# Sheet1.net
KiCad netlist of a schematic drawn in Altium Designer
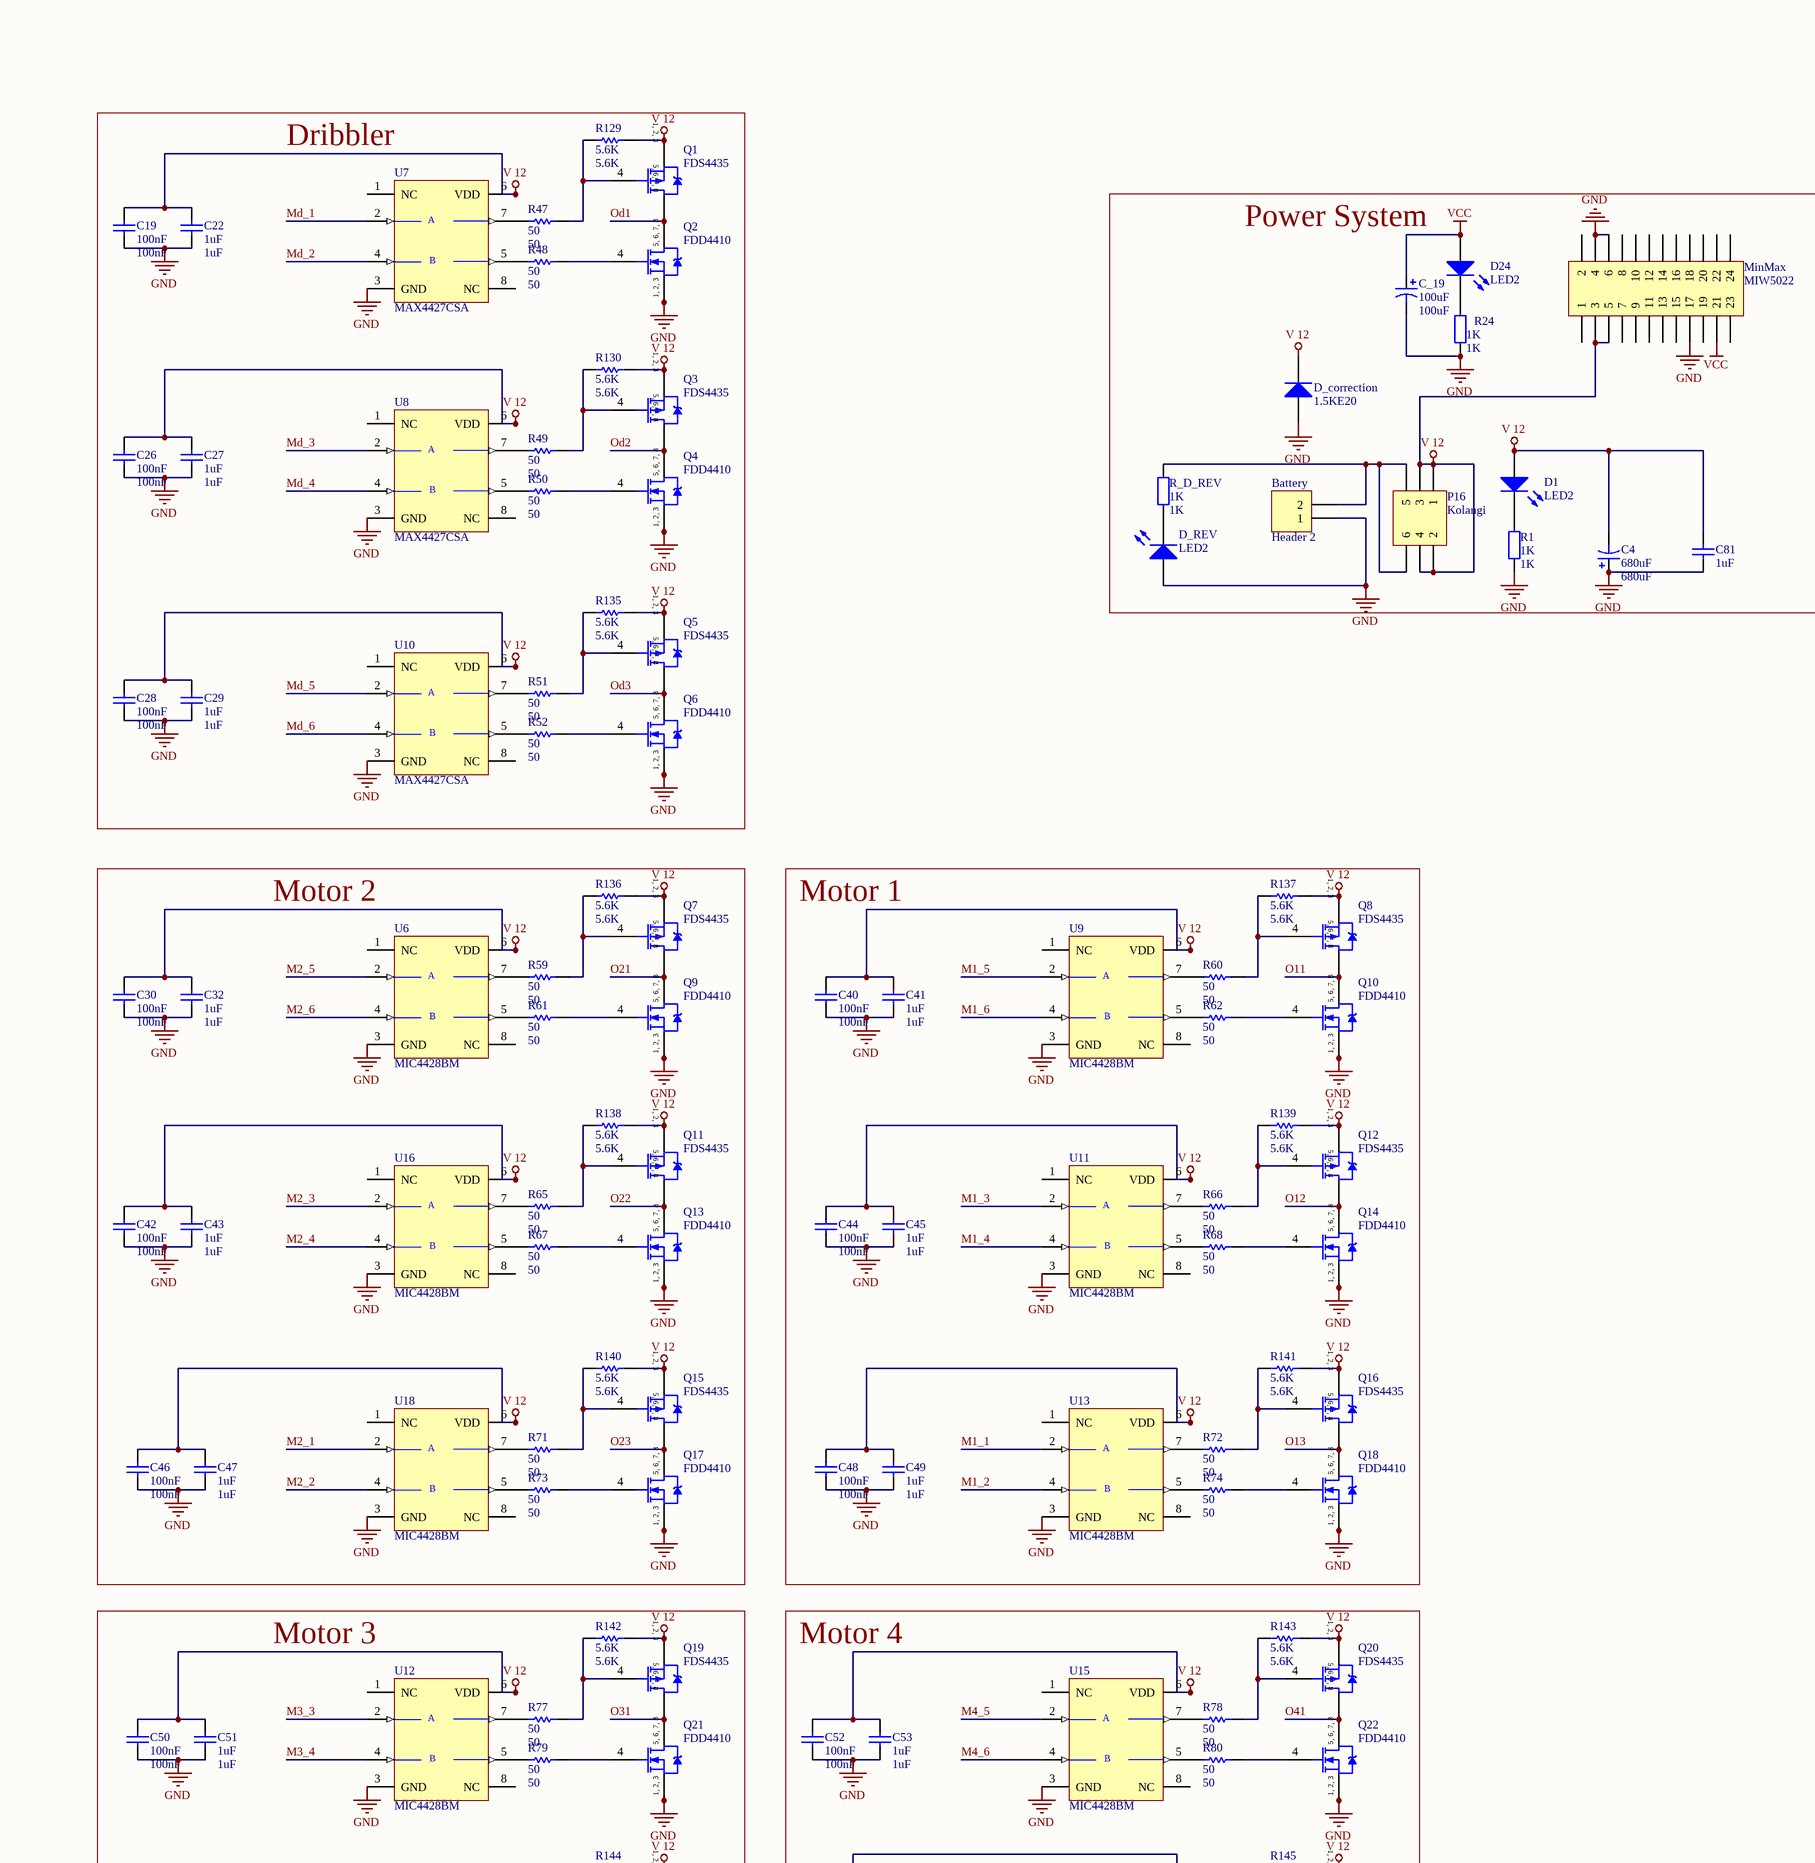
[diagram p0: Sheet1.SchDoc, top left]
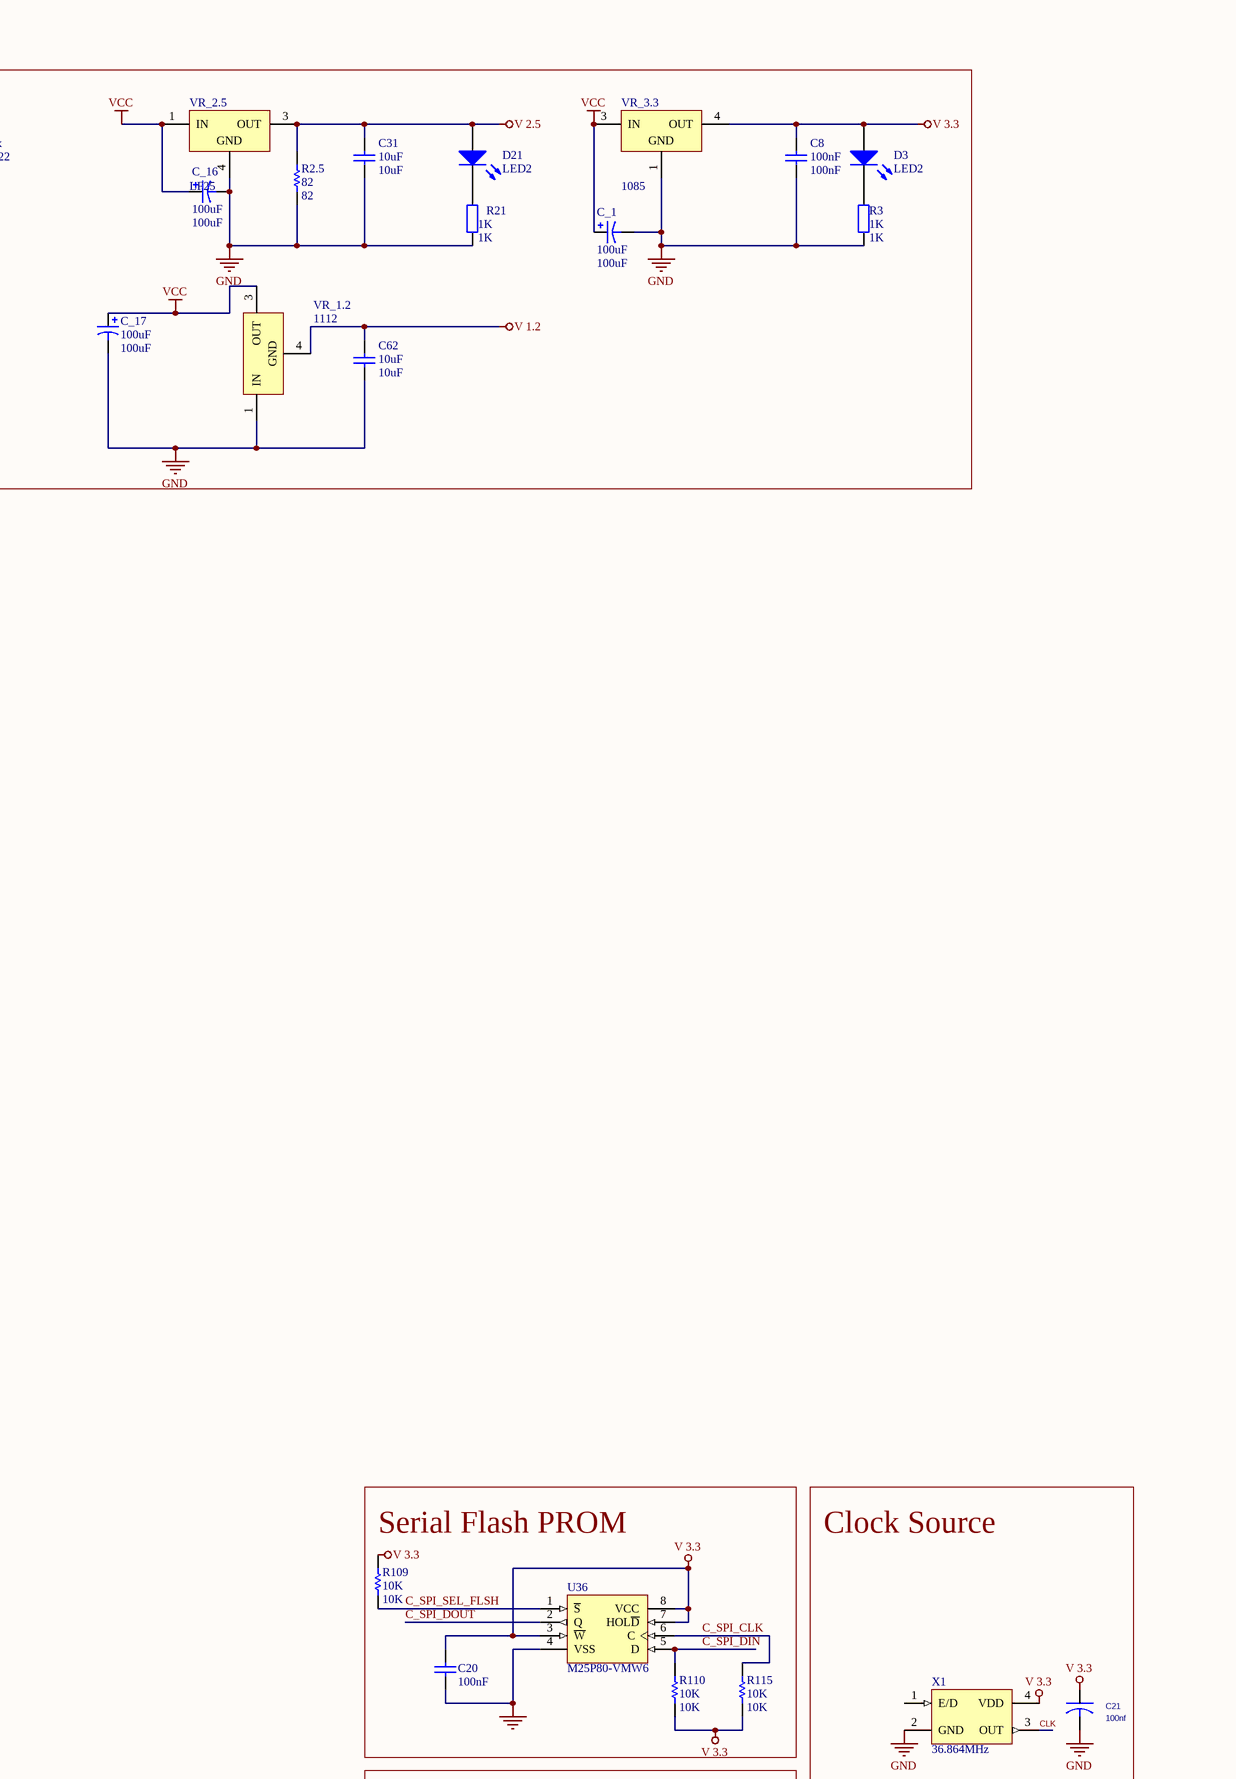
[diagram p1: Sheet1.SchDoc, top middle]
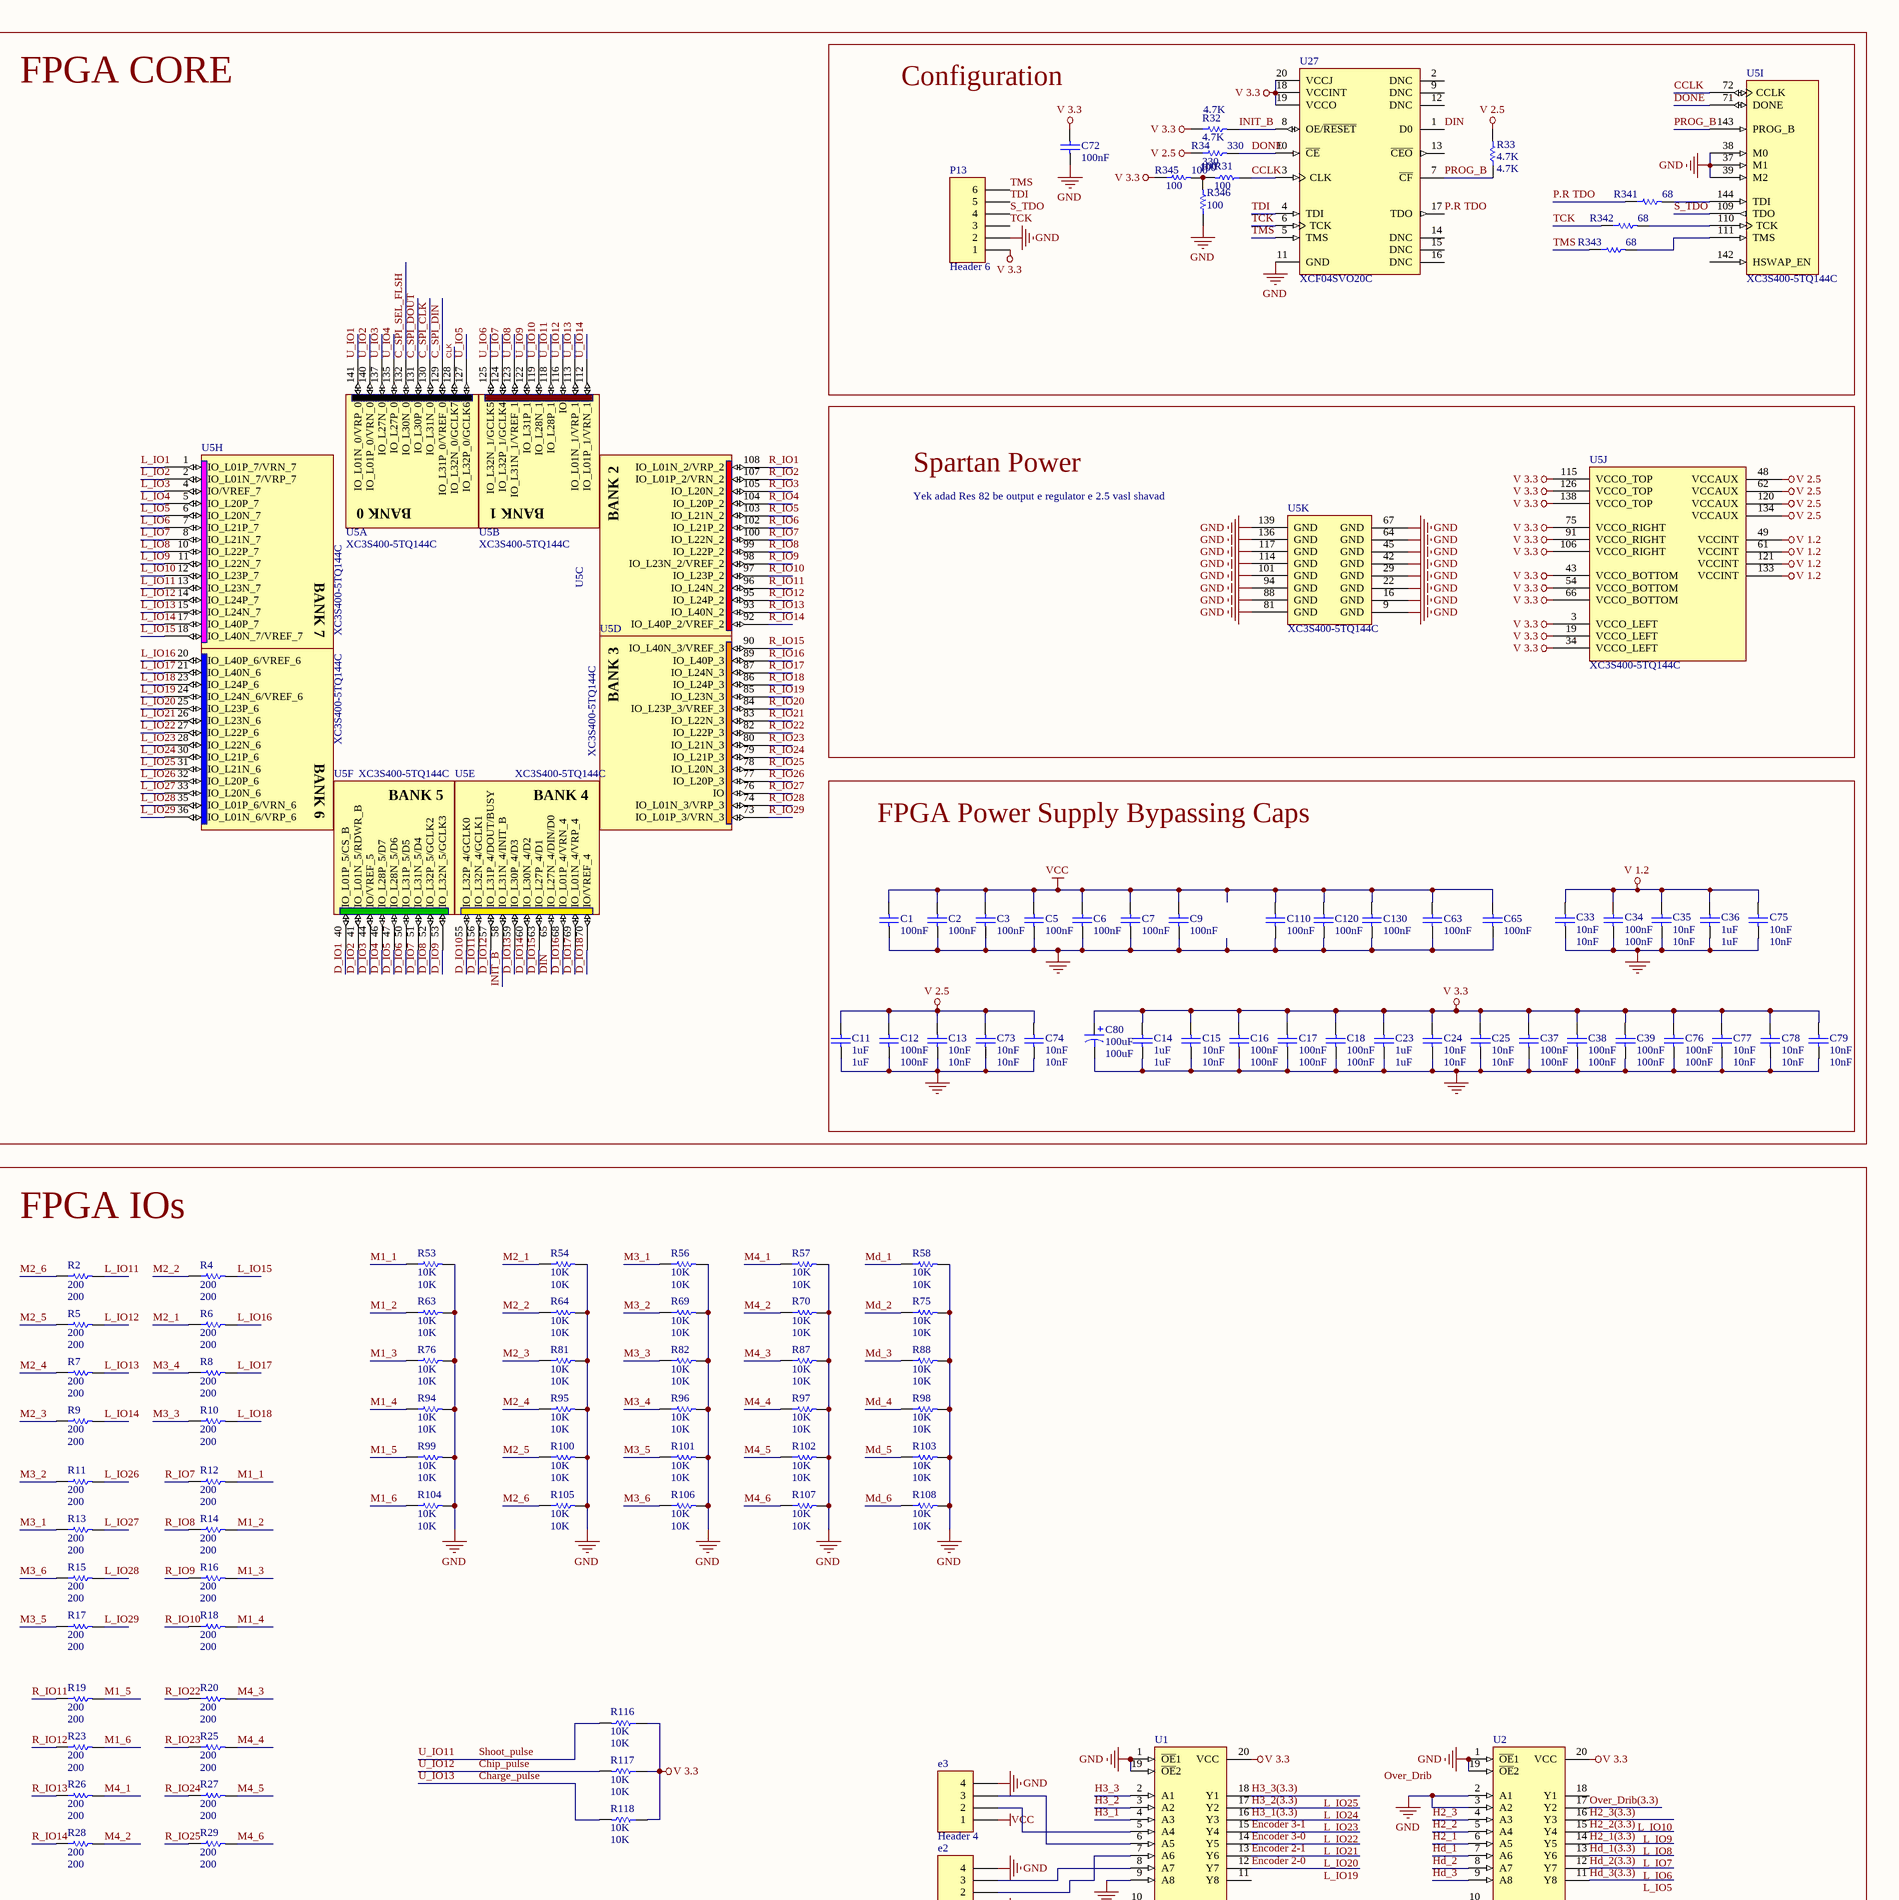
[diagram p2: Sheet1.SchDoc, top right]
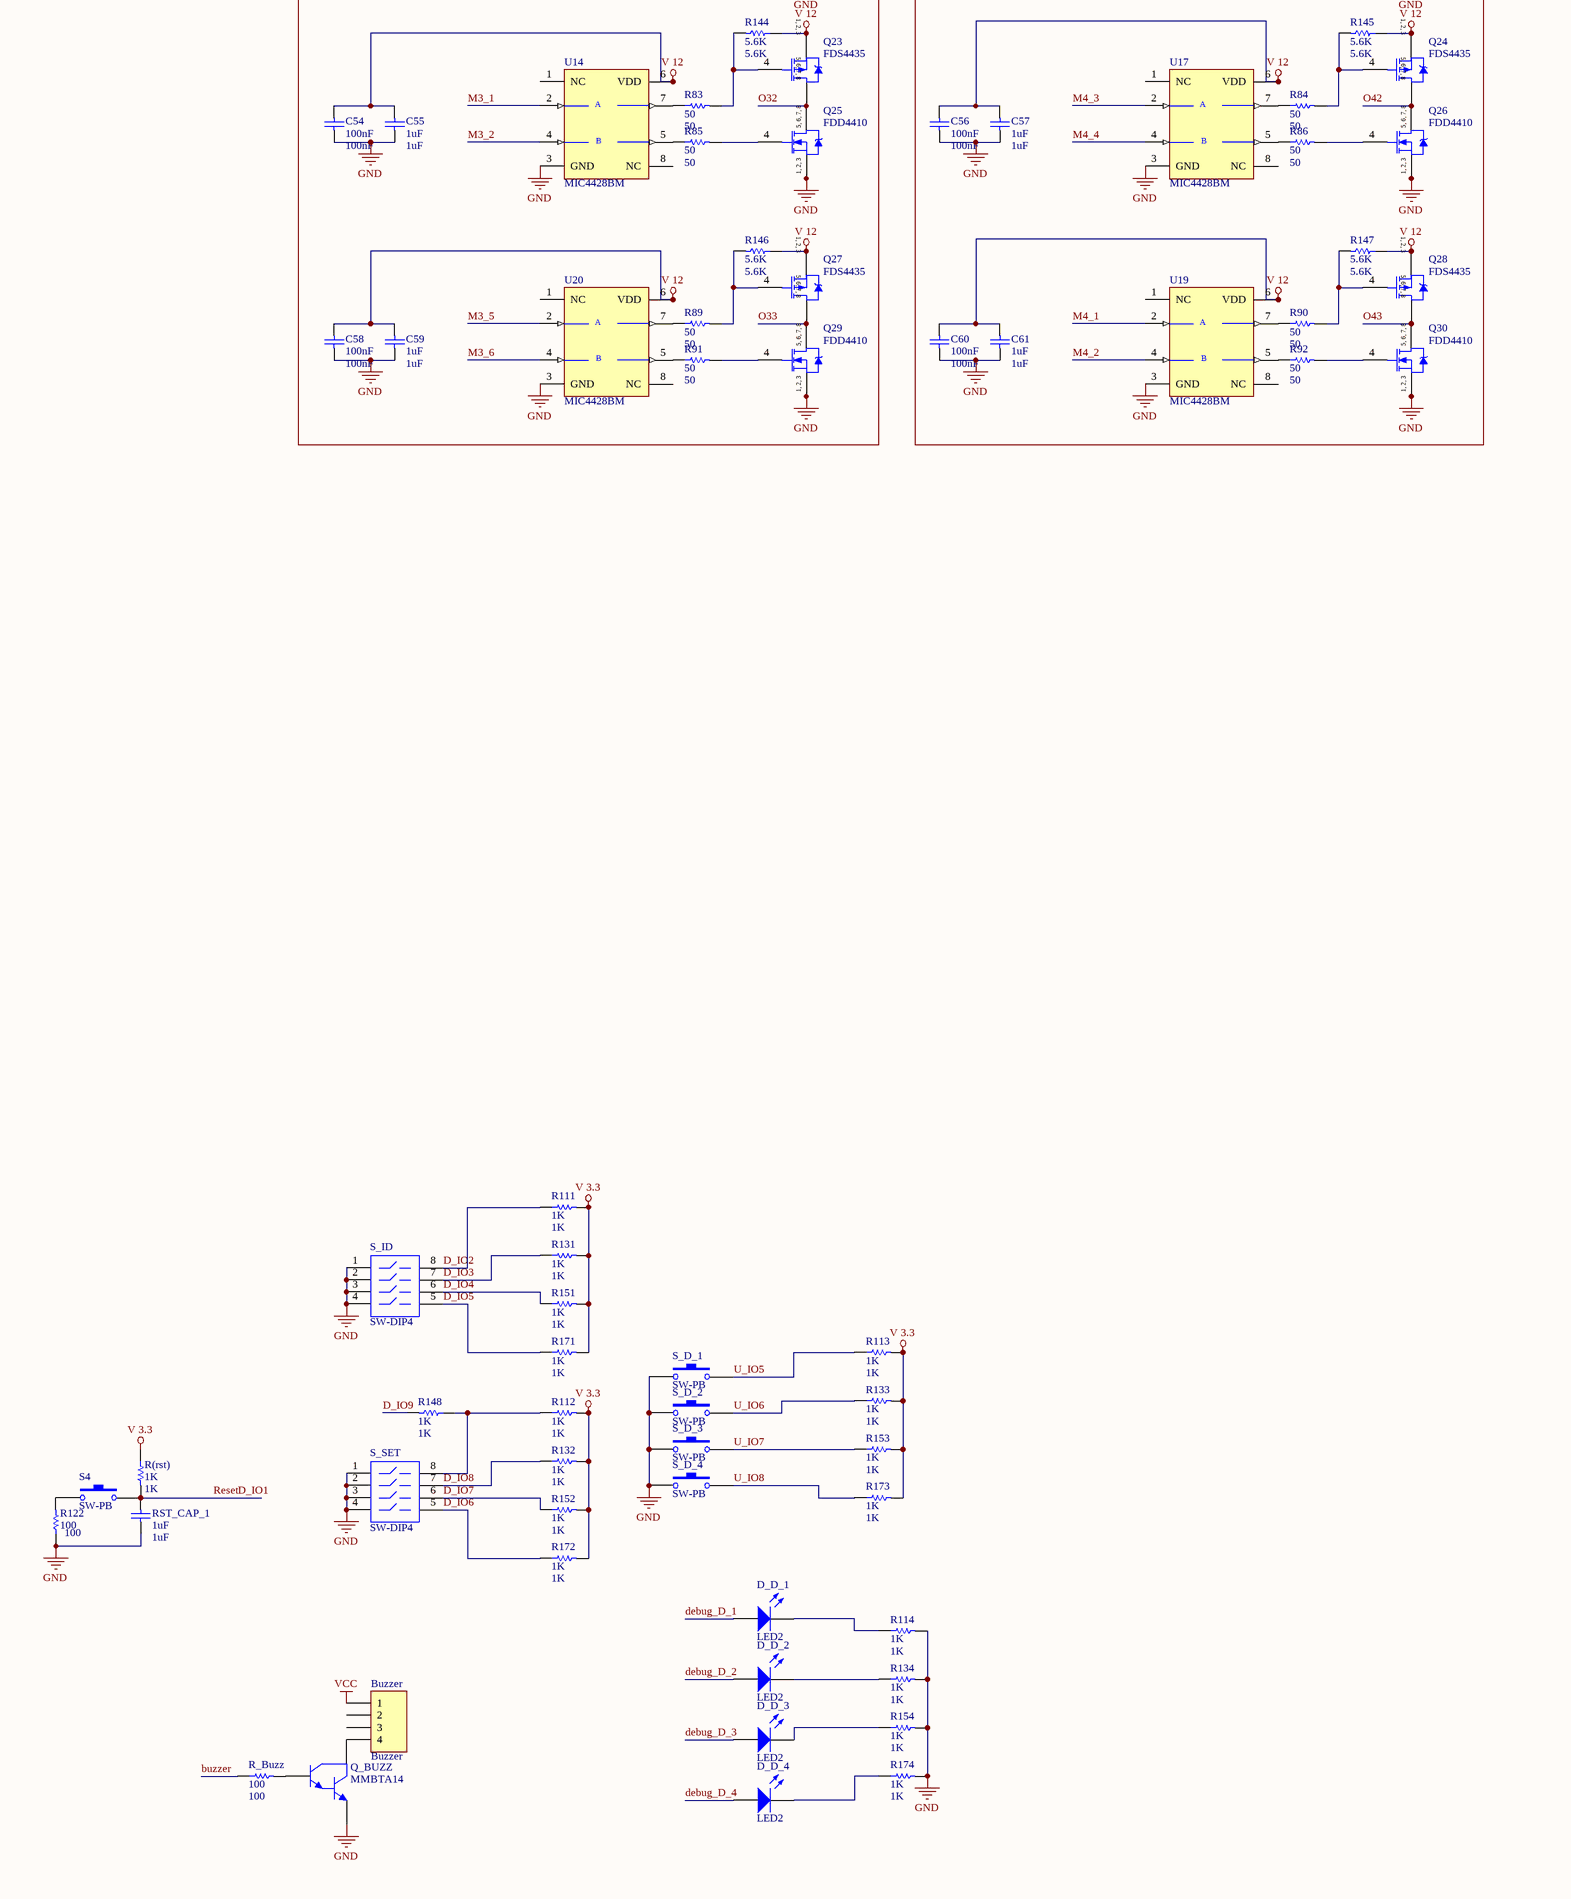
[diagram p3: Sheet1.SchDoc, bottom left]
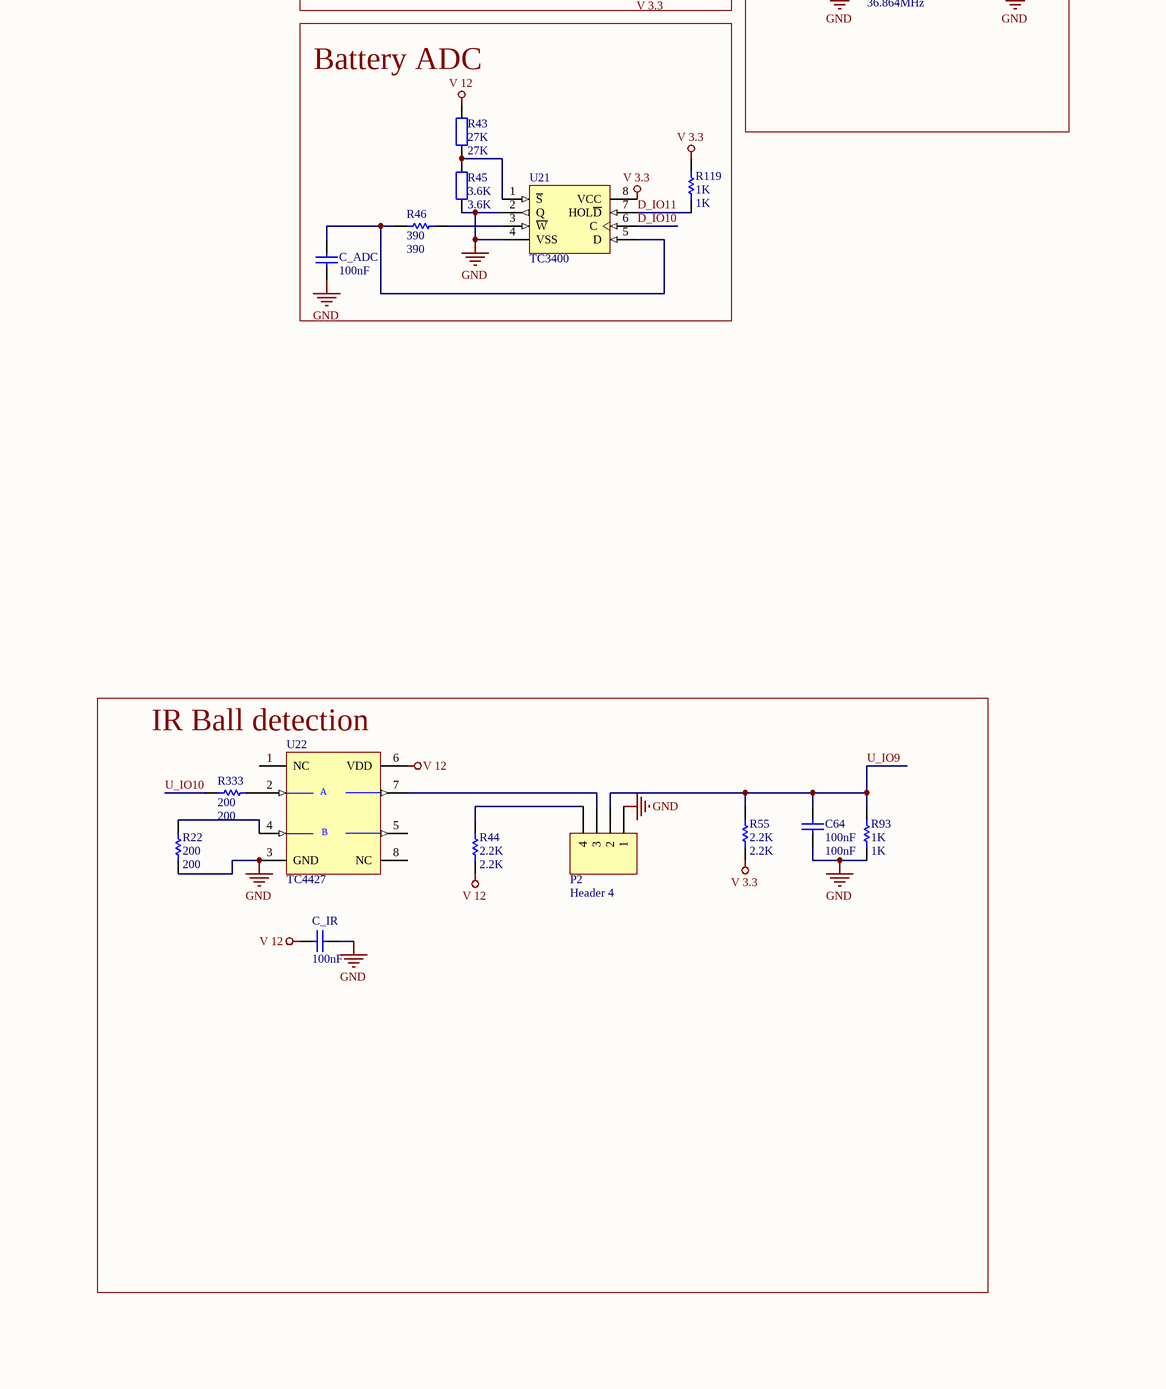
[diagram p4: Sheet1.SchDoc, bottom middle]
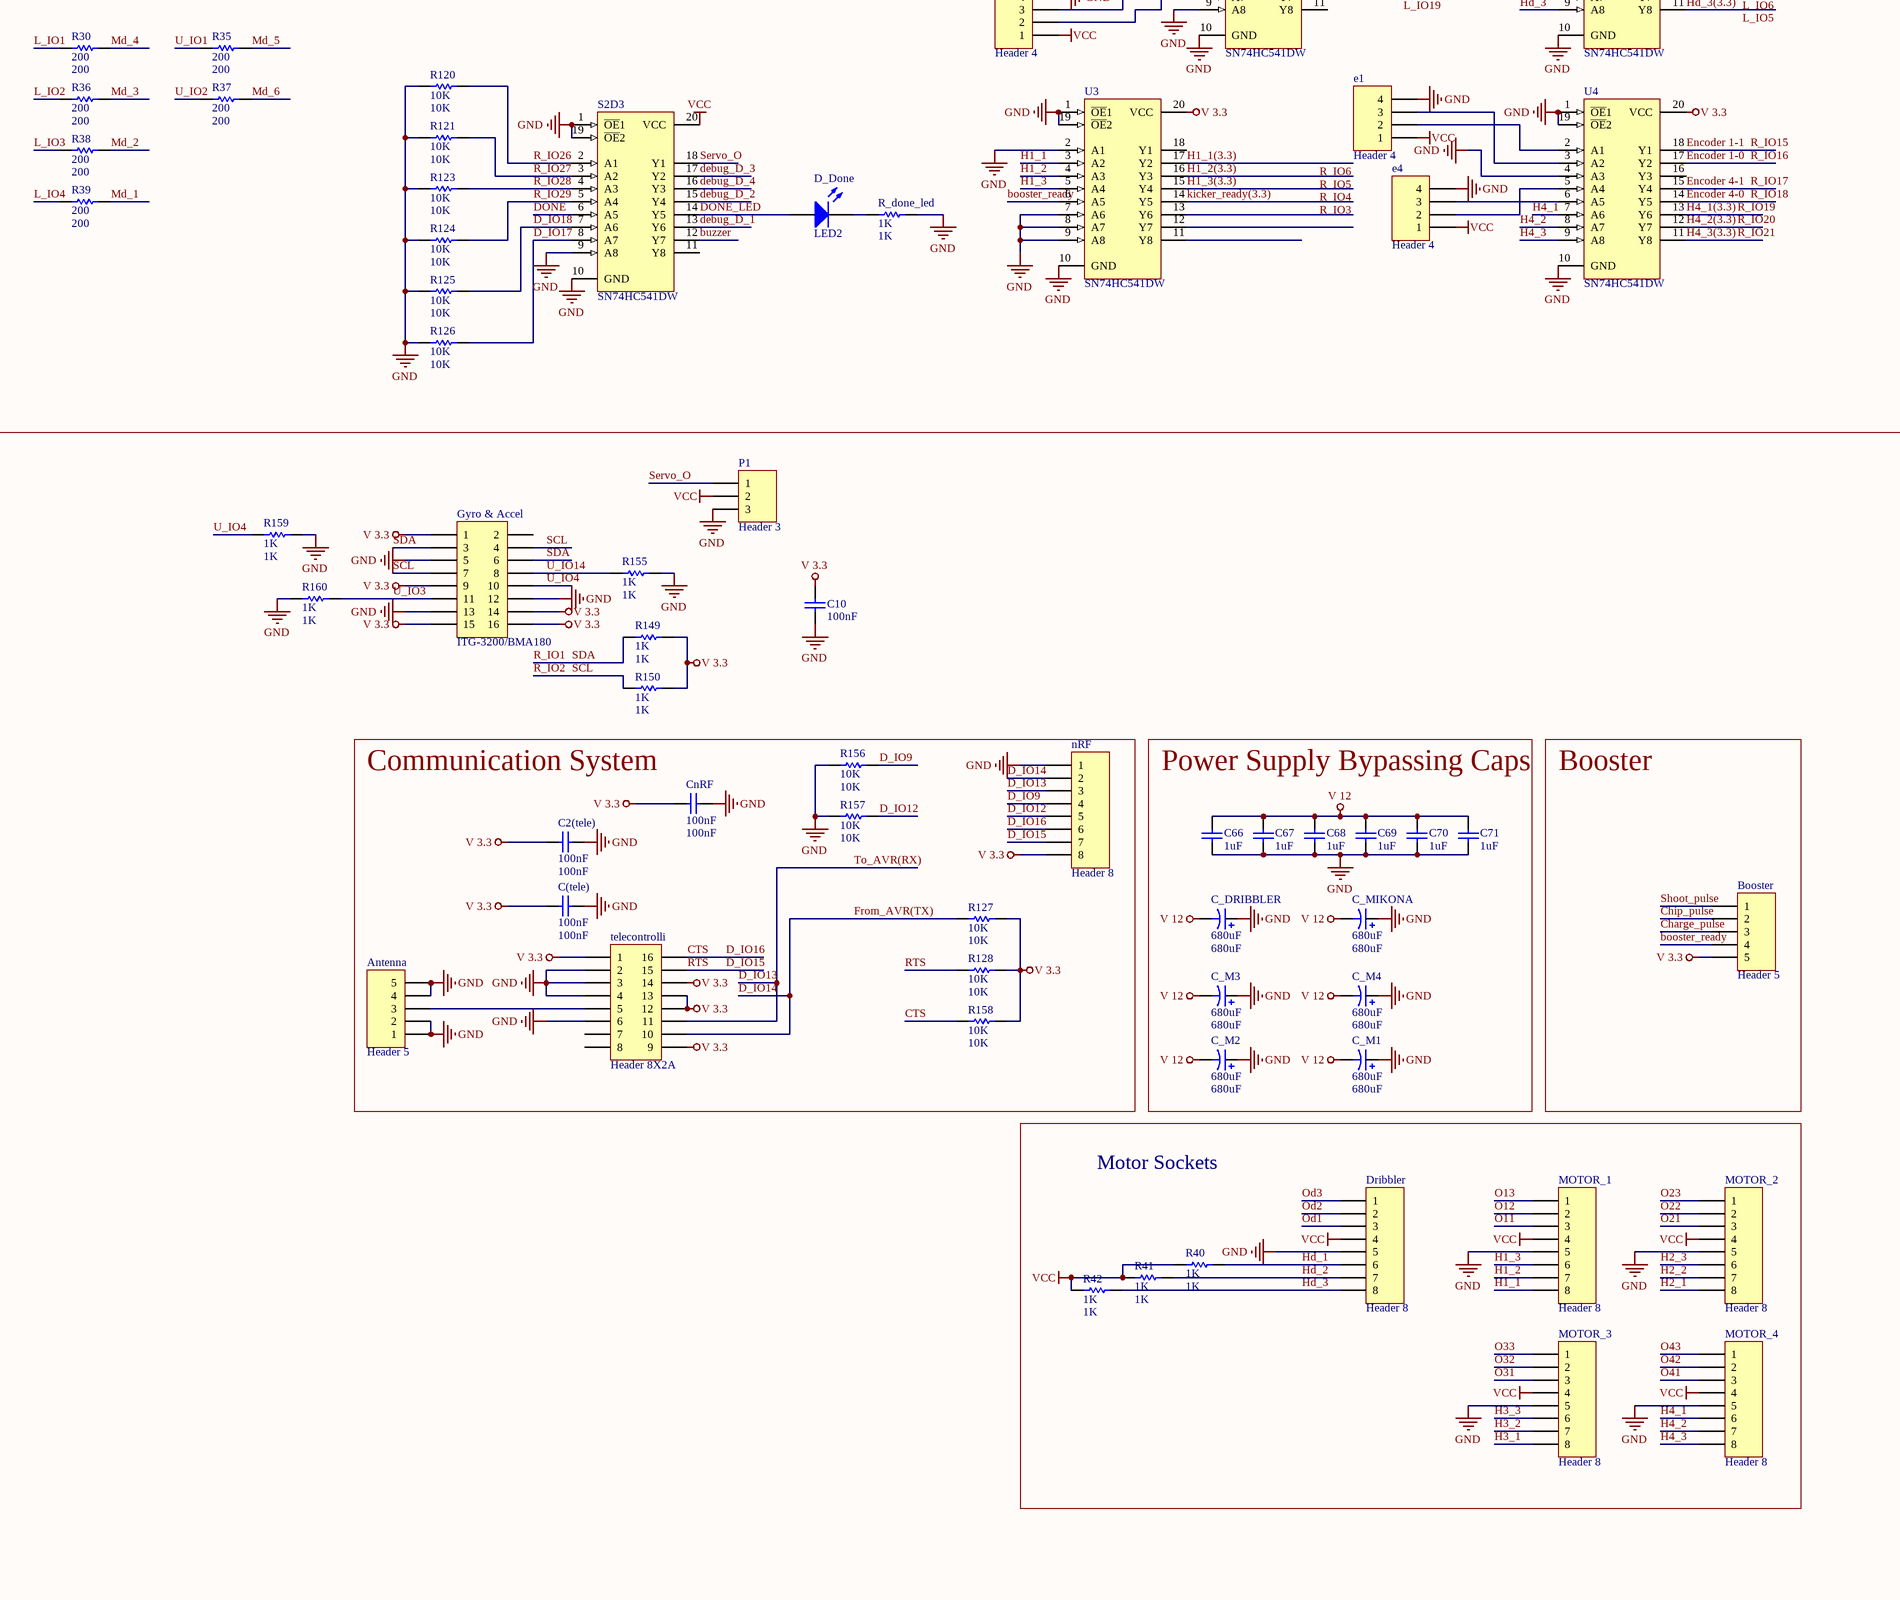
[diagram p5: Sheet1.SchDoc, bottom right]

(export (version "E")
  (design (tool "Eeschema 10.0.6"))
  (components
    (comp (ref "Antenna")
      (value "Header 5")
      (footprint "PcbLib1:Antenna")
      (description "Header, 5-Pin")
      (fields (field (name "PUBLISHER") "Altium Limited"))
      (libsource (lib "Miscellaneous Connectors") (part "Header 5"))
    )
    (comp (ref "Battery")
      (value "Header 2")
      (footprint "HDR1X2")
      (description "Header, 2-Pin")
      (fields (field (name "PUBLISHER") "Altium Limited"))
      (libsource (lib "Miscellaneous Connectors") (part "Header 2"))
    )
    (comp (ref "Booster")
      (value "Header 5")
      (footprint "HDR1X5")
      (description "Header, 5-Pin")
      (fields (field (name "PUBLISHER") "Altium Limited"))
      (libsource (lib "") (part "Header 5_1"))
    )
    (comp (ref "Buzzer")
      (value "Buzzer")
      (footprint "HDR1X4")
      (description "Header, 4-Pin")
      (fields (field (name "PUBLISHER") "Altium Limited"))
      (libsource (lib "") (part "Header 4_1"))
    )
    (comp (ref "C(tele)")
      (value "100nF")
      (footprint "Miscellaneous Devices:3216[1206]")
      (description "Capacitor")
      (fields (field (name "ALTIUM_VALUE") "100nF") (field (name "PUBLISHER") "Altium Limited"))
      (libsource (lib "Miscellaneous Devices") (part "Cap"))
    )
    (comp (ref "C1")
      (value "100nF")
      (footprint "C1206")
      (description "Capacitor")
      (libsource (lib "Altium Nanoboard Project") (part "CAP"))
    )
    (comp (ref "C2")
      (value "100nF")
      (footprint "C1206")
      (description "Capacitor")
      (libsource (lib "Altium Nanoboard Project") (part "CAP"))
    )
    (comp (ref "C2(tele)")
      (value "100nF")
      (footprint "Miscellaneous Devices:3216[1206]")
      (description "Capacitor")
      (fields (field (name "ALTIUM_VALUE") "100nF") (field (name "PUBLISHER") "Altium Limited"))
      (libsource (lib "Miscellaneous Devices") (part "Cap"))
    )
    (comp (ref "C3")
      (value "100nF")
      (footprint "C1206")
      (description "Capacitor")
      (libsource (lib "Altium Nanoboard Project") (part "CAP"))
    )
    (comp (ref "C4")
      (value "680uF")
      (footprint "CAPPR5-5x5")
      (description "Polarized Capacitor (Radial)")
      (fields (field (name "ALTIUM_VALUE") "680uF") (field (name "PUBLISHER") "Altium Limited"))
      (libsource (lib "Miscellaneous Devices") (part "Cap Pol1"))
    )
    (comp (ref "C5")
      (value "100nF")
      (footprint "C1206")
      (description "Capacitor")
      (libsource (lib "Altium Nanoboard Project") (part "CAP"))
    )
    (comp (ref "C6")
      (value "100nF")
      (footprint "C1206")
      (description "Capacitor")
      (libsource (lib "Altium Nanoboard Project") (part "CAP"))
    )
    (comp (ref "C7")
      (value "100nF")
      (footprint "C1206")
      (description "Capacitor")
      (libsource (lib "Altium Nanoboard Project") (part "CAP"))
    )
    (comp (ref "C8")
      (value "100nF")
      (footprint "C1206")
      (description "Capacitor (Semiconductor SIM Model)")
      (fields (field (name "ALTIUM_VALUE") "100nF") (field (name "PUBLISHER") "Altium Limited"))
      (libsource (lib "Miscellaneous Devices") (part "Cap Semi"))
    )
    (comp (ref "C9")
      (value "100nF")
      (footprint "C1206")
      (description "Capacitor")
      (libsource (lib "Altium Nanoboard Project") (part "CAP"))
    )
    (comp (ref "C10")
      (value "100nF")
      (footprint "C1206")
      (description "Capacitor")
      (libsource (lib "Altium Nanoboard Project") (part "CAP"))
    )
    (comp (ref "C11")
      (value "1uF")
      (footprint "1608[0603]")
      (description "Capacitor (Semiconductor SIM Model)")
      (fields (field (name "ALTIUM_VALUE") "1uF") (field (name "PUBLISHER") "Altium Limited"))
      (libsource (lib "Miscellaneous Devices") (part "Cap Semi"))
    )
    (comp (ref "C12")
      (value "100nF")
      (footprint "1608[0603]")
      (description "Capacitor (Semiconductor SIM Model)")
      (fields (field (name "ALTIUM_VALUE") "100nF") (field (name "PUBLISHER") "Altium Limited"))
      (libsource (lib "Miscellaneous Devices") (part "Cap Semi"))
    )
    (comp (ref "C13")
      (value "10nF")
      (footprint "1608[0603]")
      (description "Capacitor (Semiconductor SIM Model)")
      (fields (field (name "ALTIUM_VALUE") "10nF") (field (name "PUBLISHER") "Altium Limited"))
      (libsource (lib "Miscellaneous Devices") (part "Cap Semi"))
    )
    (comp (ref "C14")
      (value "1uF")
      (footprint "1608[0603]")
      (description "Capacitor (Semiconductor SIM Model)")
      (fields (field (name "ALTIUM_VALUE") "1uF") (field (name "PUBLISHER") "Altium Limited"))
      (libsource (lib "Miscellaneous Devices") (part "Cap Semi"))
    )
    (comp (ref "C15")
      (value "10nF")
      (footprint "1608[0603]")
      (description "Capacitor (Semiconductor SIM Model)")
      (fields (field (name "ALTIUM_VALUE") "10nF") (field (name "PUBLISHER") "Altium Limited"))
      (libsource (lib "Miscellaneous Devices") (part "Cap Semi"))
    )
    (comp (ref "C16")
      (value "100nF")
      (footprint "1608[0603]")
      (description "Capacitor (Semiconductor SIM Model)")
      (fields (field (name "ALTIUM_VALUE") "100nF") (field (name "PUBLISHER") "Altium Limited"))
      (libsource (lib "Miscellaneous Devices") (part "Cap Semi"))
    )
    (comp (ref "C17")
      (value "100nF")
      (footprint "1608[0603]")
      (description "Capacitor (Semiconductor SIM Model)")
      (fields (field (name "ALTIUM_VALUE") "100nF") (field (name "PUBLISHER") "Altium Limited"))
      (libsource (lib "Miscellaneous Devices") (part "Cap Semi"))
    )
    (comp (ref "C18")
      (value "100nF")
      (footprint "1608[0603]")
      (description "Capacitor (Semiconductor SIM Model)")
      (fields (field (name "ALTIUM_VALUE") "100nF") (field (name "PUBLISHER") "Altium Limited"))
      (libsource (lib "Miscellaneous Devices") (part "Cap Semi"))
    )
    (comp (ref "C19")
      (value "100nF")
      (footprint "1608[0603]")
      (description "Capacitor (Semiconductor SIM Model)")
      (fields (field (name "ALTIUM_VALUE") "100nF") (field (name "PUBLISHER") "Altium Limited"))
      (libsource (lib "Miscellaneous Devices") (part "Cap Semi"))
    )
    (comp (ref "C20")
      (value "100nF")
      (footprint "C1206")
      (description "Capacitor")
      (libsource (lib "Altium Nanoboard Project") (part "CAP"))
    )
    (comp (ref "C21") (value "100nf") (footprint "2012[0805]") (libsource (lib "*") (part "C_Dup1")))
    (comp (ref "C22")
      (value "1uF")
      (footprint "1608[0603]")
      (description "Capacitor (Semiconductor SIM Model)")
      (fields (field (name "ALTIUM_VALUE") "1uF") (field (name "PUBLISHER") "Altium Limited"))
      (libsource (lib "Miscellaneous Devices") (part "Cap Semi"))
    )
    (comp (ref "C23")
      (value "1uF")
      (footprint "1608[0603]")
      (description "Capacitor (Semiconductor SIM Model)")
      (fields (field (name "ALTIUM_VALUE") "1uF") (field (name "PUBLISHER") "Altium Limited"))
      (libsource (lib "Miscellaneous Devices") (part "Cap Semi"))
    )
    (comp (ref "C24")
      (value "10nF")
      (footprint "1608[0603]")
      (description "Capacitor (Semiconductor SIM Model)")
      (fields (field (name "ALTIUM_VALUE") "10nF") (field (name "PUBLISHER") "Altium Limited"))
      (libsource (lib "Miscellaneous Devices") (part "Cap Semi"))
    )
    (comp (ref "C25")
      (value "10nF")
      (footprint "1608[0603]")
      (description "Capacitor (Semiconductor SIM Model)")
      (fields (field (name "ALTIUM_VALUE") "10nF") (field (name "PUBLISHER") "Altium Limited"))
      (libsource (lib "Miscellaneous Devices") (part "Cap Semi"))
    )
    (comp (ref "C26")
      (value "100nF")
      (footprint "1608[0603]")
      (description "Capacitor (Semiconductor SIM Model)")
      (fields (field (name "ALTIUM_VALUE") "100nF") (field (name "PUBLISHER") "Altium Limited"))
      (libsource (lib "Miscellaneous Devices") (part "Cap Semi"))
    )
    (comp (ref "C27")
      (value "1uF")
      (footprint "1608[0603]")
      (description "Capacitor (Semiconductor SIM Model)")
      (fields (field (name "ALTIUM_VALUE") "1uF") (field (name "PUBLISHER") "Altium Limited"))
      (libsource (lib "Miscellaneous Devices") (part "Cap Semi"))
    )
    (comp (ref "C28")
      (value "100nF")
      (footprint "1608[0603]")
      (description "Capacitor (Semiconductor SIM Model)")
      (fields (field (name "ALTIUM_VALUE") "100nF") (field (name "PUBLISHER") "Altium Limited"))
      (libsource (lib "Miscellaneous Devices") (part "Cap Semi"))
    )
    (comp (ref "C29")
      (value "1uF")
      (footprint "1608[0603]")
      (description "Capacitor (Semiconductor SIM Model)")
      (fields (field (name "ALTIUM_VALUE") "1uF") (field (name "PUBLISHER") "Altium Limited"))
      (libsource (lib "Miscellaneous Devices") (part "Cap Semi"))
    )
    (comp (ref "C30")
      (value "100nF")
      (footprint "1608[0603]")
      (description "Capacitor (Semiconductor SIM Model)")
      (fields (field (name "ALTIUM_VALUE") "100nF") (field (name "PUBLISHER") "Altium Limited"))
      (libsource (lib "Miscellaneous Devices") (part "Cap Semi"))
    )
    (comp (ref "C31")
      (value "10uF")
      (footprint "C1206")
      (description "Capacitor (Semiconductor SIM Model)")
      (fields (field (name "ALTIUM_VALUE") "10uF") (field (name "PUBLISHER") "Altium Limited"))
      (libsource (lib "Miscellaneous Devices") (part "Cap Semi"))
    )
    (comp (ref "C32")
      (value "1uF")
      (footprint "1608[0603]")
      (description "Capacitor (Semiconductor SIM Model)")
      (fields (field (name "ALTIUM_VALUE") "1uF") (field (name "PUBLISHER") "Altium Limited"))
      (libsource (lib "Miscellaneous Devices") (part "Cap Semi"))
    )
    (comp (ref "C33")
      (value "10nF")
      (footprint "1608[0603]")
      (description "Capacitor (Semiconductor SIM Model)")
      (fields (field (name "ALTIUM_VALUE") "10nF") (field (name "PUBLISHER") "Altium Limited"))
      (libsource (lib "Miscellaneous Devices") (part "Cap Semi"))
    )
    (comp (ref "C34")
      (value "100nF")
      (footprint "1608[0603]")
      (description "Capacitor (Semiconductor SIM Model)")
      (fields (field (name "ALTIUM_VALUE") "100nF") (field (name "PUBLISHER") "Altium Limited"))
      (libsource (lib "Miscellaneous Devices") (part "Cap Semi"))
    )
    (comp (ref "C35")
      (value "10nF")
      (footprint "1608[0603]")
      (description "Capacitor (Semiconductor SIM Model)")
      (fields (field (name "ALTIUM_VALUE") "10nF") (field (name "PUBLISHER") "Altium Limited"))
      (libsource (lib "Miscellaneous Devices") (part "Cap Semi"))
    )
    (comp (ref "C36")
      (value "1uF")
      (footprint "1608[0603]")
      (description "Capacitor (Semiconductor SIM Model)")
      (fields (field (name "ALTIUM_VALUE") "1uF") (field (name "PUBLISHER") "Altium Limited"))
      (libsource (lib "Miscellaneous Devices") (part "Cap Semi"))
    )
    (comp (ref "C37")
      (value "100nF")
      (footprint "1608[0603]")
      (description "Capacitor (Semiconductor SIM Model)")
      (fields (field (name "ALTIUM_VALUE") "100nF") (field (name "PUBLISHER") "Altium Limited"))
      (libsource (lib "Miscellaneous Devices") (part "Cap Semi"))
    )
    (comp (ref "C38")
      (value "100nF")
      (footprint "1608[0603]")
      (description "Capacitor (Semiconductor SIM Model)")
      (fields (field (name "ALTIUM_VALUE") "100nF") (field (name "PUBLISHER") "Altium Limited"))
      (libsource (lib "Miscellaneous Devices") (part "Cap Semi"))
    )
    (comp (ref "C39")
      (value "100nF")
      (footprint "1608[0603]")
      (description "Capacitor (Semiconductor SIM Model)")
      (fields (field (name "ALTIUM_VALUE") "100nF") (field (name "PUBLISHER") "Altium Limited"))
      (libsource (lib "Miscellaneous Devices") (part "Cap Semi"))
    )
    (comp (ref "C40")
      (value "100nF")
      (footprint "1608[0603]")
      (description "Capacitor (Semiconductor SIM Model)")
      (fields (field (name "ALTIUM_VALUE") "100nF") (field (name "PUBLISHER") "Altium Limited"))
      (libsource (lib "Miscellaneous Devices") (part "Cap Semi"))
    )
    (comp (ref "C41")
      (value "1uF")
      (footprint "1608[0603]")
      (description "Capacitor (Semiconductor SIM Model)")
      (fields (field (name "ALTIUM_VALUE") "1uF") (field (name "PUBLISHER") "Altium Limited"))
      (libsource (lib "Miscellaneous Devices") (part "Cap Semi"))
    )
    (comp (ref "C42")
      (value "100nF")
      (footprint "1608[0603]")
      (description "Capacitor (Semiconductor SIM Model)")
      (fields (field (name "ALTIUM_VALUE") "100nF") (field (name "PUBLISHER") "Altium Limited"))
      (libsource (lib "Miscellaneous Devices") (part "Cap Semi"))
    )
    (comp (ref "C43")
      (value "1uF")
      (footprint "1608[0603]")
      (description "Capacitor (Semiconductor SIM Model)")
      (fields (field (name "ALTIUM_VALUE") "1uF") (field (name "PUBLISHER") "Altium Limited"))
      (libsource (lib "Miscellaneous Devices") (part "Cap Semi"))
    )
    (comp (ref "C44")
      (value "100nF")
      (footprint "1608[0603]")
      (description "Capacitor (Semiconductor SIM Model)")
      (fields (field (name "ALTIUM_VALUE") "100nF") (field (name "PUBLISHER") "Altium Limited"))
      (libsource (lib "Miscellaneous Devices") (part "Cap Semi"))
    )
    (comp (ref "C45")
      (value "1uF")
      (footprint "1608[0603]")
      (description "Capacitor (Semiconductor SIM Model)")
      (fields (field (name "ALTIUM_VALUE") "1uF") (field (name "PUBLISHER") "Altium Limited"))
      (libsource (lib "Miscellaneous Devices") (part "Cap Semi"))
    )
    (comp (ref "C46")
      (value "100nF")
      (footprint "1608[0603]")
      (description "Capacitor (Semiconductor SIM Model)")
      (fields (field (name "ALTIUM_VALUE") "100nF") (field (name "PUBLISHER") "Altium Limited"))
      (libsource (lib "Miscellaneous Devices") (part "Cap Semi"))
    )
    (comp (ref "C47")
      (value "1uF")
      (footprint "1608[0603]")
      (description "Capacitor (Semiconductor SIM Model)")
      (fields (field (name "ALTIUM_VALUE") "1uF") (field (name "PUBLISHER") "Altium Limited"))
      (libsource (lib "Miscellaneous Devices") (part "Cap Semi"))
    )
    (comp (ref "C48")
      (value "100nF")
      (footprint "1608[0603]")
      (description "Capacitor (Semiconductor SIM Model)")
      (fields (field (name "ALTIUM_VALUE") "100nF") (field (name "PUBLISHER") "Altium Limited"))
      (libsource (lib "Miscellaneous Devices") (part "Cap Semi"))
    )
    (comp (ref "C49")
      (value "1uF")
      (footprint "1608[0603]")
      (description "Capacitor (Semiconductor SIM Model)")
      (fields (field (name "ALTIUM_VALUE") "1uF") (field (name "PUBLISHER") "Altium Limited"))
      (libsource (lib "Miscellaneous Devices") (part "Cap Semi"))
    )
    (comp (ref "C50")
      (value "100nF")
      (footprint "1608[0603]")
      (description "Capacitor (Semiconductor SIM Model)")
      (fields (field (name "ALTIUM_VALUE") "100nF") (field (name "PUBLISHER") "Altium Limited"))
      (libsource (lib "Miscellaneous Devices") (part "Cap Semi"))
    )
    (comp (ref "C51")
      (value "1uF")
      (footprint "1608[0603]")
      (description "Capacitor (Semiconductor SIM Model)")
      (fields (field (name "ALTIUM_VALUE") "1uF") (field (name "PUBLISHER") "Altium Limited"))
      (libsource (lib "Miscellaneous Devices") (part "Cap Semi"))
    )
    (comp (ref "C52")
      (value "100nF")
      (footprint "1608[0603]")
      (description "Capacitor (Semiconductor SIM Model)")
      (fields (field (name "ALTIUM_VALUE") "100nF") (field (name "PUBLISHER") "Altium Limited"))
      (libsource (lib "Miscellaneous Devices") (part "Cap Semi"))
    )
    (comp (ref "C53")
      (value "1uF")
      (footprint "1608[0603]")
      (description "Capacitor (Semiconductor SIM Model)")
      (fields (field (name "ALTIUM_VALUE") "1uF") (field (name "PUBLISHER") "Altium Limited"))
      (libsource (lib "Miscellaneous Devices") (part "Cap Semi"))
    )
    (comp (ref "C54")
      (value "100nF")
      (footprint "1608[0603]")
      (description "Capacitor (Semiconductor SIM Model)")
      (fields (field (name "ALTIUM_VALUE") "100nF") (field (name "PUBLISHER") "Altium Limited"))
      (libsource (lib "Miscellaneous Devices") (part "Cap Semi"))
    )
    (comp (ref "C55")
      (value "1uF")
      (footprint "1608[0603]")
      (description "Capacitor (Semiconductor SIM Model)")
      (fields (field (name "ALTIUM_VALUE") "1uF") (field (name "PUBLISHER") "Altium Limited"))
      (libsource (lib "Miscellaneous Devices") (part "Cap Semi"))
    )
    (comp (ref "C56")
      (value "100nF")
      (footprint "1608[0603]")
      (description "Capacitor (Semiconductor SIM Model)")
      (fields (field (name "ALTIUM_VALUE") "100nF") (field (name "PUBLISHER") "Altium Limited"))
      (libsource (lib "Miscellaneous Devices") (part "Cap Semi"))
    )
    (comp (ref "C57")
      (value "1uF")
      (footprint "1608[0603]")
      (description "Capacitor (Semiconductor SIM Model)")
      (fields (field (name "ALTIUM_VALUE") "1uF") (field (name "PUBLISHER") "Altium Limited"))
      (libsource (lib "Miscellaneous Devices") (part "Cap Semi"))
    )
    (comp (ref "C58")
      (value "100nF")
      (footprint "1608[0603]")
      (description "Capacitor (Semiconductor SIM Model)")
      (fields (field (name "ALTIUM_VALUE") "100nF") (field (name "PUBLISHER") "Altium Limited"))
      (libsource (lib "Miscellaneous Devices") (part "Cap Semi"))
    )
    (comp (ref "C59")
      (value "1uF")
      (footprint "1608[0603]")
      (description "Capacitor (Semiconductor SIM Model)")
      (fields (field (name "ALTIUM_VALUE") "1uF") (field (name "PUBLISHER") "Altium Limited"))
      (libsource (lib "Miscellaneous Devices") (part "Cap Semi"))
    )
    (comp (ref "C60")
      (value "100nF")
      (footprint "1608[0603]")
      (description "Capacitor (Semiconductor SIM Model)")
      (fields (field (name "ALTIUM_VALUE") "100nF") (field (name "PUBLISHER") "Altium Limited"))
      (libsource (lib "Miscellaneous Devices") (part "Cap Semi"))
    )
    (comp (ref "C61")
      (value "1uF")
      (footprint "1608[0603]")
      (description "Capacitor (Semiconductor SIM Model)")
      (fields (field (name "ALTIUM_VALUE") "1uF") (field (name "PUBLISHER") "Altium Limited"))
      (libsource (lib "Miscellaneous Devices") (part "Cap Semi"))
    )
    (comp (ref "C62")
      (value "10uF")
      (footprint "C1206")
      (description "Capacitor (Semiconductor SIM Model)")
      (fields (field (name "ALTIUM_VALUE") "10uF") (field (name "PUBLISHER") "Altium Limited"))
      (libsource (lib "Miscellaneous Devices") (part "Cap Semi"))
    )
    (comp (ref "C63")
      (value "100nF")
      (footprint "C0805")
      (description "Capacitor")
      (libsource (lib "Altium Nanoboard Project") (part "CAP"))
    )
    (comp (ref "C64")
      (value "100nF")
      (footprint "1608[0603]")
      (description "Capacitor (Semiconductor SIM Model)")
      (fields (field (name "ALTIUM_VALUE") "100nF") (field (name "PUBLISHER") "Altium Limited"))
      (libsource (lib "Miscellaneous Devices") (part "Cap Semi"))
    )
    (comp (ref "C65")
      (value "100nF")
      (footprint "C0805")
      (description "Capacitor")
      (libsource (lib "Altium Nanoboard Project") (part "CAP"))
    )
    (comp (ref "C66")
      (value "1uF")
      (footprint "C0805")
      (description "Capacitor")
      (libsource (lib "Altium Nanoboard Project") (part "CAP"))
    )
    (comp (ref "C67")
      (value "1uF")
      (footprint "C0805")
      (description "Capacitor")
      (libsource (lib "Altium Nanoboard Project") (part "CAP"))
    )
    (comp (ref "C68")
      (value "1uF")
      (footprint "C0805")
      (description "Capacitor")
      (libsource (lib "Altium Nanoboard Project") (part "CAP"))
    )
    (comp (ref "C69")
      (value "1uF")
      (footprint "C0805")
      (description "Capacitor")
      (libsource (lib "Altium Nanoboard Project") (part "CAP"))
    )
    (comp (ref "C70")
      (value "1uF")
      (footprint "C0805")
      (description "Capacitor")
      (libsource (lib "Altium Nanoboard Project") (part "CAP"))
    )
    (comp (ref "C71")
      (value "1uF")
      (footprint "C0805")
      (description "Capacitor")
      (libsource (lib "Altium Nanoboard Project") (part "CAP"))
    )
    (comp (ref "C72")
      (value "100nF")
      (footprint "C0805")
      (description "Capacitor")
      (libsource (lib "Altium Nanoboard Project") (part "CAP"))
    )
    (comp (ref "C73")
      (value "10nF")
      (footprint "1608[0603]")
      (description "Capacitor (Semiconductor SIM Model)")
      (fields (field (name "ALTIUM_VALUE") "10nF") (field (name "PUBLISHER") "Altium Limited"))
      (libsource (lib "Miscellaneous Devices") (part "Cap Semi"))
    )
    (comp (ref "C74")
      (value "10nF")
      (footprint "1608[0603]")
      (description "Capacitor (Semiconductor SIM Model)")
      (fields (field (name "ALTIUM_VALUE") "10nF") (field (name "PUBLISHER") "Altium Limited"))
      (libsource (lib "Miscellaneous Devices") (part "Cap Semi"))
    )
    (comp (ref "C75")
      (value "10nF")
      (footprint "1608[0603]")
      (description "Capacitor (Semiconductor SIM Model)")
      (fields (field (name "ALTIUM_VALUE") "10nF") (field (name "PUBLISHER") "Altium Limited"))
      (libsource (lib "Miscellaneous Devices") (part "Cap Semi"))
    )
    (comp (ref "C76")
      (value "100nF")
      (footprint "1608[0603]")
      (description "Capacitor (Semiconductor SIM Model)")
      (fields (field (name "ALTIUM_VALUE") "100nF") (field (name "PUBLISHER") "Altium Limited"))
      (libsource (lib "Miscellaneous Devices") (part "Cap Semi"))
    )
    (comp (ref "C77")
      (value "10nF")
      (footprint "1608[0603]")
      (description "Capacitor (Semiconductor SIM Model)")
      (fields (field (name "ALTIUM_VALUE") "10nF") (field (name "PUBLISHER") "Altium Limited"))
      (libsource (lib "Miscellaneous Devices") (part "Cap Semi"))
    )
    (comp (ref "C78")
      (value "10nF")
      (footprint "1608[0603]")
      (description "Capacitor (Semiconductor SIM Model)")
      (fields (field (name "ALTIUM_VALUE") "10nF") (field (name "PUBLISHER") "Altium Limited"))
      (libsource (lib "Miscellaneous Devices") (part "Cap Semi"))
    )
    (comp (ref "C79")
      (value "10nF")
      (footprint "1608[0603]")
      (description "Capacitor (Semiconductor SIM Model)")
      (fields (field (name "ALTIUM_VALUE") "10nF") (field (name "PUBLISHER") "Altium Limited"))
      (libsource (lib "Miscellaneous Devices") (part "Cap Semi"))
    )
    (comp (ref "C80")
      (value "100uF")
      (footprint "6332[2512]")
      (description "Polarized Capacitor (Surface Mount)")
      (fields (field (name "ALTIUM_VALUE") "100uF") (field (name "PUBLISHER") "Altium Limited"))
      (libsource (lib "Miscellaneous Devices") (part "Cap Pol3"))
    )
    (comp (ref "C81")
      (value "1uF")
      (footprint "C0805")
      (description "Capacitor")
      (libsource (lib "Altium Nanoboard Project") (part "CAP"))
    )
    (comp (ref "C110")
      (value "100nF")
      (footprint "C1206")
      (description "Capacitor")
      (libsource (lib "Altium Nanoboard Project") (part "CAP"))
    )
    (comp (ref "C120")
      (value "100nF")
      (footprint "C1206")
      (description "Capacitor")
      (libsource (lib "Altium Nanoboard Project") (part "CAP"))
    )
    (comp (ref "C130")
      (value "100nF")
      (footprint "C1206")
      (description "Capacitor")
      (libsource (lib "Altium Nanoboard Project") (part "CAP"))
    )
    (comp (ref "CnRF")
      (value "100nF")
      (footprint "1608[0603]")
      (description "Capacitor (Semiconductor SIM Model)")
      (fields (field (name "ALTIUM_VALUE") "100nF") (field (name "PUBLISHER") "Altium Limited"))
      (libsource (lib "Miscellaneous Devices") (part "Cap Semi"))
    )
    (comp (ref "C_1")
      (value "100uF")
      (footprint "6332[2512]")
      (description "Polarized Capacitor (Surface Mount)")
      (fields (field (name "ALTIUM_VALUE") "100uF") (field (name "PUBLISHER") "Altium Limited"))
      (libsource (lib "Miscellaneous Devices") (part "Cap Pol3"))
    )
    (comp (ref "C_16")
      (value "100uF")
      (footprint "6332[2512]")
      (description "Polarized Capacitor (Surface Mount)")
      (fields (field (name "ALTIUM_VALUE") "100uF") (field (name "PUBLISHER") "Altium Limited"))
      (libsource (lib "Miscellaneous Devices") (part "Cap Pol3"))
    )
    (comp (ref "C_17")
      (value "100uF")
      (footprint "6332[2512]")
      (description "Polarized Capacitor (Surface Mount)")
      (fields (field (name "ALTIUM_VALUE") "100uF") (field (name "PUBLISHER") "Altium Limited"))
      (libsource (lib "Miscellaneous Devices") (part "Cap Pol3"))
    )
    (comp (ref "C_19")
      (value "100uF")
      (footprint "6332[2512]")
      (description "Polarized Capacitor (Surface Mount)")
      (fields (field (name "ALTIUM_VALUE") "100uF") (field (name "PUBLISHER") "Altium Limited"))
      (libsource (lib "Miscellaneous Devices") (part "Cap Pol3"))
    )
    (comp (ref "C_ADC")
      (value "100nF")
      (footprint "C0805")
      (description "Capacitor")
      (libsource (lib "Altium Nanoboard Project") (part "CAP"))
    )
    (comp (ref "C_DRIBBLER")
      (value "680uF")
      (footprint "CAPPR5-5x5")
      (description "Polarized Capacitor (Radial)")
      (fields (field (name "ALTIUM_VALUE") "680uF") (field (name "PUBLISHER") "Altium Limited"))
      (libsource (lib "Miscellaneous Devices") (part "Cap Pol1"))
    )
    (comp (ref "C_IR")
      (value "100nF")
      (footprint "C0805")
      (description "Capacitor")
      (libsource (lib "Altium Nanoboard Project") (part "CAP"))
    )
    (comp (ref "C_M1")
      (value "680uF")
      (footprint "CAPPR5-5x5")
      (description "Polarized Capacitor (Radial)")
      (fields (field (name "ALTIUM_VALUE") "680uF") (field (name "PUBLISHER") "Altium Limited"))
      (libsource (lib "Miscellaneous Devices") (part "Cap Pol1"))
    )
    (comp (ref "C_M2")
      (value "680uF")
      (footprint "CAPPR5-5x5")
      (description "Polarized Capacitor (Radial)")
      (fields (field (name "ALTIUM_VALUE") "680uF") (field (name "PUBLISHER") "Altium Limited"))
      (libsource (lib "Miscellaneous Devices") (part "Cap Pol1"))
    )
    (comp (ref "C_M3")
      (value "680uF")
      (footprint "CAPPR5-5x5")
      (description "Polarized Capacitor (Radial)")
      (fields (field (name "ALTIUM_VALUE") "680uF") (field (name "PUBLISHER") "Altium Limited"))
      (libsource (lib "Miscellaneous Devices") (part "Cap Pol1"))
    )
    (comp (ref "C_M4")
      (value "680uF")
      (footprint "CAPPR5-5x5")
      (description "Polarized Capacitor (Radial)")
      (fields (field (name "ALTIUM_VALUE") "680uF") (field (name "PUBLISHER") "Altium Limited"))
      (libsource (lib "Miscellaneous Devices") (part "Cap Pol1"))
    )
    (comp (ref "C_MIKONA")
      (value "680uF")
      (footprint "CAPPR5-5x5")
      (description "Polarized Capacitor (Radial)")
      (fields (field (name "ALTIUM_VALUE") "680uF") (field (name "PUBLISHER") "Altium Limited"))
      (libsource (lib "Miscellaneous Devices") (part "Cap Pol1"))
    )
    (comp (ref "D1")
      (value "LED2")
      (footprint "3.2X1.6X1.1")
      (description "Typical RED, GREEN, YELLOW, AMBER GaAs LED")
      (fields (field (name "PUBLISHER") "Altium Limited"))
      (libsource (lib "Miscellaneous Devices") (part "LED2"))
    )
    (comp (ref "D3")
      (value "LED2")
      (footprint "3.2X1.6X1.1")
      (description "Typical RED, GREEN, YELLOW, AMBER GaAs LED")
      (fields (field (name "PUBLISHER") "Altium Limited"))
      (libsource (lib "Miscellaneous Devices") (part "LED2"))
    )
    (comp (ref "D21")
      (value "LED2")
      (footprint "3.2X1.6X1.1")
      (description "Typical RED, GREEN, YELLOW, AMBER GaAs LED")
      (fields (field (name "PUBLISHER") "Altium Limited"))
      (libsource (lib "Miscellaneous Devices") (part "LED2"))
    )
    (comp (ref "D24")
      (value "LED2")
      (footprint "3.2X1.6X1.1")
      (description "Typical RED, GREEN, YELLOW, AMBER GaAs LED")
      (fields (field (name "PUBLISHER") "Altium Limited"))
      (libsource (lib "Miscellaneous Devices") (part "LED2"))
    )
    (comp (ref "Dribbler")
      (value "Header 8")
      (footprint "HDR1X8")
      (description "Header, 8-Pin")
      (fields (field (name "PUBLISHER") "Altium Limited"))
      (libsource (lib "Miscellaneous Connectors") (part "Header 8"))
    )
    (comp (ref "D_correction")
      (value "1.5KE20")
      (footprint "DO-41")
      (description "1 Amp General Purpose Rectifier")
      (fields (field (name "PUBLISHER") "Altium Limited"))
      (libsource (lib "Miscellaneous Devices") (part "Diode 1N4001"))
    )
    (comp (ref "D_Done")
      (value "LED2")
      (footprint "3.2X1.6X1.1")
      (description "Typical RED, GREEN, YELLOW, AMBER GaAs LED")
      (fields (field (name "PUBLISHER") "Altium Limited"))
      (libsource (lib "Miscellaneous Devices") (part "LED2"))
    )
    (comp (ref "D_D_1")
      (value "LED2")
      (footprint "3.2X1.6X1.1")
      (description "Typical RED, GREEN, YELLOW, AMBER GaAs LED")
      (fields (field (name "PUBLISHER") "Altium Limited"))
      (libsource (lib "Miscellaneous Devices") (part "LED2"))
    )
    (comp (ref "D_D_2")
      (value "LED2")
      (footprint "3.2X1.6X1.1")
      (description "Typical RED, GREEN, YELLOW, AMBER GaAs LED")
      (fields (field (name "PUBLISHER") "Altium Limited"))
      (libsource (lib "Miscellaneous Devices") (part "LED2"))
    )
    (comp (ref "D_D_3")
      (value "LED2")
      (footprint "3.2X1.6X1.1")
      (description "Typical RED, GREEN, YELLOW, AMBER GaAs LED")
      (fields (field (name "PUBLISHER") "Altium Limited"))
      (libsource (lib "Miscellaneous Devices") (part "LED2"))
    )
    (comp (ref "D_D_4")
      (value "LED2")
      (footprint "3.2X1.6X1.1")
      (description "Typical RED, GREEN, YELLOW, AMBER GaAs LED")
      (fields (field (name "PUBLISHER") "Altium Limited"))
      (libsource (lib "Miscellaneous Devices") (part "LED2"))
    )
    (comp (ref "D_REV")
      (value "LED2")
      (footprint "3.2X1.6X1.1")
      (description "Typical RED, GREEN, YELLOW, AMBER GaAs LED")
      (fields (field (name "PUBLISHER") "Altium Limited"))
      (libsource (lib "Miscellaneous Devices") (part "LED2"))
    )
    (comp (ref "e1")
      (value "Header 4")
      (footprint "HDR1X4")
      (description "Header, 4-Pin")
      (fields (field (name "PUBLISHER") "Altium Limited"))
      (libsource (lib "") (part "Header 4_2"))
    )
    (comp (ref "e2")
      (value "Header 4")
      (footprint "HDR1X4")
      (description "Header, 4-Pin")
      (fields (field (name "PUBLISHER") "Altium Limited"))
      (libsource (lib "") (part "Header 4_2"))
    )
    (comp (ref "e3")
      (value "Header 4")
      (footprint "HDR1X4")
      (description "Header, 4-Pin")
      (fields (field (name "PUBLISHER") "Altium Limited"))
      (libsource (lib "") (part "Header 4_2"))
    )
    (comp (ref "e4")
      (value "Header 4")
      (footprint "HDR1X4")
      (description "Header, 4-Pin")
      (fields (field (name "PUBLISHER") "Altium Limited"))
      (libsource (lib "") (part "Header 4_2"))
    )
    (comp (ref "Gyro & Accel")
      (value "ITG-3200/BMA180")
      (footprint "HDR2X8")
      (description "Header, 8-Pin, Dual row")
      (fields (field (name "PUBLISHER") "Altium Limited"))
      (libsource (lib "Miscellaneous Connectors") (part "Header 8X2"))
    )
    (comp (ref "MinMax")
      (value "MIW5022")
      (footprint "PcbLib1:MIW5000")
      (description "Header, 12-Pin, Dual row")
      (fields (field (name "PUBLISHER") "Altium Limited"))
      (libsource (lib "Miscellaneous Connectors") (part "Header 12X2"))
    )
    (comp (ref "MOTOR_1")
      (value "Header 8")
      (footprint "HDR1X8")
      (description "Header, 8-Pin")
      (fields (field (name "PUBLISHER") "Altium Limited"))
      (libsource (lib "Miscellaneous Connectors") (part "Header 8"))
    )
    (comp (ref "MOTOR_2")
      (value "Header 8")
      (footprint "HDR1X8")
      (description "Header, 8-Pin")
      (fields (field (name "PUBLISHER") "Altium Limited"))
      (libsource (lib "Miscellaneous Connectors") (part "Header 8"))
    )
    (comp (ref "MOTOR_3")
      (value "Header 8")
      (footprint "HDR1X8")
      (description "Header, 8-Pin")
      (fields (field (name "PUBLISHER") "Altium Limited"))
      (libsource (lib "Miscellaneous Connectors") (part "Header 8"))
    )
    (comp (ref "MOTOR_4")
      (value "Header 8")
      (footprint "HDR1X8")
      (description "Header, 8-Pin")
      (fields (field (name "PUBLISHER") "Altium Limited"))
      (libsource (lib "Miscellaneous Connectors") (part "Header 8"))
    )
    (comp (ref "nRF")
      (value "Header 8")
      (footprint "HDR1X8")
      (description "Header, 8-Pin")
      (fields (field (name "PUBLISHER") "Altium Limited"))
      (libsource (lib "Miscellaneous Connectors") (part "Header 8"))
    )
    (comp (ref "P1")
      (value "Header 3")
      (footprint "HDR1X3")
      (description "Header, 3-Pin")
      (fields (field (name "PUBLISHER") "Altium Limited"))
      (libsource (lib "Miscellaneous Connectors") (part "Header 3"))
    )
    (comp (ref "P2")
      (value "Header 4")
      (footprint "HDR1X4")
      (description "Header, 4-Pin")
      (fields (field (name "PUBLISHER") "Altium Limited"))
      (libsource (lib "Miscellaneous Connectors") (part "Header 4"))
    )
    (comp (ref "P13")
      (value "Header 6")
      (footprint "HDR1X6")
      (description "Header, 6-Pin")
      (fields (field (name "PUBLISHER") "Altium Limited"))
      (libsource (lib "Miscellaneous Connectors") (part "Header 6"))
    )
    (comp (ref "P16")
      (value "Kolangi")
      (footprint "PcbLib1:Kolang")
      (description "Header, 3-Pin, Dual row")
      (fields (field (name "PUBLISHER") "Altium Limited"))
      (libsource (lib "Miscellaneous Connectors") (part "Header 3X2"))
    )
    (comp (ref "Q1")
      (value "FDS4435")
      (footprint "SO-8_L")
      (description "HEXFET Power MOSFET")
      (fields (field (name "PUBLISHER") "Altium Limited"))
      (libsource (lib "IR Discrete MOSFET - Power") (part "IRF7204"))
    )
    (comp (ref "Q2")
      (value "FDD4410")
      (footprint "SO-8_L")
      (description "HEXFET Power MOSFET")
      (fields (field (name "PUBLISHER") "Altium Limited"))
      (libsource (lib "IR Discrete MOSFET - Power") (part "IRF7201"))
    )
    (comp (ref "Q3")
      (value "FDS4435")
      (footprint "SO-8_L")
      (description "HEXFET Power MOSFET")
      (fields (field (name "PUBLISHER") "Altium Limited"))
      (libsource (lib "IR Discrete MOSFET - Power") (part "IRF7204"))
    )
    (comp (ref "Q4")
      (value "FDD4410")
      (footprint "SO-8_L")
      (description "HEXFET Power MOSFET")
      (fields (field (name "PUBLISHER") "Altium Limited"))
      (libsource (lib "IR Discrete MOSFET - Power") (part "IRF7201"))
    )
    (comp (ref "Q5")
      (value "FDS4435")
      (footprint "SO-8_L")
      (description "HEXFET Power MOSFET")
      (fields (field (name "PUBLISHER") "Altium Limited"))
      (libsource (lib "IR Discrete MOSFET - Power") (part "IRF7204"))
    )
    (comp (ref "Q6")
      (value "FDD4410")
      (footprint "SO-8_L")
      (description "HEXFET Power MOSFET")
      (fields (field (name "PUBLISHER") "Altium Limited"))
      (libsource (lib "IR Discrete MOSFET - Power") (part "IRF7201"))
    )
    (comp (ref "Q7")
      (value "FDS4435")
      (footprint "SO-8_L")
      (description "HEXFET Power MOSFET")
      (fields (field (name "PUBLISHER") "Altium Limited"))
      (libsource (lib "IR Discrete MOSFET - Power") (part "IRF7204"))
    )
    (comp (ref "Q8")
      (value "FDS4435")
      (footprint "SO-8_L")
      (description "HEXFET Power MOSFET")
      (fields (field (name "PUBLISHER") "Altium Limited"))
      (libsource (lib "IR Discrete MOSFET - Power") (part "IRF7204"))
    )
    (comp (ref "Q9")
      (value "FDD4410")
      (footprint "SO-8_L")
      (description "HEXFET Power MOSFET")
      (fields (field (name "PUBLISHER") "Altium Limited"))
      (libsource (lib "IR Discrete MOSFET - Power") (part "IRF7201"))
    )
    (comp (ref "Q10")
      (value "FDD4410")
      (footprint "SO-8_L")
      (description "HEXFET Power MOSFET")
      (fields (field (name "PUBLISHER") "Altium Limited"))
      (libsource (lib "IR Discrete MOSFET - Power") (part "IRF7201"))
    )
    (comp (ref "Q11")
      (value "FDS4435")
      (footprint "SO-8_L")
      (description "HEXFET Power MOSFET")
      (fields (field (name "PUBLISHER") "Altium Limited"))
      (libsource (lib "IR Discrete MOSFET - Power") (part "IRF7204"))
    )
    (comp (ref "Q12")
      (value "FDS4435")
      (footprint "SO-8_L")
      (description "HEXFET Power MOSFET")
      (fields (field (name "PUBLISHER") "Altium Limited"))
      (libsource (lib "IR Discrete MOSFET - Power") (part "IRF7204"))
    )
    (comp (ref "Q13")
      (value "FDD4410")
      (footprint "SO-8_L")
      (description "HEXFET Power MOSFET")
      (fields (field (name "PUBLISHER") "Altium Limited"))
      (libsource (lib "IR Discrete MOSFET - Power") (part "IRF7201"))
    )
    (comp (ref "Q14")
      (value "FDD4410")
      (footprint "SO-8_L")
      (description "HEXFET Power MOSFET")
      (fields (field (name "PUBLISHER") "Altium Limited"))
      (libsource (lib "IR Discrete MOSFET - Power") (part "IRF7201"))
    )
    (comp (ref "Q15")
      (value "FDS4435")
      (footprint "SO-8_L")
      (description "HEXFET Power MOSFET")
      (fields (field (name "PUBLISHER") "Altium Limited"))
      (libsource (lib "IR Discrete MOSFET - Power") (part "IRF7204"))
    )
    (comp (ref "Q16")
      (value "FDS4435")
      (footprint "SO-8_L")
      (description "HEXFET Power MOSFET")
      (fields (field (name "PUBLISHER") "Altium Limited"))
      (libsource (lib "IR Discrete MOSFET - Power") (part "IRF7204"))
    )
    (comp (ref "Q17")
      (value "FDD4410")
      (footprint "SO-8_L")
      (description "HEXFET Power MOSFET")
      (fields (field (name "PUBLISHER") "Altium Limited"))
      (libsource (lib "IR Discrete MOSFET - Power") (part "IRF7201"))
    )
    (comp (ref "Q18")
      (value "FDD4410")
      (footprint "SO-8_L")
      (description "HEXFET Power MOSFET")
      (fields (field (name "PUBLISHER") "Altium Limited"))
      (libsource (lib "IR Discrete MOSFET - Power") (part "IRF7201"))
    )
    (comp (ref "Q19")
      (value "FDS4435")
      (footprint "SO-8_L")
      (description "HEXFET Power MOSFET")
      (fields (field (name "PUBLISHER") "Altium Limited"))
      (libsource (lib "IR Discrete MOSFET - Power") (part "IRF7204"))
    )
    (comp (ref "Q20")
      (value "FDS4435")
      (footprint "SO-8_L")
      (description "HEXFET Power MOSFET")
      (fields (field (name "PUBLISHER") "Altium Limited"))
      (libsource (lib "IR Discrete MOSFET - Power") (part "IRF7204"))
    )
    (comp (ref "Q21")
      (value "FDD4410")
      (footprint "SO-8_L")
      (description "HEXFET Power MOSFET")
      (fields (field (name "PUBLISHER") "Altium Limited"))
      (libsource (lib "IR Discrete MOSFET - Power") (part "IRF7201"))
    )
    (comp (ref "Q22")
      (value "FDD4410")
      (footprint "SO-8_L")
      (description "HEXFET Power MOSFET")
      (fields (field (name "PUBLISHER") "Altium Limited"))
      (libsource (lib "IR Discrete MOSFET - Power") (part "IRF7201"))
    )
    (comp (ref "Q23")
      (value "FDS4435")
      (footprint "SO-8_L")
      (description "HEXFET Power MOSFET")
      (fields (field (name "PUBLISHER") "Altium Limited"))
      (libsource (lib "IR Discrete MOSFET - Power") (part "IRF7204"))
    )
    (comp (ref "Q24")
      (value "FDS4435")
      (footprint "SO-8_L")
      (description "HEXFET Power MOSFET")
      (fields (field (name "PUBLISHER") "Altium Limited"))
      (libsource (lib "IR Discrete MOSFET - Power") (part "IRF7204"))
    )
    (comp (ref "Q25")
      (value "FDD4410")
      (footprint "SO-8_L")
      (description "HEXFET Power MOSFET")
      (fields (field (name "PUBLISHER") "Altium Limited"))
      (libsource (lib "IR Discrete MOSFET - Power") (part "IRF7201"))
    )
    (comp (ref "Q26")
      (value "FDD4410")
      (footprint "SO-8_L")
      (description "HEXFET Power MOSFET")
      (fields (field (name "PUBLISHER") "Altium Limited"))
      (libsource (lib "IR Discrete MOSFET - Power") (part "IRF7201"))
    )
    (comp (ref "Q27")
      (value "FDS4435")
      (footprint "SO-8_L")
      (description "HEXFET Power MOSFET")
      (fields (field (name "PUBLISHER") "Altium Limited"))
      (libsource (lib "IR Discrete MOSFET - Power") (part "IRF7204"))
    )
    (comp (ref "Q28")
      (value "FDS4435")
      (footprint "SO-8_L")
      (description "HEXFET Power MOSFET")
      (fields (field (name "PUBLISHER") "Altium Limited"))
      (libsource (lib "IR Discrete MOSFET - Power") (part "IRF7204"))
    )
    (comp (ref "Q29")
      (value "FDD4410")
      (footprint "SO-8_L")
      (description "HEXFET Power MOSFET")
      (fields (field (name "PUBLISHER") "Altium Limited"))
      (libsource (lib "IR Discrete MOSFET - Power") (part "IRF7201"))
    )
    (comp (ref "Q30")
      (value "FDD4410")
      (footprint "SO-8_L")
      (description "HEXFET Power MOSFET")
      (fields (field (name "PUBLISHER") "Altium Limited"))
      (libsource (lib "IR Discrete MOSFET - Power") (part "IRF7201"))
    )
    (comp (ref "Q_BUZZ")
      (value "MMBTA14")
      (footprint "SOT23_N")
      (description "NPN Darlington Transistor")
      (fields (field (name "PUBLISHER") "Altium Limited"))
      (libsource (lib "Philips Discrete BJT - Darlington") (part "PMBTA14"))
    )
    (comp (ref "R(rst)")
      (value "1K")
      (footprint "Miscellaneous Devices:2012[0805]")
      (description "Resistor")
      (fields (field (name "ALTIUM_VALUE") "1K") (field (name "PUBLISHER") "Altium Limited"))
      (libsource (lib "Miscellaneous Devices") (part "Res1"))
    )
    (comp (ref "R1")
      (value "1K")
      (footprint "Miscellaneous Devices:2012[0805]")
      (description "Resistor")
      (fields (field (name "ALTIUM_VALUE") "1K") (field (name "PUBLISHER") "Altium Limited"))
      (libsource (lib "") (part "Res2_1"))
    )
    (comp (ref "R2")
      (value "200")
      (footprint "1608[0603]")
      (description "Semiconductor Resistor")
      (fields (field (name "ALTIUM_VALUE") "200") (field (name "PUBLISHER") "Altium Limited"))
      (libsource (lib "Miscellaneous Devices") (part "Res Semi"))
    )
    (comp (ref "R2.5")
      (value "82")
      (footprint "3216[1206]")
      (description "Semiconductor Resistor")
      (fields (field (name "ALTIUM_VALUE") "82") (field (name "PUBLISHER") "Altium Limited"))
      (libsource (lib "Miscellaneous Devices") (part "Res Semi"))
    )
    (comp (ref "R3")
      (value "1K")
      (footprint "Miscellaneous Devices:2012[0805]")
      (description "Resistor")
      (fields (field (name "ALTIUM_VALUE") "1K") (field (name "PUBLISHER") "Altium Limited"))
      (libsource (lib "Miscellaneous Devices") (part "Res2"))
    )
    (comp (ref "R4")
      (value "200")
      (footprint "1608[0603]")
      (description "Semiconductor Resistor")
      (fields (field (name "ALTIUM_VALUE") "200") (field (name "PUBLISHER") "Altium Limited"))
      (libsource (lib "Miscellaneous Devices") (part "Res Semi"))
    )
    (comp (ref "R5")
      (value "200")
      (footprint "1608[0603]")
      (description "Semiconductor Resistor")
      (fields (field (name "ALTIUM_VALUE") "200") (field (name "PUBLISHER") "Altium Limited"))
      (libsource (lib "Miscellaneous Devices") (part "Res Semi"))
    )
    (comp (ref "R6")
      (value "200")
      (footprint "1608[0603]")
      (description "Semiconductor Resistor")
      (fields (field (name "ALTIUM_VALUE") "200") (field (name "PUBLISHER") "Altium Limited"))
      (libsource (lib "Miscellaneous Devices") (part "Res Semi"))
    )
    (comp (ref "R7")
      (value "200")
      (footprint "1608[0603]")
      (description "Semiconductor Resistor")
      (fields (field (name "ALTIUM_VALUE") "200") (field (name "PUBLISHER") "Altium Limited"))
      (libsource (lib "Miscellaneous Devices") (part "Res Semi"))
    )
    (comp (ref "R8")
      (value "200")
      (footprint "1608[0603]")
      (description "Semiconductor Resistor")
      (fields (field (name "ALTIUM_VALUE") "200") (field (name "PUBLISHER") "Altium Limited"))
      (libsource (lib "Miscellaneous Devices") (part "Res Semi"))
    )
    (comp (ref "R9")
      (value "200")
      (footprint "1608[0603]")
      (description "Semiconductor Resistor")
      (fields (field (name "ALTIUM_VALUE") "200") (field (name "PUBLISHER") "Altium Limited"))
      (libsource (lib "Miscellaneous Devices") (part "Res Semi"))
    )
    (comp (ref "R10")
      (value "200")
      (footprint "1608[0603]")
      (description "Semiconductor Resistor")
      (fields (field (name "ALTIUM_VALUE") "200") (field (name "PUBLISHER") "Altium Limited"))
      (libsource (lib "Miscellaneous Devices") (part "Res Semi"))
    )
    (comp (ref "R11")
      (value "200")
      (footprint "1608[0603]")
      (description "Semiconductor Resistor")
      (fields (field (name "ALTIUM_VALUE") "200") (field (name "PUBLISHER") "Altium Limited"))
      (libsource (lib "Miscellaneous Devices") (part "Res Semi"))
    )
    (comp (ref "R12")
      (value "200")
      (footprint "1608[0603]")
      (description "Semiconductor Resistor")
      (fields (field (name "ALTIUM_VALUE") "200") (field (name "PUBLISHER") "Altium Limited"))
      (libsource (lib "Miscellaneous Devices") (part "Res Semi"))
    )
    (comp (ref "R13")
      (value "200")
      (footprint "1608[0603]")
      (description "Semiconductor Resistor")
      (fields (field (name "ALTIUM_VALUE") "200") (field (name "PUBLISHER") "Altium Limited"))
      (libsource (lib "Miscellaneous Devices") (part "Res Semi"))
    )
    (comp (ref "R14")
      (value "200")
      (footprint "1608[0603]")
      (description "Semiconductor Resistor")
      (fields (field (name "ALTIUM_VALUE") "200") (field (name "PUBLISHER") "Altium Limited"))
      (libsource (lib "Miscellaneous Devices") (part "Res Semi"))
    )
    (comp (ref "R15")
      (value "200")
      (footprint "1608[0603]")
      (description "Semiconductor Resistor")
      (fields (field (name "ALTIUM_VALUE") "200") (field (name "PUBLISHER") "Altium Limited"))
      (libsource (lib "Miscellaneous Devices") (part "Res Semi"))
    )
    (comp (ref "R16")
      (value "200")
      (footprint "1608[0603]")
      (description "Semiconductor Resistor")
      (fields (field (name "ALTIUM_VALUE") "200") (field (name "PUBLISHER") "Altium Limited"))
      (libsource (lib "Miscellaneous Devices") (part "Res Semi"))
    )
    (comp (ref "R17")
      (value "200")
      (footprint "1608[0603]")
      (description "Semiconductor Resistor")
      (fields (field (name "ALTIUM_VALUE") "200") (field (name "PUBLISHER") "Altium Limited"))
      (libsource (lib "Miscellaneous Devices") (part "Res Semi"))
    )
    (comp (ref "R18")
      (value "200")
      (footprint "1608[0603]")
      (description "Semiconductor Resistor")
      (fields (field (name "ALTIUM_VALUE") "200") (field (name "PUBLISHER") "Altium Limited"))
      (libsource (lib "Miscellaneous Devices") (part "Res Semi"))
    )
    (comp (ref "R19")
      (value "200")
      (footprint "1608[0603]")
      (description "Semiconductor Resistor")
      (fields (field (name "ALTIUM_VALUE") "200") (field (name "PUBLISHER") "Altium Limited"))
      (libsource (lib "Miscellaneous Devices") (part "Res Semi"))
    )
    (comp (ref "R20")
      (value "200")
      (footprint "1608[0603]")
      (description "Semiconductor Resistor")
      (fields (field (name "ALTIUM_VALUE") "200") (field (name "PUBLISHER") "Altium Limited"))
      (libsource (lib "Miscellaneous Devices") (part "Res Semi"))
    )
    (comp (ref "R21")
      (value "1K")
      (footprint "Miscellaneous Devices:2012[0805]")
      (description "Resistor")
      (fields (field (name "ALTIUM_VALUE") "1K") (field (name "PUBLISHER") "Altium Limited"))
      (libsource (lib "Miscellaneous Devices") (part "Res2"))
    )
    (comp (ref "R22")
      (value "200")
      (footprint "2012[0805]")
      (description "Semiconductor Resistor")
      (fields (field (name "ALTIUM_VALUE") "200") (field (name "PUBLISHER") "Altium Limited"))
      (libsource (lib "Miscellaneous Devices") (part "Res Semi"))
    )
    (comp (ref "R23")
      (value "200")
      (footprint "1608[0603]")
      (description "Semiconductor Resistor")
      (fields (field (name "ALTIUM_VALUE") "200") (field (name "PUBLISHER") "Altium Limited"))
      (libsource (lib "Miscellaneous Devices") (part "Res Semi"))
    )
    (comp (ref "R24")
      (value "1K")
      (footprint "Miscellaneous Devices:2012[0805]")
      (description "Resistor")
      (fields (field (name "ALTIUM_VALUE") "1K") (field (name "PUBLISHER") "Altium Limited"))
      (libsource (lib "Miscellaneous Devices") (part "Res2"))
    )
    (comp (ref "R25")
      (value "200")
      (footprint "1608[0603]")
      (description "Semiconductor Resistor")
      (fields (field (name "ALTIUM_VALUE") "200") (field (name "PUBLISHER") "Altium Limited"))
      (libsource (lib "Miscellaneous Devices") (part "Res Semi"))
    )
    (comp (ref "R26")
      (value "200")
      (footprint "1608[0603]")
      (description "Semiconductor Resistor")
      (fields (field (name "ALTIUM_VALUE") "200") (field (name "PUBLISHER") "Altium Limited"))
      (libsource (lib "Miscellaneous Devices") (part "Res Semi"))
    )
    (comp (ref "R27")
      (value "200")
      (footprint "1608[0603]")
      (description "Semiconductor Resistor")
      (fields (field (name "ALTIUM_VALUE") "200") (field (name "PUBLISHER") "Altium Limited"))
      (libsource (lib "Miscellaneous Devices") (part "Res Semi"))
    )
    (comp (ref "R28")
      (value "200")
      (footprint "1608[0603]")
      (description "Semiconductor Resistor")
      (fields (field (name "ALTIUM_VALUE") "200") (field (name "PUBLISHER") "Altium Limited"))
      (libsource (lib "Miscellaneous Devices") (part "Res Semi"))
    )
    (comp (ref "R29")
      (value "200")
      (footprint "1608[0603]")
      (description "Semiconductor Resistor")
      (fields (field (name "ALTIUM_VALUE") "200") (field (name "PUBLISHER") "Altium Limited"))
      (libsource (lib "Miscellaneous Devices") (part "Res Semi"))
    )
    (comp (ref "R30")
      (value "200")
      (footprint "1608[0603]")
      (description "Semiconductor Resistor")
      (fields (field (name "ALTIUM_VALUE") "200") (field (name "PUBLISHER") "Altium Limited"))
      (libsource (lib "Miscellaneous Devices") (part "Res Semi"))
    )
    (comp (ref "R31")
      (value "100")
      (footprint "2012[0805]")
      (description "Semiconductor Resistor")
      (fields (field (name "ALTIUM_VALUE") "100") (field (name "PUBLISHER") "Altium Limited"))
      (libsource (lib "Miscellaneous Devices") (part "Res Semi"))
    )
    (comp (ref "R32")
      (value "4.7K")
      (footprint "2012[0805]")
      (description "Semiconductor Resistor")
      (fields (field (name "ALTIUM_VALUE") "4.7K") (field (name "PUBLISHER") "Altium Limited"))
      (libsource (lib "Miscellaneous Devices") (part "Res Semi"))
    )
    (comp (ref "R33")
      (value "4.7K")
      (footprint "2012[0805]")
      (description "Semiconductor Resistor")
      (fields (field (name "ALTIUM_VALUE") "4.7K") (field (name "PUBLISHER") "Altium Limited"))
      (libsource (lib "Miscellaneous Devices") (part "Res Semi"))
    )
    (comp (ref "R34")
      (value "330")
      (footprint "2012[0805]")
      (description "Semiconductor Resistor")
      (fields (field (name "ALTIUM_VALUE") "330") (field (name "PUBLISHER") "Altium Limited"))
      (libsource (lib "Miscellaneous Devices") (part "Res Semi"))
    )
    (comp (ref "R35")
      (value "200")
      (footprint "1608[0603]")
      (description "Semiconductor Resistor")
      (fields (field (name "ALTIUM_VALUE") "200") (field (name "PUBLISHER") "Altium Limited"))
      (libsource (lib "Miscellaneous Devices") (part "Res Semi"))
    )
    (comp (ref "R36")
      (value "200")
      (footprint "1608[0603]")
      (description "Semiconductor Resistor")
      (fields (field (name "ALTIUM_VALUE") "200") (field (name "PUBLISHER") "Altium Limited"))
      (libsource (lib "Miscellaneous Devices") (part "Res Semi"))
    )
    (comp (ref "R37")
      (value "200")
      (footprint "1608[0603]")
      (description "Semiconductor Resistor")
      (fields (field (name "ALTIUM_VALUE") "200") (field (name "PUBLISHER") "Altium Limited"))
      (libsource (lib "Miscellaneous Devices") (part "Res Semi"))
    )
    (comp (ref "R38")
      (value "200")
      (footprint "1608[0603]")
      (description "Semiconductor Resistor")
      (fields (field (name "ALTIUM_VALUE") "200") (field (name "PUBLISHER") "Altium Limited"))
      (libsource (lib "Miscellaneous Devices") (part "Res Semi"))
    )
    (comp (ref "R39")
      (value "200")
      (footprint "1608[0603]")
      (description "Semiconductor Resistor")
      (fields (field (name "ALTIUM_VALUE") "200") (field (name "PUBLISHER") "Altium Limited"))
      (libsource (lib "Miscellaneous Devices") (part "Res Semi"))
    )
    (comp (ref "R40")
      (value "1K")
      (footprint "1608[0603]")
      (description "Semiconductor Resistor")
      (fields (field (name "ALTIUM_VALUE") "1K") (field (name "PUBLISHER") "Altium Limited"))
      (libsource (lib "Miscellaneous Devices") (part "Res Semi"))
    )
    (comp (ref "R41")
      (value "1K")
      (footprint "1608[0603]")
      (description "Semiconductor Resistor")
      (fields (field (name "ALTIUM_VALUE") "1K") (field (name "PUBLISHER") "Altium Limited"))
      (libsource (lib "Miscellaneous Devices") (part "Res Semi"))
    )
    (comp (ref "R42")
      (value "1K")
      (footprint "1608[0603]")
      (description "Semiconductor Resistor")
      (fields (field (name "ALTIUM_VALUE") "1K") (field (name "PUBLISHER") "Altium Limited"))
      (libsource (lib "Miscellaneous Devices") (part "Res Semi"))
    )
    (comp (ref "R43")
      (value "27K")
      (footprint "Miscellaneous Devices:2012[0805]")
      (description "Resistor")
      (fields (field (name "ALTIUM_VALUE") "27K") (field (name "PUBLISHER") "Altium Limited"))
      (libsource (lib "Miscellaneous Devices") (part "Res2"))
    )
    (comp (ref "R44")
      (value "2.2K")
      (footprint "2012[0805]")
      (description "Semiconductor Resistor")
      (fields (field (name "ALTIUM_VALUE") "2.2K") (field (name "PUBLISHER") "Altium Limited"))
      (libsource (lib "Miscellaneous Devices") (part "Res Semi"))
    )
    (comp (ref "R45")
      (value "3.6K")
      (footprint "Miscellaneous Devices:2012[0805]")
      (description "Resistor")
      (fields (field (name "ALTIUM_VALUE") "3.6K") (field (name "PUBLISHER") "Altium Limited"))
      (libsource (lib "Miscellaneous Devices") (part "Res2"))
    )
    (comp (ref "R46")
      (value "390")
      (footprint "3216[1206]")
      (description "Semiconductor Resistor")
      (fields (field (name "ALTIUM_VALUE") "390") (field (name "PUBLISHER") "Altium Limited"))
      (libsource (lib "Miscellaneous Devices") (part "Res Semi"))
    )
    (comp (ref "R47")
      (value "50")
      (footprint "1608[0603]")
      (description "Semiconductor Resistor")
      (fields (field (name "ALTIUM_VALUE") "50") (field (name "PUBLISHER") "Altium Limited"))
      (libsource (lib "Miscellaneous Devices") (part "Res Semi"))
    )
    (comp (ref "R48")
      (value "50")
      (footprint "1608[0603]")
      (description "Semiconductor Resistor")
      (fields (field (name "ALTIUM_VALUE") "50") (field (name "PUBLISHER") "Altium Limited"))
      (libsource (lib "Miscellaneous Devices") (part "Res Semi"))
    )
    (comp (ref "R49")
      (value "50")
      (footprint "1608[0603]")
      (description "Semiconductor Resistor")
      (fields (field (name "ALTIUM_VALUE") "50") (field (name "PUBLISHER") "Altium Limited"))
      (libsource (lib "Miscellaneous Devices") (part "Res Semi"))
    )
    (comp (ref "R50")
      (value "50")
      (footprint "1608[0603]")
      (description "Semiconductor Resistor")
      (fields (field (name "ALTIUM_VALUE") "50") (field (name "PUBLISHER") "Altium Limited"))
      (libsource (lib "Miscellaneous Devices") (part "Res Semi"))
    )
    (comp (ref "R51")
      (value "50")
      (footprint "1608[0603]")
      (description "Semiconductor Resistor")
      (fields (field (name "ALTIUM_VALUE") "50") (field (name "PUBLISHER") "Altium Limited"))
      (libsource (lib "Miscellaneous Devices") (part "Res Semi"))
    )
    (comp (ref "R52")
      (value "50")
      (footprint "1608[0603]")
      (description "Semiconductor Resistor")
      (fields (field (name "ALTIUM_VALUE") "50") (field (name "PUBLISHER") "Altium Limited"))
      (libsource (lib "Miscellaneous Devices") (part "Res Semi"))
    )
    (comp (ref "R53")
      (value "10K")
      (footprint "1608[0603]")
      (description "Semiconductor Resistor")
      (fields (field (name "ALTIUM_VALUE") "10K") (field (name "PUBLISHER") "Altium Limited"))
      (libsource (lib "Miscellaneous Devices") (part "Res Semi"))
    )
    (comp (ref "R54")
      (value "10K")
      (footprint "1608[0603]")
      (description "Semiconductor Resistor")
      (fields (field (name "ALTIUM_VALUE") "10K") (field (name "PUBLISHER") "Altium Limited"))
      (libsource (lib "Miscellaneous Devices") (part "Res Semi"))
    )
    (comp (ref "R55")
      (value "2.2K")
      (footprint "2012[0805]")
      (description "Semiconductor Resistor")
      (fields (field (name "ALTIUM_VALUE") "2.2K") (field (name "PUBLISHER") "Altium Limited"))
      (libsource (lib "Miscellaneous Devices") (part "Res Semi"))
    )
    (comp (ref "R56")
      (value "10K")
      (footprint "1608[0603]")
      (description "Semiconductor Resistor")
      (fields (field (name "ALTIUM_VALUE") "10K") (field (name "PUBLISHER") "Altium Limited"))
      (libsource (lib "Miscellaneous Devices") (part "Res Semi"))
    )
    (comp (ref "R57")
      (value "10K")
      (footprint "1608[0603]")
      (description "Semiconductor Resistor")
      (fields (field (name "ALTIUM_VALUE") "10K") (field (name "PUBLISHER") "Altium Limited"))
      (libsource (lib "Miscellaneous Devices") (part "Res Semi"))
    )
    (comp (ref "R58")
      (value "10K")
      (footprint "1608[0603]")
      (description "Semiconductor Resistor")
      (fields (field (name "ALTIUM_VALUE") "10K") (field (name "PUBLISHER") "Altium Limited"))
      (libsource (lib "Miscellaneous Devices") (part "Res Semi"))
    )
    (comp (ref "R59")
      (value "50")
      (footprint "1608[0603]")
      (description "Semiconductor Resistor")
      (fields (field (name "ALTIUM_VALUE") "50") (field (name "PUBLISHER") "Altium Limited"))
      (libsource (lib "Miscellaneous Devices") (part "Res Semi"))
    )
    (comp (ref "R60")
      (value "50")
      (footprint "1608[0603]")
      (description "Semiconductor Resistor")
      (fields (field (name "ALTIUM_VALUE") "50") (field (name "PUBLISHER") "Altium Limited"))
      (libsource (lib "Miscellaneous Devices") (part "Res Semi"))
    )
    (comp (ref "R61")
      (value "50")
      (footprint "1608[0603]")
      (description "Semiconductor Resistor")
      (fields (field (name "ALTIUM_VALUE") "50") (field (name "PUBLISHER") "Altium Limited"))
      (libsource (lib "Miscellaneous Devices") (part "Res Semi"))
    )
    (comp (ref "R62")
      (value "50")
      (footprint "1608[0603]")
      (description "Semiconductor Resistor")
      (fields (field (name "ALTIUM_VALUE") "50") (field (name "PUBLISHER") "Altium Limited"))
      (libsource (lib "Miscellaneous Devices") (part "Res Semi"))
    )
    (comp (ref "R63")
      (value "10K")
      (footprint "1608[0603]")
      (description "Semiconductor Resistor")
      (fields (field (name "ALTIUM_VALUE") "10K") (field (name "PUBLISHER") "Altium Limited"))
      (libsource (lib "Miscellaneous Devices") (part "Res Semi"))
    )
    (comp (ref "R64")
      (value "10K")
      (footprint "1608[0603]")
      (description "Semiconductor Resistor")
      (fields (field (name "ALTIUM_VALUE") "10K") (field (name "PUBLISHER") "Altium Limited"))
      (libsource (lib "Miscellaneous Devices") (part "Res Semi"))
    )
    (comp (ref "R65")
      (value "50")
      (footprint "1608[0603]")
      (description "Semiconductor Resistor")
      (fields (field (name "ALTIUM_VALUE") "50") (field (name "PUBLISHER") "Altium Limited"))
      (libsource (lib "Miscellaneous Devices") (part "Res Semi"))
    )
    (comp (ref "R66")
      (value "50")
      (footprint "1608[0603]")
      (description "Semiconductor Resistor")
      (fields (field (name "ALTIUM_VALUE") "50") (field (name "PUBLISHER") "Altium Limited"))
      (libsource (lib "Miscellaneous Devices") (part "Res Semi"))
    )
    (comp (ref "R67")
      (value "50")
      (footprint "1608[0603]")
      (description "Semiconductor Resistor")
      (fields (field (name "ALTIUM_VALUE") "50") (field (name "PUBLISHER") "Altium Limited"))
      (libsource (lib "Miscellaneous Devices") (part "Res Semi"))
    )
    (comp (ref "R68")
      (value "50")
      (footprint "1608[0603]")
      (description "Semiconductor Resistor")
      (fields (field (name "ALTIUM_VALUE") "50") (field (name "PUBLISHER") "Altium Limited"))
      (libsource (lib "Miscellaneous Devices") (part "Res Semi"))
    )
    (comp (ref "R69")
      (value "10K")
      (footprint "1608[0603]")
      (description "Semiconductor Resistor")
      (fields (field (name "ALTIUM_VALUE") "10K") (field (name "PUBLISHER") "Altium Limited"))
      (libsource (lib "Miscellaneous Devices") (part "Res Semi"))
    )
    (comp (ref "R70")
      (value "10K")
      (footprint "1608[0603]")
      (description "Semiconductor Resistor")
      (fields (field (name "ALTIUM_VALUE") "10K") (field (name "PUBLISHER") "Altium Limited"))
      (libsource (lib "Miscellaneous Devices") (part "Res Semi"))
    )
    (comp (ref "R71")
      (value "50")
      (footprint "1608[0603]")
      (description "Semiconductor Resistor")
      (fields (field (name "ALTIUM_VALUE") "50") (field (name "PUBLISHER") "Altium Limited"))
      (libsource (lib "Miscellaneous Devices") (part "Res Semi"))
    )
    (comp (ref "R72")
      (value "50")
      (footprint "1608[0603]")
      (description "Semiconductor Resistor")
      (fields (field (name "ALTIUM_VALUE") "50") (field (name "PUBLISHER") "Altium Limited"))
      (libsource (lib "Miscellaneous Devices") (part "Res Semi"))
    )
    (comp (ref "R73")
      (value "50")
      (footprint "1608[0603]")
      (description "Semiconductor Resistor")
      (fields (field (name "ALTIUM_VALUE") "50") (field (name "PUBLISHER") "Altium Limited"))
      (libsource (lib "Miscellaneous Devices") (part "Res Semi"))
    )
    (comp (ref "R74")
      (value "50")
      (footprint "1608[0603]")
      (description "Semiconductor Resistor")
      (fields (field (name "ALTIUM_VALUE") "50") (field (name "PUBLISHER") "Altium Limited"))
      (libsource (lib "Miscellaneous Devices") (part "Res Semi"))
    )
    (comp (ref "R75")
      (value "10K")
      (footprint "1608[0603]")
      (description "Semiconductor Resistor")
      (fields (field (name "ALTIUM_VALUE") "10K") (field (name "PUBLISHER") "Altium Limited"))
      (libsource (lib "Miscellaneous Devices") (part "Res Semi"))
    )
    (comp (ref "R76")
      (value "10K")
      (footprint "1608[0603]")
      (description "Semiconductor Resistor")
      (fields (field (name "ALTIUM_VALUE") "10K") (field (name "PUBLISHER") "Altium Limited"))
      (libsource (lib "Miscellaneous Devices") (part "Res Semi"))
    )
    (comp (ref "R77")
      (value "50")
      (footprint "1608[0603]")
      (description "Semiconductor Resistor")
      (fields (field (name "ALTIUM_VALUE") "50") (field (name "PUBLISHER") "Altium Limited"))
      (libsource (lib "Miscellaneous Devices") (part "Res Semi"))
    )
    (comp (ref "R78")
      (value "50")
      (footprint "1608[0603]")
      (description "Semiconductor Resistor")
      (fields (field (name "ALTIUM_VALUE") "50") (field (name "PUBLISHER") "Altium Limited"))
      (libsource (lib "Miscellaneous Devices") (part "Res Semi"))
    )
    (comp (ref "R79")
      (value "50")
      (footprint "1608[0603]")
      (description "Semiconductor Resistor")
      (fields (field (name "ALTIUM_VALUE") "50") (field (name "PUBLISHER") "Altium Limited"))
      (libsource (lib "Miscellaneous Devices") (part "Res Semi"))
    )
    (comp (ref "R80")
      (value "50")
      (footprint "1608[0603]")
      (description "Semiconductor Resistor")
      (fields (field (name "ALTIUM_VALUE") "50") (field (name "PUBLISHER") "Altium Limited"))
      (libsource (lib "Miscellaneous Devices") (part "Res Semi"))
    )
    (comp (ref "R81")
      (value "10K")
      (footprint "1608[0603]")
      (description "Semiconductor Resistor")
      (fields (field (name "ALTIUM_VALUE") "10K") (field (name "PUBLISHER") "Altium Limited"))
      (libsource (lib "Miscellaneous Devices") (part "Res Semi"))
    )
    (comp (ref "R82")
      (value "10K")
      (footprint "1608[0603]")
      (description "Semiconductor Resistor")
      (fields (field (name "ALTIUM_VALUE") "10K") (field (name "PUBLISHER") "Altium Limited"))
      (libsource (lib "Miscellaneous Devices") (part "Res Semi"))
    )
    (comp (ref "R83")
      (value "50")
      (footprint "1608[0603]")
      (description "Semiconductor Resistor")
      (fields (field (name "ALTIUM_VALUE") "50") (field (name "PUBLISHER") "Altium Limited"))
      (libsource (lib "Miscellaneous Devices") (part "Res Semi"))
    )
    (comp (ref "R84")
      (value "50")
      (footprint "1608[0603]")
      (description "Semiconductor Resistor")
      (fields (field (name "ALTIUM_VALUE") "50") (field (name "PUBLISHER") "Altium Limited"))
      (libsource (lib "Miscellaneous Devices") (part "Res Semi"))
    )
    (comp (ref "R85")
      (value "50")
      (footprint "1608[0603]")
      (description "Semiconductor Resistor")
      (fields (field (name "ALTIUM_VALUE") "50") (field (name "PUBLISHER") "Altium Limited"))
      (libsource (lib "Miscellaneous Devices") (part "Res Semi"))
    )
    (comp (ref "R86")
      (value "50")
      (footprint "1608[0603]")
      (description "Semiconductor Resistor")
      (fields (field (name "ALTIUM_VALUE") "50") (field (name "PUBLISHER") "Altium Limited"))
      (libsource (lib "Miscellaneous Devices") (part "Res Semi"))
    )
    (comp (ref "R87")
      (value "10K")
      (footprint "1608[0603]")
      (description "Semiconductor Resistor")
      (fields (field (name "ALTIUM_VALUE") "10K") (field (name "PUBLISHER") "Altium Limited"))
      (libsource (lib "Miscellaneous Devices") (part "Res Semi"))
    )
    (comp (ref "R88")
      (value "10K")
      (footprint "1608[0603]")
      (description "Semiconductor Resistor")
      (fields (field (name "ALTIUM_VALUE") "10K") (field (name "PUBLISHER") "Altium Limited"))
      (libsource (lib "Miscellaneous Devices") (part "Res Semi"))
    )
    (comp (ref "R89")
      (value "50")
      (footprint "1608[0603]")
      (description "Semiconductor Resistor")
      (fields (field (name "ALTIUM_VALUE") "50") (field (name "PUBLISHER") "Altium Limited"))
      (libsource (lib "Miscellaneous Devices") (part "Res Semi"))
    )
    (comp (ref "R90")
      (value "50")
      (footprint "1608[0603]")
      (description "Semiconductor Resistor")
      (fields (field (name "ALTIUM_VALUE") "50") (field (name "PUBLISHER") "Altium Limited"))
      (libsource (lib "Miscellaneous Devices") (part "Res Semi"))
    )
    (comp (ref "R91")
      (value "50")
      (footprint "1608[0603]")
      (description "Semiconductor Resistor")
      (fields (field (name "ALTIUM_VALUE") "50") (field (name "PUBLISHER") "Altium Limited"))
      (libsource (lib "Miscellaneous Devices") (part "Res Semi"))
    )
    (comp (ref "R92")
      (value "50")
      (footprint "1608[0603]")
      (description "Semiconductor Resistor")
      (fields (field (name "ALTIUM_VALUE") "50") (field (name "PUBLISHER") "Altium Limited"))
      (libsource (lib "Miscellaneous Devices") (part "Res Semi"))
    )
    (comp (ref "R93")
      (value "1K")
      (footprint "1608[0603]")
      (description "Semiconductor Resistor")
      (fields (field (name "ALTIUM_VALUE") "1K") (field (name "PUBLISHER") "Altium Limited"))
      (libsource (lib "Miscellaneous Devices") (part "Res Semi"))
    )
    (comp (ref "R94")
      (value "10K")
      (footprint "1608[0603]")
      (description "Semiconductor Resistor")
      (fields (field (name "ALTIUM_VALUE") "10K") (field (name "PUBLISHER") "Altium Limited"))
      (libsource (lib "Miscellaneous Devices") (part "Res Semi"))
    )
    (comp (ref "R95")
      (value "10K")
      (footprint "1608[0603]")
      (description "Semiconductor Resistor")
      (fields (field (name "ALTIUM_VALUE") "10K") (field (name "PUBLISHER") "Altium Limited"))
      (libsource (lib "Miscellaneous Devices") (part "Res Semi"))
    )
    (comp (ref "R96")
      (value "10K")
      (footprint "1608[0603]")
      (description "Semiconductor Resistor")
      (fields (field (name "ALTIUM_VALUE") "10K") (field (name "PUBLISHER") "Altium Limited"))
      (libsource (lib "Miscellaneous Devices") (part "Res Semi"))
    )
    (comp (ref "R97")
      (value "10K")
      (footprint "1608[0603]")
      (description "Semiconductor Resistor")
      (fields (field (name "ALTIUM_VALUE") "10K") (field (name "PUBLISHER") "Altium Limited"))
      (libsource (lib "Miscellaneous Devices") (part "Res Semi"))
    )
    (comp (ref "R98")
      (value "10K")
      (footprint "1608[0603]")
      (description "Semiconductor Resistor")
      (fields (field (name "ALTIUM_VALUE") "10K") (field (name "PUBLISHER") "Altium Limited"))
      (libsource (lib "Miscellaneous Devices") (part "Res Semi"))
    )
    (comp (ref "R99")
      (value "10K")
      (footprint "1608[0603]")
      (description "Semiconductor Resistor")
      (fields (field (name "ALTIUM_VALUE") "10K") (field (name "PUBLISHER") "Altium Limited"))
      (libsource (lib "Miscellaneous Devices") (part "Res Semi"))
    )
    (comp (ref "R100")
      (value "10K")
      (footprint "1608[0603]")
      (description "Semiconductor Resistor")
      (fields (field (name "ALTIUM_VALUE") "10K") (field (name "PUBLISHER") "Altium Limited"))
      (libsource (lib "Miscellaneous Devices") (part "Res Semi"))
    )
    (comp (ref "R101")
      (value "10K")
      (footprint "1608[0603]")
      (description "Semiconductor Resistor")
      (fields (field (name "ALTIUM_VALUE") "10K") (field (name "PUBLISHER") "Altium Limited"))
      (libsource (lib "Miscellaneous Devices") (part "Res Semi"))
    )
    (comp (ref "R102")
      (value "10K")
      (footprint "1608[0603]")
      (description "Semiconductor Resistor")
      (fields (field (name "ALTIUM_VALUE") "10K") (field (name "PUBLISHER") "Altium Limited"))
      (libsource (lib "Miscellaneous Devices") (part "Res Semi"))
    )
    (comp (ref "R103")
      (value "10K")
      (footprint "1608[0603]")
      (description "Semiconductor Resistor")
      (fields (field (name "ALTIUM_VALUE") "10K") (field (name "PUBLISHER") "Altium Limited"))
      (libsource (lib "Miscellaneous Devices") (part "Res Semi"))
    )
    (comp (ref "R104")
      (value "10K")
      (footprint "1608[0603]")
      (description "Semiconductor Resistor")
      (fields (field (name "ALTIUM_VALUE") "10K") (field (name "PUBLISHER") "Altium Limited"))
      (libsource (lib "Miscellaneous Devices") (part "Res Semi"))
    )
    (comp (ref "R105")
      (value "10K")
      (footprint "1608[0603]")
      (description "Semiconductor Resistor")
      (fields (field (name "ALTIUM_VALUE") "10K") (field (name "PUBLISHER") "Altium Limited"))
      (libsource (lib "Miscellaneous Devices") (part "Res Semi"))
    )
    (comp (ref "R106")
      (value "10K")
      (footprint "1608[0603]")
      (description "Semiconductor Resistor")
      (fields (field (name "ALTIUM_VALUE") "10K") (field (name "PUBLISHER") "Altium Limited"))
      (libsource (lib "Miscellaneous Devices") (part "Res Semi"))
    )
    (comp (ref "R107")
      (value "10K")
      (footprint "1608[0603]")
      (description "Semiconductor Resistor")
      (fields (field (name "ALTIUM_VALUE") "10K") (field (name "PUBLISHER") "Altium Limited"))
      (libsource (lib "Miscellaneous Devices") (part "Res Semi"))
    )
    (comp (ref "R108")
      (value "10K")
      (footprint "1608[0603]")
      (description "Semiconductor Resistor")
      (fields (field (name "ALTIUM_VALUE") "10K") (field (name "PUBLISHER") "Altium Limited"))
      (libsource (lib "Miscellaneous Devices") (part "Res Semi"))
    )
    (comp (ref "R109")
      (value "10K")
      (footprint "1608[0603]")
      (description "Semiconductor Resistor")
      (fields (field (name "ALTIUM_VALUE") "10K") (field (name "PUBLISHER") "Altium Limited"))
      (libsource (lib "Miscellaneous Devices") (part "Res Semi"))
    )
    (comp (ref "R110")
      (value "10K")
      (footprint "1608[0603]")
      (description "Semiconductor Resistor")
      (fields (field (name "ALTIUM_VALUE") "10K") (field (name "PUBLISHER") "Altium Limited"))
      (libsource (lib "Miscellaneous Devices") (part "Res Semi"))
    )
    (comp (ref "R111")
      (value "1K")
      (footprint "1608[0603]")
      (description "Semiconductor Resistor")
      (fields (field (name "ALTIUM_VALUE") "1K") (field (name "PUBLISHER") "Altium Limited"))
      (libsource (lib "Miscellaneous Devices") (part "Res Semi"))
    )
    (comp (ref "R112")
      (value "1K")
      (footprint "1608[0603]")
      (description "Semiconductor Resistor")
      (fields (field (name "ALTIUM_VALUE") "1K") (field (name "PUBLISHER") "Altium Limited"))
      (libsource (lib "Miscellaneous Devices") (part "Res Semi"))
    )
    (comp (ref "R113")
      (value "1K")
      (footprint "1608[0603]")
      (description "Semiconductor Resistor")
      (fields (field (name "ALTIUM_VALUE") "1K") (field (name "PUBLISHER") "Altium Limited"))
      (libsource (lib "Miscellaneous Devices") (part "Res Semi"))
    )
    (comp (ref "R114")
      (value "1K")
      (footprint "1608[0603]")
      (description "Semiconductor Resistor")
      (fields (field (name "ALTIUM_VALUE") "1K") (field (name "PUBLISHER") "Altium Limited"))
      (libsource (lib "Miscellaneous Devices") (part "Res Semi"))
    )
    (comp (ref "R115")
      (value "10K")
      (footprint "1608[0603]")
      (description "Semiconductor Resistor")
      (fields (field (name "ALTIUM_VALUE") "10K") (field (name "PUBLISHER") "Altium Limited"))
      (libsource (lib "Miscellaneous Devices") (part "Res Semi"))
    )
    (comp (ref "R116")
      (value "10K")
      (footprint "1608[0603]")
      (description "Semiconductor Resistor")
      (fields (field (name "ALTIUM_VALUE") "10K") (field (name "PUBLISHER") "Altium Limited"))
      (libsource (lib "Miscellaneous Devices") (part "Res Semi"))
    )
    (comp (ref "R117")
      (value "10K")
      (footprint "1608[0603]")
      (description "Semiconductor Resistor")
      (fields (field (name "ALTIUM_VALUE") "10K") (field (name "PUBLISHER") "Altium Limited"))
      (libsource (lib "Miscellaneous Devices") (part "Res Semi"))
    )
    (comp (ref "R118")
      (value "10K")
      (footprint "1608[0603]")
      (description "Semiconductor Resistor")
      (fields (field (name "ALTIUM_VALUE") "10K") (field (name "PUBLISHER") "Altium Limited"))
      (libsource (lib "Miscellaneous Devices") (part "Res Semi"))
    )
    (comp (ref "R119")
      (value "1K")
      (footprint "1608[0603]")
      (description "Semiconductor Resistor")
      (fields (field (name "ALTIUM_VALUE") "1K") (field (name "PUBLISHER") "Altium Limited"))
      (libsource (lib "Miscellaneous Devices") (part "Res Semi"))
    )
    (comp (ref "R120")
      (value "10K")
      (footprint "1608[0603]")
      (description "Semiconductor Resistor")
      (fields (field (name "ALTIUM_VALUE") "10K") (field (name "PUBLISHER") "Altium Limited"))
      (libsource (lib "Miscellaneous Devices") (part "Res Semi"))
    )
    (comp (ref "R121")
      (value "10K")
      (footprint "1608[0603]")
      (description "Semiconductor Resistor")
      (fields (field (name "ALTIUM_VALUE") "10K") (field (name "PUBLISHER") "Altium Limited"))
      (libsource (lib "Miscellaneous Devices") (part "Res Semi"))
    )
    (comp (ref "R122")
      (value "100")
      (footprint "Miscellaneous Devices:2012[0805]")
      (description "Resistor")
      (fields (field (name "ALTIUM_VALUE") "100") (field (name "PUBLISHER") "Altium Limited"))
      (libsource (lib "Miscellaneous Devices") (part "Res1"))
    )
    (comp (ref "R123")
      (value "10K")
      (footprint "1608[0603]")
      (description "Semiconductor Resistor")
      (fields (field (name "ALTIUM_VALUE") "10K") (field (name "PUBLISHER") "Altium Limited"))
      (libsource (lib "Miscellaneous Devices") (part "Res Semi"))
    )
    (comp (ref "R124")
      (value "10K")
      (footprint "1608[0603]")
      (description "Semiconductor Resistor")
      (fields (field (name "ALTIUM_VALUE") "10K") (field (name "PUBLISHER") "Altium Limited"))
      (libsource (lib "Miscellaneous Devices") (part "Res Semi"))
    )
    (comp (ref "R125")
      (value "10K")
      (footprint "1608[0603]")
      (description "Semiconductor Resistor")
      (fields (field (name "ALTIUM_VALUE") "10K") (field (name "PUBLISHER") "Altium Limited"))
      (libsource (lib "Miscellaneous Devices") (part "Res Semi"))
    )
    (comp (ref "R126")
      (value "10K")
      (footprint "1608[0603]")
      (description "Semiconductor Resistor")
      (fields (field (name "ALTIUM_VALUE") "10K") (field (name "PUBLISHER") "Altium Limited"))
      (libsource (lib "Miscellaneous Devices") (part "Res Semi"))
    )
    (comp (ref "R127")
      (value "10K")
      (footprint "1608[0603]")
      (description "Semiconductor Resistor")
      (fields (field (name "ALTIUM_VALUE") "10K") (field (name "PUBLISHER") "Altium Limited"))
      (libsource (lib "Miscellaneous Devices") (part "Res Semi"))
    )
    (comp (ref "R128")
      (value "10K")
      (footprint "1608[0603]")
      (description "Semiconductor Resistor")
      (fields (field (name "ALTIUM_VALUE") "10K") (field (name "PUBLISHER") "Altium Limited"))
      (libsource (lib "Miscellaneous Devices") (part "Res Semi"))
    )
    (comp (ref "R129")
      (value "5.6K")
      (footprint "1608[0603]")
      (description "Semiconductor Resistor")
      (fields (field (name "ALTIUM_VALUE") "5.6K") (field (name "PUBLISHER") "Altium Limited"))
      (libsource (lib "Miscellaneous Devices") (part "Res Semi"))
    )
    (comp (ref "R130")
      (value "5.6K")
      (footprint "1608[0603]")
      (description "Semiconductor Resistor")
      (fields (field (name "ALTIUM_VALUE") "5.6K") (field (name "PUBLISHER") "Altium Limited"))
      (libsource (lib "Miscellaneous Devices") (part "Res Semi"))
    )
    (comp (ref "R131")
      (value "1K")
      (footprint "1608[0603]")
      (description "Semiconductor Resistor")
      (fields (field (name "ALTIUM_VALUE") "1K") (field (name "PUBLISHER") "Altium Limited"))
      (libsource (lib "Miscellaneous Devices") (part "Res Semi"))
    )
    (comp (ref "R132")
      (value "1K")
      (footprint "1608[0603]")
      (description "Semiconductor Resistor")
      (fields (field (name "ALTIUM_VALUE") "1K") (field (name "PUBLISHER") "Altium Limited"))
      (libsource (lib "Miscellaneous Devices") (part "Res Semi"))
    )
    (comp (ref "R133")
      (value "1K")
      (footprint "1608[0603]")
      (description "Semiconductor Resistor")
      (fields (field (name "ALTIUM_VALUE") "1K") (field (name "PUBLISHER") "Altium Limited"))
      (libsource (lib "Miscellaneous Devices") (part "Res Semi"))
    )
    (comp (ref "R134")
      (value "1K")
      (footprint "1608[0603]")
      (description "Semiconductor Resistor")
      (fields (field (name "ALTIUM_VALUE") "1K") (field (name "PUBLISHER") "Altium Limited"))
      (libsource (lib "Miscellaneous Devices") (part "Res Semi"))
    )
    (comp (ref "R135")
      (value "5.6K")
      (footprint "1608[0603]")
      (description "Semiconductor Resistor")
      (fields (field (name "ALTIUM_VALUE") "5.6K") (field (name "PUBLISHER") "Altium Limited"))
      (libsource (lib "Miscellaneous Devices") (part "Res Semi"))
    )
    (comp (ref "R136")
      (value "5.6K")
      (footprint "1608[0603]")
      (description "Semiconductor Resistor")
      (fields (field (name "ALTIUM_VALUE") "5.6K") (field (name "PUBLISHER") "Altium Limited"))
      (libsource (lib "Miscellaneous Devices") (part "Res Semi"))
    )
    (comp (ref "R137")
      (value "5.6K")
      (footprint "1608[0603]")
      (description "Semiconductor Resistor")
      (fields (field (name "ALTIUM_VALUE") "5.6K") (field (name "PUBLISHER") "Altium Limited"))
      (libsource (lib "Miscellaneous Devices") (part "Res Semi"))
    )
    (comp (ref "R138")
      (value "5.6K")
      (footprint "1608[0603]")
      (description "Semiconductor Resistor")
      (fields (field (name "ALTIUM_VALUE") "5.6K") (field (name "PUBLISHER") "Altium Limited"))
      (libsource (lib "Miscellaneous Devices") (part "Res Semi"))
    )
    (comp (ref "R139")
      (value "5.6K")
      (footprint "1608[0603]")
      (description "Semiconductor Resistor")
      (fields (field (name "ALTIUM_VALUE") "5.6K") (field (name "PUBLISHER") "Altium Limited"))
      (libsource (lib "Miscellaneous Devices") (part "Res Semi"))
    )
    (comp (ref "R140")
      (value "5.6K")
      (footprint "1608[0603]")
      (description "Semiconductor Resistor")
      (fields (field (name "ALTIUM_VALUE") "5.6K") (field (name "PUBLISHER") "Altium Limited"))
      (libsource (lib "Miscellaneous Devices") (part "Res Semi"))
    )
    (comp (ref "R141")
      (value "5.6K")
      (footprint "1608[0603]")
      (description "Semiconductor Resistor")
      (fields (field (name "ALTIUM_VALUE") "5.6K") (field (name "PUBLISHER") "Altium Limited"))
      (libsource (lib "Miscellaneous Devices") (part "Res Semi"))
    )
    (comp (ref "R142")
      (value "5.6K")
      (footprint "1608[0603]")
      (description "Semiconductor Resistor")
      (fields (field (name "ALTIUM_VALUE") "5.6K") (field (name "PUBLISHER") "Altium Limited"))
      (libsource (lib "Miscellaneous Devices") (part "Res Semi"))
    )
    (comp (ref "R143")
      (value "5.6K")
      (footprint "1608[0603]")
      (description "Semiconductor Resistor")
      (fields (field (name "ALTIUM_VALUE") "5.6K") (field (name "PUBLISHER") "Altium Limited"))
      (libsource (lib "Miscellaneous Devices") (part "Res Semi"))
    )
    (comp (ref "R144")
      (value "5.6K")
      (footprint "1608[0603]")
      (description "Semiconductor Resistor")
      (fields (field (name "ALTIUM_VALUE") "5.6K") (field (name "PUBLISHER") "Altium Limited"))
      (libsource (lib "Miscellaneous Devices") (part "Res Semi"))
    )
    (comp (ref "R145")
      (value "5.6K")
      (footprint "1608[0603]")
      (description "Semiconductor Resistor")
      (fields (field (name "ALTIUM_VALUE") "5.6K") (field (name "PUBLISHER") "Altium Limited"))
      (libsource (lib "Miscellaneous Devices") (part "Res Semi"))
    )
    (comp (ref "R146")
      (value "5.6K")
      (footprint "1608[0603]")
      (description "Semiconductor Resistor")
      (fields (field (name "ALTIUM_VALUE") "5.6K") (field (name "PUBLISHER") "Altium Limited"))
      (libsource (lib "Miscellaneous Devices") (part "Res Semi"))
    )
    (comp (ref "R147")
      (value "5.6K")
      (footprint "1608[0603]")
      (description "Semiconductor Resistor")
      (fields (field (name "ALTIUM_VALUE") "5.6K") (field (name "PUBLISHER") "Altium Limited"))
      (libsource (lib "Miscellaneous Devices") (part "Res Semi"))
    )
    (comp (ref "R148")
      (value "1K")
      (footprint "1608[0603]")
      (description "Semiconductor Resistor")
      (fields (field (name "ALTIUM_VALUE") "1K") (field (name "PUBLISHER") "Altium Limited"))
      (libsource (lib "Miscellaneous Devices") (part "Res Semi"))
    )
    (comp (ref "R149")
      (value "1K")
      (footprint "1608[0603]")
      (description "Semiconductor Resistor")
      (fields (field (name "ALTIUM_VALUE") "1K") (field (name "PUBLISHER") "Altium Limited"))
      (libsource (lib "Miscellaneous Devices") (part "Res Semi"))
    )
    (comp (ref "R150")
      (value "1K")
      (footprint "1608[0603]")
      (description "Semiconductor Resistor")
      (fields (field (name "ALTIUM_VALUE") "1K") (field (name "PUBLISHER") "Altium Limited"))
      (libsource (lib "Miscellaneous Devices") (part "Res Semi"))
    )
    (comp (ref "R151")
      (value "1K")
      (footprint "1608[0603]")
      (description "Semiconductor Resistor")
      (fields (field (name "ALTIUM_VALUE") "1K") (field (name "PUBLISHER") "Altium Limited"))
      (libsource (lib "Miscellaneous Devices") (part "Res Semi"))
    )
    (comp (ref "R152")
      (value "1K")
      (footprint "1608[0603]")
      (description "Semiconductor Resistor")
      (fields (field (name "ALTIUM_VALUE") "1K") (field (name "PUBLISHER") "Altium Limited"))
      (libsource (lib "Miscellaneous Devices") (part "Res Semi"))
    )
    (comp (ref "R153")
      (value "1K")
      (footprint "1608[0603]")
      (description "Semiconductor Resistor")
      (fields (field (name "ALTIUM_VALUE") "1K") (field (name "PUBLISHER") "Altium Limited"))
      (libsource (lib "Miscellaneous Devices") (part "Res Semi"))
    )
    (comp (ref "R154")
      (value "1K")
      (footprint "1608[0603]")
      (description "Semiconductor Resistor")
      (fields (field (name "ALTIUM_VALUE") "1K") (field (name "PUBLISHER") "Altium Limited"))
      (libsource (lib "Miscellaneous Devices") (part "Res Semi"))
    )
    (comp (ref "R155")
      (value "1K")
      (footprint "1608[0603]")
      (description "Semiconductor Resistor")
      (fields (field (name "ALTIUM_VALUE") "1K") (field (name "PUBLISHER") "Altium Limited"))
      (libsource (lib "Miscellaneous Devices") (part "Res Semi"))
    )
    (comp (ref "R156")
      (value "10K")
      (footprint "1608[0603]")
      (description "Semiconductor Resistor")
      (fields (field (name "ALTIUM_VALUE") "10K") (field (name "PUBLISHER") "Altium Limited"))
      (libsource (lib "Miscellaneous Devices") (part "Res Semi"))
    )
    (comp (ref "R157")
      (value "10K")
      (footprint "1608[0603]")
      (description "Semiconductor Resistor")
      (fields (field (name "ALTIUM_VALUE") "10K") (field (name "PUBLISHER") "Altium Limited"))
      (libsource (lib "Miscellaneous Devices") (part "Res Semi"))
    )
    (comp (ref "R158")
      (value "10K")
      (footprint "1608[0603]")
      (description "Semiconductor Resistor")
      (fields (field (name "ALTIUM_VALUE") "10K") (field (name "PUBLISHER") "Altium Limited"))
      (libsource (lib "Miscellaneous Devices") (part "Res Semi"))
    )
    (comp (ref "R159")
      (value "1K")
      (footprint "1608[0603]")
      (description "Semiconductor Resistor")
      (fields (field (name "ALTIUM_VALUE") "1K") (field (name "PUBLISHER") "Altium Limited"))
      (libsource (lib "Miscellaneous Devices") (part "Res Semi"))
    )
    (comp (ref "R160")
      (value "1K")
      (footprint "1608[0603]")
      (description "Semiconductor Resistor")
      (fields (field (name "ALTIUM_VALUE") "1K") (field (name "PUBLISHER") "Altium Limited"))
      (libsource (lib "Miscellaneous Devices") (part "Res Semi"))
    )
    (comp (ref "R171")
      (value "1K")
      (footprint "1608[0603]")
      (description "Semiconductor Resistor")
      (fields (field (name "ALTIUM_VALUE") "1K") (field (name "PUBLISHER") "Altium Limited"))
      (libsource (lib "Miscellaneous Devices") (part "Res Semi"))
    )
    (comp (ref "R172")
      (value "1K")
      (footprint "1608[0603]")
      (description "Semiconductor Resistor")
      (fields (field (name "ALTIUM_VALUE") "1K") (field (name "PUBLISHER") "Altium Limited"))
      (libsource (lib "Miscellaneous Devices") (part "Res Semi"))
    )
    (comp (ref "R173")
      (value "1K")
      (footprint "1608[0603]")
      (description "Semiconductor Resistor")
      (fields (field (name "ALTIUM_VALUE") "1K") (field (name "PUBLISHER") "Altium Limited"))
      (libsource (lib "Miscellaneous Devices") (part "Res Semi"))
    )
    (comp (ref "R174")
      (value "1K")
      (footprint "1608[0603]")
      (description "Semiconductor Resistor")
      (fields (field (name "ALTIUM_VALUE") "1K") (field (name "PUBLISHER") "Altium Limited"))
      (libsource (lib "Miscellaneous Devices") (part "Res Semi"))
    )
    (comp (ref "R333")
      (value "200")
      (footprint "2012[0805]")
      (description "Semiconductor Resistor")
      (fields (field (name "ALTIUM_VALUE") "200") (field (name "PUBLISHER") "Altium Limited"))
      (libsource (lib "Miscellaneous Devices") (part "Res Semi"))
    )
    (comp (ref "R341")
      (value "68")
      (footprint "2012[0805]")
      (description "Semiconductor Resistor")
      (fields (field (name "PUBLISHER") "Altium Limited"))
      (libsource (lib "Miscellaneous Devices") (part "Res Semi"))
    )
    (comp (ref "R342")
      (value "68")
      (footprint "2012[0805]")
      (description "Semiconductor Resistor")
      (fields (field (name "PUBLISHER") "Altium Limited"))
      (libsource (lib "Miscellaneous Devices") (part "Res Semi"))
    )
    (comp (ref "R343")
      (value "68")
      (footprint "2012[0805]")
      (description "Semiconductor Resistor")
      (fields (field (name "PUBLISHER") "Altium Limited"))
      (libsource (lib "Miscellaneous Devices") (part "Res Semi"))
    )
    (comp (ref "R345")
      (value "100")
      (footprint "2012[0805]")
      (description "Semiconductor Resistor")
      (fields (field (name "ALTIUM_VALUE") "100") (field (name "PUBLISHER") "Altium Limited"))
      (libsource (lib "Miscellaneous Devices") (part "Res Semi"))
    )
    (comp (ref "R346")
      (value "100")
      (footprint "2012[0805]")
      (description "Semiconductor Resistor")
      (fields (field (name "ALTIUM_VALUE") "100") (field (name "PUBLISHER") "Altium Limited"))
      (libsource (lib "Miscellaneous Devices") (part "Res Semi"))
    )
    (comp (ref "RST_CAP_1")
      (value "1uF")
      (footprint "3216[1206]")
      (description "Capacitor")
      (fields (field (name "ALTIUM_VALUE") "1uF") (field (name "PUBLISHER") "Altium Limited"))
      (libsource (lib "Miscellaneous Devices") (part "Cap"))
    )
    (comp (ref "R_Buzz")
      (value "100")
      (footprint "2012[0805]")
      (description "Semiconductor Resistor")
      (fields (field (name "ALTIUM_VALUE") "100") (field (name "PUBLISHER") "Altium Limited"))
      (libsource (lib "Miscellaneous Devices") (part "Res Semi"))
    )
    (comp (ref "R_done_led")
      (value "1K")
      (footprint "2012[0805]")
      (description "Semiconductor Resistor")
      (fields (field (name "ALTIUM_VALUE") "1K") (field (name "PUBLISHER") "Altium Limited"))
      (libsource (lib "Miscellaneous Devices") (part "Res Semi"))
    )
    (comp (ref "R_D_REV")
      (value "1K")
      (footprint "Miscellaneous Devices:2012[0805]")
      (description "Resistor")
      (fields (field (name "ALTIUM_VALUE") "1K") (field (name "PUBLISHER") "Altium Limited"))
      (libsource (lib "") (part "Res2_1"))
    )
    (comp (ref "S2D3")
      (value "SN74HC541DW")
      (footprint "PW020_N")
      (description "Octal Buffer/Driver with 3-State Outputs")
      (fields (field (name "PUBLISHER") "Altium Limited"))
      (libsource (lib "TI Logic Buffer Line Driver") (part "SN74HC541DW"))
    )
    (comp (ref "S4")
      (value "SW-PB")
      (footprint "SPST-2")
      (description "Switch")
      (fields (field (name "PUBLISHER") "Altium Limited"))
      (libsource (lib "Miscellaneous Devices") (part "SW-PB"))
    )
    (comp (ref "S_D_1")
      (value "SW-PB")
      (footprint "SPST-2")
      (description "Switch")
      (fields (field (name "PUBLISHER") "Altium Limited"))
      (libsource (lib "Miscellaneous Devices") (part "SW-PB"))
    )
    (comp (ref "S_D_2")
      (value "SW-PB")
      (footprint "SPST-2")
      (description "Switch")
      (fields (field (name "PUBLISHER") "Altium Limited"))
      (libsource (lib "Miscellaneous Devices") (part "SW-PB"))
    )
    (comp (ref "S_D_3")
      (value "SW-PB")
      (footprint "SPST-2")
      (description "Switch")
      (fields (field (name "PUBLISHER") "Altium Limited"))
      (libsource (lib "Miscellaneous Devices") (part "SW-PB"))
    )
    (comp (ref "S_D_4")
      (value "SW-PB")
      (footprint "SPST-2")
      (description "Switch")
      (fields (field (name "PUBLISHER") "Altium Limited"))
      (libsource (lib "Miscellaneous Devices") (part "SW-PB"))
    )
    (comp (ref "S_ID")
      (value "SW-DIP4")
      (footprint "DIP-8")
      (description "DIP Switch")
      (fields (field (name "PUBLISHER") "Altium Limited"))
      (libsource (lib "Miscellaneous Devices") (part "SW-DIP4"))
    )
    (comp (ref "S_SET")
      (value "SW-DIP4")
      (footprint "DIP-8")
      (description "DIP Switch")
      (fields (field (name "PUBLISHER") "Altium Limited"))
      (libsource (lib "Miscellaneous Devices") (part "SW-DIP4"))
    )
    (comp (ref "telecontrolli")
      (value "Header 8X2A")
      (footprint "PcbLib1:RXQ2")
      (description "Header, 8-Pin, Dual row")
      (fields (field (name "PUBLISHER") "Altium Limited"))
      (libsource (lib "Miscellaneous Connectors") (part "Header 8X2A"))
    )
    (comp (ref "U1")
      (value "SN74HC541DW")
      (footprint "PW020_N")
      (description "Octal Buffer/Driver with 3-State Outputs")
      (fields (field (name "PUBLISHER") "Altium Limited"))
      (libsource (lib "TI Logic Buffer Line Driver") (part "SN74HC541DW"))
    )
    (comp (ref "U2")
      (value "SN74HC541DW")
      (footprint "PW020_N")
      (description "Octal Buffer/Driver with 3-State Outputs")
      (fields (field (name "PUBLISHER") "Altium Limited"))
      (libsource (lib "TI Logic Buffer Line Driver") (part "SN74HC541DW"))
    )
    (comp (ref "U3")
      (value "SN74HC541DW")
      (footprint "PW020_N")
      (description "Octal Buffer/Driver with 3-State Outputs")
      (fields (field (name "PUBLISHER") "Altium Limited"))
      (libsource (lib "TI Logic Buffer Line Driver") (part "SN74HC541DW"))
    )
    (comp (ref "U4")
      (value "SN74HC541DW")
      (footprint "PW020_N")
      (description "Octal Buffer/Driver with 3-State Outputs")
      (fields (field (name "PUBLISHER") "Altium Limited"))
      (libsource (lib "TI Logic Buffer Line Driver") (part "SN74HC541DW"))
    )
    (comp (ref "U5")
      (value "XC3S400-5TQ144C")
      (footprint "TQ144_L")
      (description "Spartan-3 1.2V FPGA, 97 User I/Os, 144-Pin TQFP, High Performance, Commercial Grade")
      (fields (field (name "PUBLISHER") "Altium Limited"))
      (libsource (lib "") (part "XC3S400-5TQ144C_1"))
    )
    (comp (ref "U6")
      (value "MIC4428BM")
      (footprint "NSO8_L")
      (description "Dual High-Speed 1.5A MOSFET Driver")
      (fields (field (name "PUBLISHER") "Altium Limited"))
      (libsource (lib "Maxim Interface MOSFET Driver") (part "MAX4427CSA"))
    )
    (comp (ref "U7")
      (value "MAX4427CSA")
      (footprint "NSO8_L")
      (description "Dual High-Speed 1.5A MOSFET Driver")
      (fields (field (name "PUBLISHER") "Altium Limited"))
      (libsource (lib "Maxim Interface MOSFET Driver") (part "MAX4427CSA"))
    )
    (comp (ref "U8")
      (value "MAX4427CSA")
      (footprint "NSO8_L")
      (description "Dual High-Speed 1.5A MOSFET Driver")
      (fields (field (name "PUBLISHER") "Altium Limited"))
      (libsource (lib "Maxim Interface MOSFET Driver") (part "MAX4427CSA"))
    )
    (comp (ref "U9")
      (value "MIC4428BM")
      (footprint "NSO8_L")
      (description "Dual High-Speed 1.5A MOSFET Driver")
      (fields (field (name "PUBLISHER") "Altium Limited"))
      (libsource (lib "Maxim Interface MOSFET Driver") (part "MAX4427CSA"))
    )
    (comp (ref "U10")
      (value "MAX4427CSA")
      (footprint "NSO8_L")
      (description "Dual High-Speed 1.5A MOSFET Driver")
      (fields (field (name "PUBLISHER") "Altium Limited"))
      (libsource (lib "Maxim Interface MOSFET Driver") (part "MAX4427CSA"))
    )
    (comp (ref "U11")
      (value "MIC4428BM")
      (footprint "NSO8_L")
      (description "Dual High-Speed 1.5A MOSFET Driver")
      (fields (field (name "PUBLISHER") "Altium Limited"))
      (libsource (lib "Maxim Interface MOSFET Driver") (part "MAX4427CSA"))
    )
    (comp (ref "U12")
      (value "MIC4428BM")
      (footprint "NSO8_L")
      (description "Dual High-Speed 1.5A MOSFET Driver")
      (fields (field (name "PUBLISHER") "Altium Limited"))
      (libsource (lib "Maxim Interface MOSFET Driver") (part "MAX4427CSA"))
    )
    (comp (ref "U13")
      (value "MIC4428BM")
      (footprint "NSO8_L")
      (description "Dual High-Speed 1.5A MOSFET Driver")
      (fields (field (name "PUBLISHER") "Altium Limited"))
      (libsource (lib "Maxim Interface MOSFET Driver") (part "MAX4427CSA"))
    )
    (comp (ref "U14")
      (value "MIC4428BM")
      (footprint "NSO8_L")
      (description "Dual High-Speed 1.5A MOSFET Driver")
      (fields (field (name "PUBLISHER") "Altium Limited"))
      (libsource (lib "Maxim Interface MOSFET Driver") (part "MAX4427CSA"))
    )
    (comp (ref "U15")
      (value "MIC4428BM")
      (footprint "NSO8_L")
      (description "Dual High-Speed 1.5A MOSFET Driver")
      (fields (field (name "PUBLISHER") "Altium Limited"))
      (libsource (lib "Maxim Interface MOSFET Driver") (part "MAX4427CSA"))
    )
    (comp (ref "U16")
      (value "MIC4428BM")
      (footprint "NSO8_L")
      (description "Dual High-Speed 1.5A MOSFET Driver")
      (fields (field (name "PUBLISHER") "Altium Limited"))
      (libsource (lib "Maxim Interface MOSFET Driver") (part "MAX4427CSA"))
    )
    (comp (ref "U17")
      (value "MIC4428BM")
      (footprint "NSO8_L")
      (description "Dual High-Speed 1.5A MOSFET Driver")
      (fields (field (name "PUBLISHER") "Altium Limited"))
      (libsource (lib "Maxim Interface MOSFET Driver") (part "MAX4427CSA"))
    )
    (comp (ref "U18")
      (value "MIC4428BM")
      (footprint "NSO8_L")
      (description "Dual High-Speed 1.5A MOSFET Driver")
      (fields (field (name "PUBLISHER") "Altium Limited"))
      (libsource (lib "Maxim Interface MOSFET Driver") (part "MAX4427CSA"))
    )
    (comp (ref "U19")
      (value "MIC4428BM")
      (footprint "NSO8_L")
      (description "Dual High-Speed 1.5A MOSFET Driver")
      (fields (field (name "PUBLISHER") "Altium Limited"))
      (libsource (lib "Maxim Interface MOSFET Driver") (part "MAX4427CSA"))
    )
    (comp (ref "U20")
      (value "MIC4428BM")
      (footprint "NSO8_L")
      (description "Dual High-Speed 1.5A MOSFET Driver")
      (fields (field (name "PUBLISHER") "Altium Limited"))
      (libsource (lib "Maxim Interface MOSFET Driver") (part "MAX4427CSA"))
    )
    (comp (ref "U21")
      (value "TC3400")
      (footprint "Maxim Interface MOSFET Driver:NSO8_L")
      (description "8 Mbit Flash Serial Prom")
      (libsource (lib "Altium Nanoboard Project") (part "M25P10-VMN6"))
    )
    (comp (ref "U22")
      (value "TC4427")
      (footprint "NSO8_L")
      (description "Dual High-Speed 1.5A MOSFET Driver")
      (fields (field (name "PUBLISHER") "Altium Limited"))
      (libsource (lib "Maxim Interface MOSFET Driver") (part "MAX4427CSA"))
    )
    (comp (ref "U27")
      (value "XCF04SVO20C")
      (footprint "VO20_N")
      (fields (field (name "PUBLISHER") "Altium Limited"))
      (libsource (lib "Xilinx XCF") (part "XCF04SVO20C"))
    )
    (comp (ref "U36")
      (value "M25P80-VMW6")
      (footprint "Miscellaneous Devices:SO8")
      (description "8 Mbit Flash Serial Prom")
      (libsource (lib "Altium Nanoboard Project") (part "M25P10-VMN6"))
    )
    (comp (ref "VR_1.2")
      (value "1112")
      (footprint "TO-252")
      (description "500mA, Very Low Drop (0.45V) Voltage Regulator")
      (fields (field (name "PUBLISHER") "Altium Limited"))
      (libsource (lib "ST Power Mgt Voltage Regulator") (part "LF12ABDT"))
    )
    (comp (ref "VR_2.5")
      (value "LF25")
      (footprint "TO-252")
      (description "500mA, Very Low Drop (0.45V) Voltage Regulator")
      (fields (field (name "PUBLISHER") "Altium Limited"))
      (libsource (lib "ST Power Mgt Voltage Regulator") (part "LF25ABDT"))
    )
    (comp (ref "VR_3.3")
      (value "1085")
      (footprint "936-03")
      (description "5A Low Dropout Fast Response Positive Fixed Voltage Regulator")
      (fields (field (name "PUBLISHER") "Altium Limited"))
      (libsource (lib "ON Semi Power Mgt Voltage Regulator") (part "LT1585ACM-1.5"))
    )
    (comp (ref "X1")
      (value "36.864MHz")
      (footprint "QSMO_4200")
      (description "QSMO - 4200 SERIES, 40MHz, SURFACE MOUNT CRYSTAL OSCILLATOR")
      (fields (field (name "PUBLISHER") "Altium Limited"))
      (libsource (lib "Altium Nanoboard Project") (part "QSMO_4200"))
    )
  )
  (nets
    (net (code "1") (name "/CCLK") (class "Default")
      (node (ref "R31") (pin "1") (pinfunction "1_1") (pintype "passive"))
      (node (ref "U27") (pin "3") (pinfunction "CLK_3") (pintype "input"))
      (node (ref "U5") (pin "72") (pinfunction "CCLK_72") (pintype "bidirectional"))
    )
    (net (code "2") (name "/CLK") (class "Default")
      (node (ref "U5") (pin "128") (pinfunction "IO_L32N_0/GCLK7_128") (pintype "bidirectional"))
      (node (ref "X1") (pin "3") (pinfunction "OUT_3") (pintype "output"))
    )
    (net (code "3") (name "/CTS") (class "Default")
      (node (ref "R158") (pin "2") (pinfunction "2_2") (pintype "passive"))
      (node (ref "U5") (pin "68") (pinfunction "IO_L01P_4/VRN_4_68") (pintype "bidirectional"))
      (node (ref "nRF") (pin "6") (pinfunction "6_6") (pintype "passive"))
      (node (ref "telecontrolli") (pin "9") (pinfunction "16_9") (pintype "passive"))
    )
    (net (code "4") (name "/C_SPI_CLK") (class "Default")
      (node (ref "R115") (pin "1") (pinfunction "1_1") (pintype "passive"))
      (node (ref "U36") (pin "6") (pinfunction "C_6") (pintype "input"))
      (node (ref "U5") (pin "130") (pinfunction "IO_L31N_0_130") (pintype "bidirectional"))
    )
    (net (code "5") (name "/C_SPI_DIN") (class "Default")
      (node (ref "R110") (pin "2") (pinfunction "2_2") (pintype "passive"))
      (node (ref "U36") (pin "5") (pinfunction "D_5") (pintype "input"))
      (node (ref "U5") (pin "129") (pinfunction "IO_L31P_0/VREF_0_129") (pintype "bidirectional"))
    )
    (net (code "6") (name "/C_SPI_DOUT") (class "Default")
      (node (ref "U36") (pin "2") (pinfunction "Q_2") (pintype "output"))
      (node (ref "U5") (pin "131") (pinfunction "IO_L30P_0_131") (pintype "bidirectional"))
    )
    (net (code "7") (name "/C_SPI_SEL_FLSH") (class "Default")
      (node (ref "R109") (pin "2") (pinfunction "2_2") (pintype "passive"))
      (node (ref "U36") (pin "1") (pinfunction "~{S}_1") (pintype "input"))
      (node (ref "U5") (pin "132") (pinfunction "IO_L30N_0_132") (pintype "bidirectional"))
    )
    (net (code "8") (name "/Charge_pulse") (class "Default")
      (node (ref "Booster") (pin "3") (pinfunction "3_3") (pintype "passive"))
      (node (ref "R118") (pin "2") (pinfunction "2_2") (pintype "passive"))
      (node (ref "U5") (pin "113") (pinfunction "IO_L01N_1/VRP_1_113") (pintype "bidirectional"))
    )
    (net (code "9") (name "/Chip_pulse") (class "Default")
      (node (ref "Booster") (pin "2") (pinfunction "2_2") (pintype "passive"))
      (node (ref "R117") (pin "2") (pinfunction "2_2") (pintype "passive"))
      (node (ref "U5") (pin "116") (pinfunction "IO_116") (pintype "bidirectional"))
    )
    (net (code "10") (name "/DIN") (class "Default")
      (node (ref "U27") (pin "1") (pinfunction "D0_1") (pintype "tri_state"))
      (node (ref "U5") (pin "65") (pinfunction "IO_L27N_4/DIN/D0_65") (pintype "bidirectional"))
    )
    (net (code "11") (name "/DONE") (class "Default")
      (node (ref "R34") (pin "2") (pinfunction "2_2") (pintype "passive"))
      (node (ref "S2D3") (pin "6") (pinfunction "A5_6") (pintype "input"))
      (node (ref "U27") (pin "10") (pinfunction "~{CE}_10") (pintype "input"))
      (node (ref "U5") (pin "71") (pinfunction "DONE_71") (pintype "bidirectional"))
    )
    (net (code "12") (name "/DONE_LED") (class "Default")
      (node (ref "D_Done") (pin "1") (pinfunction "A_1") (pintype "passive"))
      (node (ref "S2D3") (pin "14") (pinfunction "Y5_14") (pintype "tri_state"))
    )
    (net (code "13") (name "/D_IO1") (class "Default")
      (node (ref "R(rst)") (pin "2") (pinfunction "2_2") (pintype "passive"))
      (node (ref "RST_CAP_1") (pin "2") (pinfunction "2_2") (pintype "passive"))
      (node (ref "S4") (pin "2") (pinfunction "2_2") (pintype "passive"))
      (node (ref "U5") (pin "40") (pinfunction "IO_L01P_5/CS_B_40") (pintype "bidirectional"))
    )
    (net (code "14") (name "/D_IO2") (class "Default")
      (node (ref "R111") (pin "1") (pinfunction "1_1") (pintype "passive"))
      (node (ref "S_ID") (pin "8") (pinfunction "8_8") (pintype "passive"))
      (node (ref "U5") (pin "41") (pinfunction "IO_L01N_5/RDWR_B_41") (pintype "bidirectional"))
    )
    (net (code "15") (name "/D_IO3") (class "Default")
      (node (ref "R131") (pin "1") (pinfunction "1_1") (pintype "passive"))
      (node (ref "S_ID") (pin "7") (pinfunction "7_7") (pintype "passive"))
      (node (ref "U5") (pin "44") (pinfunction "IO/VREF_5_44") (pintype "bidirectional"))
    )
    (net (code "16") (name "/D_IO4") (class "Default")
      (node (ref "R151") (pin "1") (pinfunction "1_1") (pintype "passive"))
      (node (ref "S_ID") (pin "6") (pinfunction "6_6") (pintype "passive"))
      (node (ref "U5") (pin "46") (pinfunction "IO_L28P_5/D7_46") (pintype "bidirectional"))
    )
    (net (code "17") (name "/D_IO5") (class "Default")
      (node (ref "R171") (pin "1") (pinfunction "1_1") (pintype "passive"))
      (node (ref "S_ID") (pin "5") (pinfunction "5_5") (pintype "passive"))
      (node (ref "U5") (pin "47") (pinfunction "IO_L28N_5/D6_47") (pintype "bidirectional"))
    )
    (net (code "18") (name "/D_IO6") (class "Default")
      (node (ref "R172") (pin "1") (pinfunction "1_1") (pintype "passive"))
      (node (ref "S_SET") (pin "5") (pinfunction "5_5") (pintype "passive"))
      (node (ref "U5") (pin "50") (pinfunction "IO_L31P_5/D5_50") (pintype "bidirectional"))
    )
    (net (code "19") (name "/D_IO7") (class "Default")
      (node (ref "R152") (pin "1") (pinfunction "1_1") (pintype "passive"))
      (node (ref "S_SET") (pin "6") (pinfunction "6_6") (pintype "passive"))
      (node (ref "U5") (pin "51") (pinfunction "IO_L31N_5/D4_51") (pintype "bidirectional"))
    )
    (net (code "20") (name "/D_IO8") (class "Default")
      (node (ref "R132") (pin "1") (pinfunction "1_1") (pintype "passive"))
      (node (ref "S_SET") (pin "7") (pinfunction "7_7") (pintype "passive"))
      (node (ref "U5") (pin "52") (pinfunction "IO_L32P_5/GCLK2_52") (pintype "bidirectional"))
    )
    (net (code "21") (name "/D_IO9") (class "Default")
      (node (ref "R148") (pin "2") (pinfunction "2_2") (pintype "passive"))
      (node (ref "R156") (pin "1") (pinfunction "1_1") (pintype "passive"))
      (node (ref "U5") (pin "53") (pinfunction "IO_L32N_5/GCLK3_53") (pintype "bidirectional"))
      (node (ref "nRF") (pin "4") (pinfunction "4_4") (pintype "passive"))
    )
    (net (code "22") (name "/D_IO10") (class "Default")
      (node (ref "U21") (pin "6") (pinfunction "C_6") (pintype "input"))
      (node (ref "U5") (pin "55") (pinfunction "IO_L32P_4/GCLK0_55") (pintype "bidirectional"))
    )
    (net (code "23") (name "/D_IO11") (class "Default")
      (node (ref "R119") (pin "2") (pinfunction "2_2") (pintype "passive"))
      (node (ref "U21") (pin "7") (pinfunction "HOL~{D}_7") (pintype "input"))
      (node (ref "U5") (pin "56") (pinfunction "IO_L32N_4/GCLK1_56") (pintype "bidirectional"))
    )
    (net (code "24") (name "/D_IO12") (class "Default")
      (node (ref "R157") (pin "1") (pinfunction "1_1") (pintype "passive"))
      (node (ref "U5") (pin "57") (pinfunction "IO_L31P_4/DOUT/BUSY_57") (pintype "bidirectional"))
      (node (ref "nRF") (pin "5") (pinfunction "5_5") (pintype "passive"))
    )
    (net (code "25") (name "/D_IO13") (class "Default")
      (node (ref "U5") (pin "59") (pinfunction "IO_L30P_4/D3_59") (pintype "bidirectional"))
      (node (ref "nRF") (pin "3") (pinfunction "3_3") (pintype "passive"))
      (node (ref "telecontrolli") (pin "14") (pinfunction "11_14") (pintype "passive"))
    )
    (net (code "26") (name "/D_IO14") (class "Default")
      (node (ref "R127") (pin "2") (pinfunction "2_2") (pintype "passive"))
      (node (ref "U5") (pin "60") (pinfunction "IO_L30N_4/D2_60") (pintype "bidirectional"))
      (node (ref "nRF") (pin "2") (pinfunction "2_2") (pintype "passive"))
      (node (ref "telecontrolli") (pin "15") (pinfunction "10_15") (pintype "passive"))
    )
    (net (code "27") (name "/D_IO15") (class "Default")
      (node (ref "R128") (pin "2") (pinfunction "2_2") (pintype "passive"))
      (node (ref "U5") (pin "63") (pinfunction "IO_L27P_4/D1_63") (pintype "bidirectional"))
      (node (ref "nRF") (pin "7") (pinfunction "7_7") (pintype "passive"))
      (node (ref "telecontrolli") (pin "10") (pinfunction "15_10") (pintype "passive"))
    )
    (net (code "28") (name "/D_IO17") (class "Default")
      (node (ref "R126") (pin "1") (pinfunction "1_1") (pintype "passive"))
      (node (ref "S2D3") (pin "8") (pinfunction "A7_8") (pintype "input"))
      (node (ref "U5") (pin "69") (pinfunction "IO_L01N_4/VRP_4_69") (pintype "bidirectional"))
    )
    (net (code "29") (name "/D_IO18") (class "Default")
      (node (ref "R125") (pin "1") (pinfunction "1_1") (pintype "passive"))
      (node (ref "S2D3") (pin "7") (pinfunction "A6_7") (pintype "input"))
      (node (ref "U5") (pin "70") (pinfunction "IO/VREF_4_70") (pintype "bidirectional"))
    )
    (net (code "30") (name "/Encoder 1-0") (class "Default")
      (node (ref "U4") (pin "17") (pinfunction "Y2_17") (pintype "tri_state"))
      (node (ref "U5") (pin "89") (pinfunction "IO_L40P_3_89") (pintype "bidirectional"))
    )
    (net (code "31") (name "/Encoder 1-1") (class "Default")
      (node (ref "U4") (pin "18") (pinfunction "Y1_18") (pintype "tri_state"))
      (node (ref "U5") (pin "90") (pinfunction "IO_L40N_3/VREF_3_90") (pintype "bidirectional"))
    )
    (net (code "32") (name "/Encoder 2-0") (class "Default")
      (node (ref "U1") (pin "12") (pinfunction "Y7_12") (pintype "tri_state"))
      (node (ref "U5") (pin "24") (pinfunction "IO_L24N_6/VREF_6_24") (pintype "bidirectional"))
    )
    (net (code "33") (name "/Encoder 2-1") (class "Default")
      (node (ref "U1") (pin "13") (pinfunction "Y6_13") (pintype "tri_state"))
      (node (ref "U5") (pin "25") (pinfunction "IO_L23P_6_25") (pintype "bidirectional"))
    )
    (net (code "34") (name "/Encoder 3-0") (class "Default")
      (node (ref "U1") (pin "14") (pinfunction "Y5_14") (pintype "tri_state"))
      (node (ref "U5") (pin "26") (pinfunction "IO_L23N_6_26") (pintype "bidirectional"))
    )
    (net (code "35") (name "/Encoder 3-1") (class "Default")
      (node (ref "U1") (pin "15") (pinfunction "Y4_15") (pintype "tri_state"))
      (node (ref "U5") (pin "27") (pinfunction "IO_L22P_6_27") (pintype "bidirectional"))
    )
    (net (code "36") (name "/Encoder 4-0") (class "Default")
      (node (ref "U4") (pin "14") (pinfunction "Y5_14") (pintype "tri_state"))
      (node (ref "U5") (pin "86") (pinfunction "IO_L24P_3_86") (pintype "bidirectional"))
    )
    (net (code "37") (name "/Encoder 4-1") (class "Default")
      (node (ref "U4") (pin "15") (pinfunction "Y4_15") (pintype "tri_state"))
      (node (ref "U5") (pin "87") (pinfunction "IO_L24N_3_87") (pintype "bidirectional"))
    )
    (net (code "38") (name "/H1_1") (class "Default")
      (node (ref "MOTOR_1") (pin "8") (pinfunction "8_8") (pintype "passive"))
      (node (ref "U3") (pin "3") (pinfunction "A2_3") (pintype "input"))
    )
    (net (code "39") (name "/H1_1(3.3)") (class "Default")
      (node (ref "U3") (pin "17") (pinfunction "Y2_17") (pintype "tri_state"))
      (node (ref "U5") (pin "102") (pinfunction "IO_L21P_2_102") (pintype "bidirectional"))
    )
    (net (code "40") (name "/H1_2") (class "Default")
      (node (ref "MOTOR_1") (pin "7") (pinfunction "7_7") (pintype "passive"))
      (node (ref "U3") (pin "4") (pinfunction "A3_4") (pintype "input"))
    )
    (net (code "41") (name "/H1_2(3.3)") (class "Default")
      (node (ref "U3") (pin "16") (pinfunction "Y3_16") (pintype "tri_state"))
      (node (ref "U5") (pin "103") (pinfunction "IO_L21N_2_103") (pintype "bidirectional"))
    )
    (net (code "42") (name "/H1_3") (class "Default")
      (node (ref "MOTOR_1") (pin "6") (pinfunction "6_6") (pintype "passive"))
      (node (ref "U3") (pin "5") (pinfunction "A4_5") (pintype "input"))
    )
    (net (code "43") (name "/H1_3(3.3)") (class "Default")
      (node (ref "U3") (pin "15") (pinfunction "Y4_15") (pintype "tri_state"))
      (node (ref "U5") (pin "104") (pinfunction "IO_L20P_2_104") (pintype "bidirectional"))
    )
    (net (code "44") (name "/H2_1") (class "Default")
      (node (ref "MOTOR_2") (pin "8") (pinfunction "8_8") (pintype "passive"))
      (node (ref "U2") (pin "6") (pinfunction "A5_6") (pintype "input"))
    )
    (net (code "45") (name "/H2_1(3.3)") (class "Default")
      (node (ref "U2") (pin "14") (pinfunction "Y5_14") (pintype "tri_state"))
      (node (ref "U5") (pin "10") (pinfunction "IO_L22P_7_10") (pintype "bidirectional"))
    )
    (net (code "46") (name "/H2_2") (class "Default")
      (node (ref "MOTOR_2") (pin "7") (pinfunction "7_7") (pintype "passive"))
      (node (ref "U2") (pin "5") (pinfunction "A4_5") (pintype "input"))
    )
    (net (code "47") (name "/H2_2(3.3)") (class "Default")
      (node (ref "U2") (pin "15") (pinfunction "Y4_15") (pintype "tri_state"))
      (node (ref "U5") (pin "11") (pinfunction "IO_L22N_7_11") (pintype "bidirectional"))
    )
    (net (code "48") (name "/H2_3") (class "Default")
      (node (ref "MOTOR_2") (pin "6") (pinfunction "6_6") (pintype "passive"))
      (node (ref "U2") (pin "4") (pinfunction "A3_4") (pintype "input"))
    )
    (net (code "49") (name "/H2_3(3.3)") (class "Default")
      (node (ref "U2") (pin "16") (pinfunction "Y3_16") (pintype "tri_state"))
      (node (ref "U5") (pin "12") (pinfunction "IO_L23P_7_12") (pintype "bidirectional"))
    )
    (net (code "50") (name "/H3_1") (class "Default")
      (node (ref "MOTOR_3") (pin "8") (pinfunction "8_8") (pintype "passive"))
      (node (ref "U1") (pin "4") (pinfunction "A3_4") (pintype "input"))
    )
    (net (code "51") (name "/H3_1(3.3)") (class "Default")
      (node (ref "U1") (pin "16") (pinfunction "Y3_16") (pintype "tri_state"))
      (node (ref "U5") (pin "28") (pinfunction "IO_L22N_6_28") (pintype "bidirectional"))
    )
    (net (code "52") (name "/H3_2") (class "Default")
      (node (ref "MOTOR_3") (pin "7") (pinfunction "7_7") (pintype "passive"))
      (node (ref "U1") (pin "3") (pinfunction "A2_3") (pintype "input"))
    )
    (net (code "53") (name "/H3_2(3.3)") (class "Default")
      (node (ref "U1") (pin "17") (pinfunction "Y2_17") (pintype "tri_state"))
      (node (ref "U5") (pin "30") (pinfunction "IO_L21P_6_30") (pintype "bidirectional"))
    )
    (net (code "54") (name "/H3_3") (class "Default")
      (node (ref "MOTOR_3") (pin "6") (pinfunction "6_6") (pintype "passive"))
      (node (ref "U1") (pin "2") (pinfunction "A1_2") (pintype "input"))
    )
    (net (code "55") (name "/H3_3(3.3)") (class "Default")
      (node (ref "U1") (pin "18") (pinfunction "Y1_18") (pintype "tri_state"))
      (node (ref "U5") (pin "31") (pinfunction "IO_L21N_6_31") (pintype "bidirectional"))
    )
    (net (code "56") (name "/H4_1") (class "Default")
      (node (ref "MOTOR_4") (pin "6") (pinfunction "6_6") (pintype "passive"))
      (node (ref "U4") (pin "7") (pinfunction "A6_7") (pintype "input"))
    )
    (net (code "57") (name "/H4_1(3.3)") (class "Default")
      (node (ref "U4") (pin "13") (pinfunction "Y6_13") (pintype "tri_state"))
      (node (ref "U5") (pin "85") (pinfunction "IO_L23N_3_85") (pintype "bidirectional"))
    )
    (net (code "58") (name "/H4_2") (class "Default")
      (node (ref "MOTOR_4") (pin "7") (pinfunction "7_7") (pintype "passive"))
      (node (ref "U4") (pin "8") (pinfunction "A7_8") (pintype "input"))
    )
    (net (code "59") (name "/H4_2(3.3)") (class "Default")
      (node (ref "U4") (pin "12") (pinfunction "Y7_12") (pintype "tri_state"))
      (node (ref "U5") (pin "84") (pinfunction "IO_L23P_3/VREF_3_84") (pintype "bidirectional"))
    )
    (net (code "60") (name "/H4_3") (class "Default")
      (node (ref "MOTOR_4") (pin "8") (pinfunction "8_8") (pintype "passive"))
      (node (ref "U4") (pin "9") (pinfunction "A8_9") (pintype "input"))
    )
    (net (code "61") (name "/H4_3(3.3)") (class "Default")
      (node (ref "U4") (pin "11") (pinfunction "Y8_11") (pintype "tri_state"))
      (node (ref "U5") (pin "83") (pinfunction "IO_L22N_3_83") (pintype "bidirectional"))
    )
    (net (code "62") (name "/Hd_1") (class "Default")
      (node (ref "Dribbler") (pin "6") (pinfunction "6_6") (pintype "passive"))
      (node (ref "R40") (pin "2") (pinfunction "2_2") (pintype "passive"))
      (node (ref "U2") (pin "7") (pinfunction "A6_7") (pintype "input"))
    )
    (net (code "63") (name "/Hd_1(3.3)") (class "Default")
      (node (ref "U2") (pin "13") (pinfunction "Y6_13") (pintype "tri_state"))
      (node (ref "U5") (pin "8") (pinfunction "IO_L21N_7_8") (pintype "bidirectional"))
    )
    (net (code "64") (name "/Hd_2") (class "Default")
      (node (ref "Dribbler") (pin "7") (pinfunction "7_7") (pintype "passive"))
      (node (ref "R41") (pin "2") (pinfunction "2_2") (pintype "passive"))
      (node (ref "U2") (pin "8") (pinfunction "A7_8") (pintype "input"))
    )
    (net (code "65") (name "/Hd_2(3.3)") (class "Default")
      (node (ref "U2") (pin "12") (pinfunction "Y7_12") (pintype "tri_state"))
      (node (ref "U5") (pin "7") (pinfunction "IO_L21P_7_7") (pintype "bidirectional"))
    )
    (net (code "66") (name "/Hd_3") (class "Default")
      (node (ref "Dribbler") (pin "8") (pinfunction "8_8") (pintype "passive"))
      (node (ref "R42") (pin "2") (pinfunction "2_2") (pintype "passive"))
      (node (ref "U2") (pin "9") (pinfunction "A8_9") (pintype "input"))
    )
    (net (code "67") (name "/Hd_3(3.3)") (class "Default")
      (node (ref "U2") (pin "11") (pinfunction "Y8_11") (pintype "tri_state"))
      (node (ref "U5") (pin "6") (pinfunction "IO_L20N_7_6") (pintype "bidirectional"))
    )
    (net (code "68") (name "/INIT_B") (class "Default")
      (node (ref "R32") (pin "2") (pinfunction "2_2") (pintype "passive"))
      (node (ref "U27") (pin "8") (pinfunction "OE/~{RESET}_8") (pintype "bidirectional"))
      (node (ref "U5") (pin "58") (pinfunction "IO_L31N_4/INIT_B_58") (pintype "bidirectional"))
    )
    (net (code "69") (name "/L_IO1") (class "Default")
      (node (ref "R30") (pin "1") (pinfunction "1_1") (pintype "passive"))
      (node (ref "U5") (pin "1") (pinfunction "IO_L01P_7/VRN_7_1") (pintype "bidirectional"))
    )
    (net (code "70") (name "/L_IO2") (class "Default")
      (node (ref "R36") (pin "1") (pinfunction "1_1") (pintype "passive"))
      (node (ref "U5") (pin "2") (pinfunction "IO_L01N_7/VRP_7_2") (pintype "bidirectional"))
    )
    (net (code "71") (name "/L_IO3") (class "Default")
      (node (ref "R38") (pin "1") (pinfunction "1_1") (pintype "passive"))
      (node (ref "U5") (pin "4") (pinfunction "IO/VREF_7_4") (pintype "bidirectional"))
    )
    (net (code "72") (name "/L_IO4") (class "Default")
      (node (ref "R39") (pin "1") (pinfunction "1_1") (pintype "passive"))
      (node (ref "U5") (pin "5") (pinfunction "IO_L20P_7_5") (pintype "bidirectional"))
    )
    (net (code "73") (name "/L_IO11") (class "Default")
      (node (ref "R2") (pin "2") (pinfunction "2_2") (pintype "passive"))
      (node (ref "U5") (pin "13") (pinfunction "IO_L23N_7_13") (pintype "bidirectional"))
    )
    (net (code "74") (name "/L_IO12") (class "Default")
      (node (ref "R5") (pin "2") (pinfunction "2_2") (pintype "passive"))
      (node (ref "U5") (pin "14") (pinfunction "IO_L24P_7_14") (pintype "bidirectional"))
    )
    (net (code "75") (name "/L_IO13") (class "Default")
      (node (ref "R7") (pin "2") (pinfunction "2_2") (pintype "passive"))
      (node (ref "U5") (pin "15") (pinfunction "IO_L24N_7_15") (pintype "bidirectional"))
    )
    (net (code "76") (name "/L_IO14") (class "Default")
      (node (ref "R9") (pin "2") (pinfunction "2_2") (pintype "passive"))
      (node (ref "U5") (pin "17") (pinfunction "IO_L40P_7_17") (pintype "bidirectional"))
    )
    (net (code "77") (name "/L_IO15") (class "Default")
      (node (ref "R4") (pin "2") (pinfunction "2_2") (pintype "passive"))
      (node (ref "U5") (pin "18") (pinfunction "IO_L40N_7/VREF_7_18") (pintype "bidirectional"))
    )
    (net (code "78") (name "/L_IO16") (class "Default")
      (node (ref "R6") (pin "2") (pinfunction "2_2") (pintype "passive"))
      (node (ref "U5") (pin "20") (pinfunction "IO_L40P_6/VREF_6_20") (pintype "bidirectional"))
    )
    (net (code "79") (name "/L_IO17") (class "Default")
      (node (ref "R8") (pin "2") (pinfunction "2_2") (pintype "passive"))
      (node (ref "U5") (pin "21") (pinfunction "IO_L40N_6_21") (pintype "bidirectional"))
    )
    (net (code "80") (name "/L_IO18") (class "Default")
      (node (ref "R10") (pin "2") (pinfunction "2_2") (pintype "passive"))
      (node (ref "U5") (pin "23") (pinfunction "IO_L24P_6_23") (pintype "bidirectional"))
    )
    (net (code "81") (name "/L_IO26") (class "Default")
      (node (ref "R11") (pin "2") (pinfunction "2_2") (pintype "passive"))
      (node (ref "U5") (pin "32") (pinfunction "IO_L20P_6_32") (pintype "bidirectional"))
    )
    (net (code "82") (name "/L_IO27") (class "Default")
      (node (ref "R13") (pin "2") (pinfunction "2_2") (pintype "passive"))
      (node (ref "U5") (pin "33") (pinfunction "IO_L20N_6_33") (pintype "bidirectional"))
    )
    (net (code "83") (name "/L_IO28") (class "Default")
      (node (ref "R15") (pin "2") (pinfunction "2_2") (pintype "passive"))
      (node (ref "U5") (pin "35") (pinfunction "IO_L01P_6/VRN_6_35") (pintype "bidirectional"))
    )
    (net (code "84") (name "/L_IO29") (class "Default")
      (node (ref "R17") (pin "2") (pinfunction "2_2") (pintype "passive"))
      (node (ref "U5") (pin "36") (pinfunction "IO_L01N_6/VRP_6_36") (pintype "bidirectional"))
    )
    (net (code "85") (name "/M1_1") (class "Default")
      (node (ref "R12") (pin "2") (pinfunction "2_2") (pintype "passive"))
      (node (ref "R53") (pin "1") (pinfunction "1_1") (pintype "passive"))
      (node (ref "U13") (pin "2") (pinfunction "INA_2") (pintype "input"))
    )
    (net (code "86") (name "/M1_2") (class "Default")
      (node (ref "R14") (pin "2") (pinfunction "2_2") (pintype "passive"))
      (node (ref "R63") (pin "1") (pinfunction "1_1") (pintype "passive"))
      (node (ref "U13") (pin "4") (pinfunction "INB_4") (pintype "input"))
    )
    (net (code "87") (name "/M1_3") (class "Default")
      (node (ref "R16") (pin "2") (pinfunction "2_2") (pintype "passive"))
      (node (ref "R76") (pin "1") (pinfunction "1_1") (pintype "passive"))
      (node (ref "U11") (pin "2") (pinfunction "INA_2") (pintype "input"))
    )
    (net (code "88") (name "/M1_4") (class "Default")
      (node (ref "R18") (pin "2") (pinfunction "2_2") (pintype "passive"))
      (node (ref "R94") (pin "1") (pinfunction "1_1") (pintype "passive"))
      (node (ref "U11") (pin "4") (pinfunction "INB_4") (pintype "input"))
    )
    (net (code "89") (name "/M1_5") (class "Default")
      (node (ref "R19") (pin "2") (pinfunction "2_2") (pintype "passive"))
      (node (ref "R99") (pin "1") (pinfunction "1_1") (pintype "passive"))
      (node (ref "U9") (pin "2") (pinfunction "INA_2") (pintype "input"))
    )
    (net (code "90") (name "/M1_6") (class "Default")
      (node (ref "R104") (pin "1") (pinfunction "1_1") (pintype "passive"))
      (node (ref "R23") (pin "2") (pinfunction "2_2") (pintype "passive"))
      (node (ref "U9") (pin "4") (pinfunction "INB_4") (pintype "input"))
    )
    (net (code "91") (name "/M2_1") (class "Default")
      (node (ref "R54") (pin "1") (pinfunction "1_1") (pintype "passive"))
      (node (ref "R6") (pin "1") (pinfunction "1_1") (pintype "passive"))
      (node (ref "U18") (pin "2") (pinfunction "INA_2") (pintype "input"))
    )
    (net (code "92") (name "/M2_2") (class "Default")
      (node (ref "R4") (pin "1") (pinfunction "1_1") (pintype "passive"))
      (node (ref "R64") (pin "1") (pinfunction "1_1") (pintype "passive"))
      (node (ref "U18") (pin "4") (pinfunction "INB_4") (pintype "input"))
    )
    (net (code "93") (name "/M2_3") (class "Default")
      (node (ref "R81") (pin "1") (pinfunction "1_1") (pintype "passive"))
      (node (ref "R9") (pin "1") (pinfunction "1_1") (pintype "passive"))
      (node (ref "U16") (pin "2") (pinfunction "INA_2") (pintype "input"))
    )
    (net (code "94") (name "/M2_4") (class "Default")
      (node (ref "R7") (pin "1") (pinfunction "1_1") (pintype "passive"))
      (node (ref "R95") (pin "1") (pinfunction "1_1") (pintype "passive"))
      (node (ref "U16") (pin "4") (pinfunction "INB_4") (pintype "input"))
    )
    (net (code "95") (name "/M2_5") (class "Default")
      (node (ref "R100") (pin "1") (pinfunction "1_1") (pintype "passive"))
      (node (ref "R5") (pin "1") (pinfunction "1_1") (pintype "passive"))
      (node (ref "U6") (pin "2") (pinfunction "INA_2") (pintype "input"))
    )
    (net (code "96") (name "/M2_6") (class "Default")
      (node (ref "R105") (pin "1") (pinfunction "1_1") (pintype "passive"))
      (node (ref "R2") (pin "1") (pinfunction "1_1") (pintype "passive"))
      (node (ref "U6") (pin "4") (pinfunction "INB_4") (pintype "input"))
    )
    (net (code "97") (name "/M3_1") (class "Default")
      (node (ref "R13") (pin "1") (pinfunction "1_1") (pintype "passive"))
      (node (ref "R56") (pin "1") (pinfunction "1_1") (pintype "passive"))
      (node (ref "U14") (pin "2") (pinfunction "INA_2") (pintype "input"))
    )
    (net (code "98") (name "/M3_2") (class "Default")
      (node (ref "R11") (pin "1") (pinfunction "1_1") (pintype "passive"))
      (node (ref "R69") (pin "1") (pinfunction "1_1") (pintype "passive"))
      (node (ref "U14") (pin "4") (pinfunction "INB_4") (pintype "input"))
    )
    (net (code "99") (name "/M3_3") (class "Default")
      (node (ref "R10") (pin "1") (pinfunction "1_1") (pintype "passive"))
      (node (ref "R82") (pin "1") (pinfunction "1_1") (pintype "passive"))
      (node (ref "U12") (pin "2") (pinfunction "INA_2") (pintype "input"))
    )
    (net (code "100") (name "/M3_4") (class "Default")
      (node (ref "R8") (pin "1") (pinfunction "1_1") (pintype "passive"))
      (node (ref "R96") (pin "1") (pinfunction "1_1") (pintype "passive"))
      (node (ref "U12") (pin "4") (pinfunction "INB_4") (pintype "input"))
    )
    (net (code "101") (name "/M3_5") (class "Default")
      (node (ref "R101") (pin "1") (pinfunction "1_1") (pintype "passive"))
      (node (ref "R17") (pin "1") (pinfunction "1_1") (pintype "passive"))
      (node (ref "U20") (pin "2") (pinfunction "INA_2") (pintype "input"))
    )
    (net (code "102") (name "/M3_6") (class "Default")
      (node (ref "R106") (pin "1") (pinfunction "1_1") (pintype "passive"))
      (node (ref "R15") (pin "1") (pinfunction "1_1") (pintype "passive"))
      (node (ref "U20") (pin "4") (pinfunction "INB_4") (pintype "input"))
    )
    (net (code "103") (name "/M4_1") (class "Default")
      (node (ref "R26") (pin "2") (pinfunction "2_2") (pintype "passive"))
      (node (ref "R57") (pin "1") (pinfunction "1_1") (pintype "passive"))
      (node (ref "U19") (pin "2") (pinfunction "INA_2") (pintype "input"))
    )
    (net (code "104") (name "/M4_2") (class "Default")
      (node (ref "R28") (pin "2") (pinfunction "2_2") (pintype "passive"))
      (node (ref "R70") (pin "1") (pinfunction "1_1") (pintype "passive"))
      (node (ref "U19") (pin "4") (pinfunction "INB_4") (pintype "input"))
    )
    (net (code "105") (name "/M4_3") (class "Default")
      (node (ref "R20") (pin "2") (pinfunction "2_2") (pintype "passive"))
      (node (ref "R87") (pin "1") (pinfunction "1_1") (pintype "passive"))
      (node (ref "U17") (pin "2") (pinfunction "INA_2") (pintype "input"))
    )
    (net (code "106") (name "/M4_4") (class "Default")
      (node (ref "R25") (pin "2") (pinfunction "2_2") (pintype "passive"))
      (node (ref "R97") (pin "1") (pinfunction "1_1") (pintype "passive"))
      (node (ref "U17") (pin "4") (pinfunction "INB_4") (pintype "input"))
    )
    (net (code "107") (name "/M4_5") (class "Default")
      (node (ref "R102") (pin "1") (pinfunction "1_1") (pintype "passive"))
      (node (ref "R27") (pin "2") (pinfunction "2_2") (pintype "passive"))
      (node (ref "U15") (pin "2") (pinfunction "INA_2") (pintype "input"))
    )
    (net (code "108") (name "/M4_6") (class "Default")
      (node (ref "R107") (pin "1") (pinfunction "1_1") (pintype "passive"))
      (node (ref "R29") (pin "2") (pinfunction "2_2") (pintype "passive"))
      (node (ref "U15") (pin "4") (pinfunction "INB_4") (pintype "input"))
    )
    (net (code "109") (name "/Md_1") (class "Default")
      (node (ref "R39") (pin "2") (pinfunction "2_2") (pintype "passive"))
      (node (ref "R58") (pin "1") (pinfunction "1_1") (pintype "passive"))
      (node (ref "U7") (pin "2") (pinfunction "INA_2") (pintype "input"))
    )
    (net (code "110") (name "/Md_2") (class "Default")
      (node (ref "R38") (pin "2") (pinfunction "2_2") (pintype "passive"))
      (node (ref "R75") (pin "1") (pinfunction "1_1") (pintype "passive"))
      (node (ref "U7") (pin "4") (pinfunction "INB_4") (pintype "input"))
    )
    (net (code "111") (name "/Md_3") (class "Default")
      (node (ref "R36") (pin "2") (pinfunction "2_2") (pintype "passive"))
      (node (ref "R88") (pin "1") (pinfunction "1_1") (pintype "passive"))
      (node (ref "U8") (pin "2") (pinfunction "INA_2") (pintype "input"))
    )
    (net (code "112") (name "/Md_4") (class "Default")
      (node (ref "R30") (pin "2") (pinfunction "2_2") (pintype "passive"))
      (node (ref "R98") (pin "1") (pinfunction "1_1") (pintype "passive"))
      (node (ref "U8") (pin "4") (pinfunction "INB_4") (pintype "input"))
    )
    (net (code "113") (name "/Md_5") (class "Default")
      (node (ref "R103") (pin "1") (pinfunction "1_1") (pintype "passive"))
      (node (ref "R35") (pin "2") (pinfunction "2_2") (pintype "passive"))
      (node (ref "U10") (pin "2") (pinfunction "INA_2") (pintype "input"))
    )
    (net (code "114") (name "/Md_6") (class "Default")
      (node (ref "R108") (pin "1") (pinfunction "1_1") (pintype "passive"))
      (node (ref "R37") (pin "2") (pinfunction "2_2") (pintype "passive"))
      (node (ref "U10") (pin "4") (pinfunction "INB_4") (pintype "input"))
    )
    (net (code "115") (name "/O11") (class "Default")
      (node (ref "MOTOR_1") (pin "3") (pinfunction "3_3") (pintype "passive"))
      (node (ref "Q10") (pin "5") (pinfunction "D_5") (pintype "passive"))
      (node (ref "Q10") (pin "6") (pinfunction "D_6") (pintype "passive"))
      (node (ref "Q10") (pin "7") (pinfunction "D_7") (pintype "passive"))
      (node (ref "Q10") (pin "8") (pinfunction "D_8") (pintype "passive"))
      (node (ref "Q8") (pin "5") (pinfunction "D_5") (pintype "passive"))
      (node (ref "Q8") (pin "6") (pinfunction "D_6") (pintype "passive"))
      (node (ref "Q8") (pin "7") (pinfunction "D_7") (pintype "passive"))
      (node (ref "Q8") (pin "8") (pinfunction "D_8") (pintype "passive"))
    )
    (net (code "116") (name "/O12") (class "Default")
      (node (ref "MOTOR_1") (pin "2") (pinfunction "2_2") (pintype "passive"))
      (node (ref "Q12") (pin "5") (pinfunction "D_5") (pintype "passive"))
      (node (ref "Q12") (pin "6") (pinfunction "D_6") (pintype "passive"))
      (node (ref "Q12") (pin "7") (pinfunction "D_7") (pintype "passive"))
      (node (ref "Q12") (pin "8") (pinfunction "D_8") (pintype "passive"))
      (node (ref "Q14") (pin "5") (pinfunction "D_5") (pintype "passive"))
      (node (ref "Q14") (pin "6") (pinfunction "D_6") (pintype "passive"))
      (node (ref "Q14") (pin "7") (pinfunction "D_7") (pintype "passive"))
      (node (ref "Q14") (pin "8") (pinfunction "D_8") (pintype "passive"))
    )
    (net (code "117") (name "/O13") (class "Default")
      (node (ref "MOTOR_1") (pin "1") (pinfunction "1_1") (pintype "passive"))
      (node (ref "Q16") (pin "5") (pinfunction "D_5") (pintype "passive"))
      (node (ref "Q16") (pin "6") (pinfunction "D_6") (pintype "passive"))
      (node (ref "Q16") (pin "7") (pinfunction "D_7") (pintype "passive"))
      (node (ref "Q16") (pin "8") (pinfunction "D_8") (pintype "passive"))
      (node (ref "Q18") (pin "5") (pinfunction "D_5") (pintype "passive"))
      (node (ref "Q18") (pin "6") (pinfunction "D_6") (pintype "passive"))
      (node (ref "Q18") (pin "7") (pinfunction "D_7") (pintype "passive"))
      (node (ref "Q18") (pin "8") (pinfunction "D_8") (pintype "passive"))
    )
    (net (code "118") (name "/O21") (class "Default")
      (node (ref "MOTOR_2") (pin "3") (pinfunction "3_3") (pintype "passive"))
      (node (ref "Q7") (pin "5") (pinfunction "D_5") (pintype "passive"))
      (node (ref "Q7") (pin "6") (pinfunction "D_6") (pintype "passive"))
      (node (ref "Q7") (pin "7") (pinfunction "D_7") (pintype "passive"))
      (node (ref "Q7") (pin "8") (pinfunction "D_8") (pintype "passive"))
      (node (ref "Q9") (pin "5") (pinfunction "D_5") (pintype "passive"))
      (node (ref "Q9") (pin "6") (pinfunction "D_6") (pintype "passive"))
      (node (ref "Q9") (pin "7") (pinfunction "D_7") (pintype "passive"))
      (node (ref "Q9") (pin "8") (pinfunction "D_8") (pintype "passive"))
    )
    (net (code "119") (name "/O22") (class "Default")
      (node (ref "MOTOR_2") (pin "2") (pinfunction "2_2") (pintype "passive"))
      (node (ref "Q11") (pin "5") (pinfunction "D_5") (pintype "passive"))
      (node (ref "Q11") (pin "6") (pinfunction "D_6") (pintype "passive"))
      (node (ref "Q11") (pin "7") (pinfunction "D_7") (pintype "passive"))
      (node (ref "Q11") (pin "8") (pinfunction "D_8") (pintype "passive"))
      (node (ref "Q13") (pin "5") (pinfunction "D_5") (pintype "passive"))
      (node (ref "Q13") (pin "6") (pinfunction "D_6") (pintype "passive"))
      (node (ref "Q13") (pin "7") (pinfunction "D_7") (pintype "passive"))
      (node (ref "Q13") (pin "8") (pinfunction "D_8") (pintype "passive"))
    )
    (net (code "120") (name "/O23") (class "Default")
      (node (ref "MOTOR_2") (pin "1") (pinfunction "1_1") (pintype "passive"))
      (node (ref "Q15") (pin "5") (pinfunction "D_5") (pintype "passive"))
      (node (ref "Q15") (pin "6") (pinfunction "D_6") (pintype "passive"))
      (node (ref "Q15") (pin "7") (pinfunction "D_7") (pintype "passive"))
      (node (ref "Q15") (pin "8") (pinfunction "D_8") (pintype "passive"))
      (node (ref "Q17") (pin "5") (pinfunction "D_5") (pintype "passive"))
      (node (ref "Q17") (pin "6") (pinfunction "D_6") (pintype "passive"))
      (node (ref "Q17") (pin "7") (pinfunction "D_7") (pintype "passive"))
      (node (ref "Q17") (pin "8") (pinfunction "D_8") (pintype "passive"))
    )
    (net (code "121") (name "/O31") (class "Default")
      (node (ref "MOTOR_3") (pin "3") (pinfunction "3_3") (pintype "passive"))
      (node (ref "Q19") (pin "5") (pinfunction "D_5") (pintype "passive"))
      (node (ref "Q19") (pin "6") (pinfunction "D_6") (pintype "passive"))
      (node (ref "Q19") (pin "7") (pinfunction "D_7") (pintype "passive"))
      (node (ref "Q19") (pin "8") (pinfunction "D_8") (pintype "passive"))
      (node (ref "Q21") (pin "5") (pinfunction "D_5") (pintype "passive"))
      (node (ref "Q21") (pin "6") (pinfunction "D_6") (pintype "passive"))
      (node (ref "Q21") (pin "7") (pinfunction "D_7") (pintype "passive"))
      (node (ref "Q21") (pin "8") (pinfunction "D_8") (pintype "passive"))
    )
    (net (code "122") (name "/O32") (class "Default")
      (node (ref "MOTOR_3") (pin "2") (pinfunction "2_2") (pintype "passive"))
      (node (ref "Q23") (pin "5") (pinfunction "D_5") (pintype "passive"))
      (node (ref "Q23") (pin "6") (pinfunction "D_6") (pintype "passive"))
      (node (ref "Q23") (pin "7") (pinfunction "D_7") (pintype "passive"))
      (node (ref "Q23") (pin "8") (pinfunction "D_8") (pintype "passive"))
      (node (ref "Q25") (pin "5") (pinfunction "D_5") (pintype "passive"))
      (node (ref "Q25") (pin "6") (pinfunction "D_6") (pintype "passive"))
      (node (ref "Q25") (pin "7") (pinfunction "D_7") (pintype "passive"))
      (node (ref "Q25") (pin "8") (pinfunction "D_8") (pintype "passive"))
    )
    (net (code "123") (name "/O33") (class "Default")
      (node (ref "MOTOR_3") (pin "1") (pinfunction "1_1") (pintype "passive"))
      (node (ref "Q27") (pin "5") (pinfunction "D_5") (pintype "passive"))
      (node (ref "Q27") (pin "6") (pinfunction "D_6") (pintype "passive"))
      (node (ref "Q27") (pin "7") (pinfunction "D_7") (pintype "passive"))
      (node (ref "Q27") (pin "8") (pinfunction "D_8") (pintype "passive"))
      (node (ref "Q29") (pin "5") (pinfunction "D_5") (pintype "passive"))
      (node (ref "Q29") (pin "6") (pinfunction "D_6") (pintype "passive"))
      (node (ref "Q29") (pin "7") (pinfunction "D_7") (pintype "passive"))
      (node (ref "Q29") (pin "8") (pinfunction "D_8") (pintype "passive"))
    )
    (net (code "124") (name "/O41") (class "Default")
      (node (ref "MOTOR_4") (pin "3") (pinfunction "3_3") (pintype "passive"))
      (node (ref "Q20") (pin "5") (pinfunction "D_5") (pintype "passive"))
      (node (ref "Q20") (pin "6") (pinfunction "D_6") (pintype "passive"))
      (node (ref "Q20") (pin "7") (pinfunction "D_7") (pintype "passive"))
      (node (ref "Q20") (pin "8") (pinfunction "D_8") (pintype "passive"))
      (node (ref "Q22") (pin "5") (pinfunction "D_5") (pintype "passive"))
      (node (ref "Q22") (pin "6") (pinfunction "D_6") (pintype "passive"))
      (node (ref "Q22") (pin "7") (pinfunction "D_7") (pintype "passive"))
      (node (ref "Q22") (pin "8") (pinfunction "D_8") (pintype "passive"))
    )
    (net (code "125") (name "/O42") (class "Default")
      (node (ref "MOTOR_4") (pin "2") (pinfunction "2_2") (pintype "passive"))
      (node (ref "Q24") (pin "5") (pinfunction "D_5") (pintype "passive"))
      (node (ref "Q24") (pin "6") (pinfunction "D_6") (pintype "passive"))
      (node (ref "Q24") (pin "7") (pinfunction "D_7") (pintype "passive"))
      (node (ref "Q24") (pin "8") (pinfunction "D_8") (pintype "passive"))
      (node (ref "Q26") (pin "5") (pinfunction "D_5") (pintype "passive"))
      (node (ref "Q26") (pin "6") (pinfunction "D_6") (pintype "passive"))
      (node (ref "Q26") (pin "7") (pinfunction "D_7") (pintype "passive"))
      (node (ref "Q26") (pin "8") (pinfunction "D_8") (pintype "passive"))
    )
    (net (code "126") (name "/O43") (class "Default")
      (node (ref "MOTOR_4") (pin "1") (pinfunction "1_1") (pintype "passive"))
      (node (ref "Q28") (pin "5") (pinfunction "D_5") (pintype "passive"))
      (node (ref "Q28") (pin "6") (pinfunction "D_6") (pintype "passive"))
      (node (ref "Q28") (pin "7") (pinfunction "D_7") (pintype "passive"))
      (node (ref "Q28") (pin "8") (pinfunction "D_8") (pintype "passive"))
      (node (ref "Q30") (pin "5") (pinfunction "D_5") (pintype "passive"))
      (node (ref "Q30") (pin "6") (pinfunction "D_6") (pintype "passive"))
      (node (ref "Q30") (pin "7") (pinfunction "D_7") (pintype "passive"))
      (node (ref "Q30") (pin "8") (pinfunction "D_8") (pintype "passive"))
    )
    (net (code "127") (name "/Od1") (class "Default")
      (node (ref "Dribbler") (pin "3") (pinfunction "3_3") (pintype "passive"))
      (node (ref "Q1") (pin "5") (pinfunction "D_5") (pintype "passive"))
      (node (ref "Q1") (pin "6") (pinfunction "D_6") (pintype "passive"))
      (node (ref "Q1") (pin "7") (pinfunction "D_7") (pintype "passive"))
      (node (ref "Q1") (pin "8") (pinfunction "D_8") (pintype "passive"))
      (node (ref "Q2") (pin "5") (pinfunction "D_5") (pintype "passive"))
      (node (ref "Q2") (pin "6") (pinfunction "D_6") (pintype "passive"))
      (node (ref "Q2") (pin "7") (pinfunction "D_7") (pintype "passive"))
      (node (ref "Q2") (pin "8") (pinfunction "D_8") (pintype "passive"))
    )
    (net (code "128") (name "/Od2") (class "Default")
      (node (ref "Dribbler") (pin "2") (pinfunction "2_2") (pintype "passive"))
      (node (ref "Q3") (pin "5") (pinfunction "D_5") (pintype "passive"))
      (node (ref "Q3") (pin "6") (pinfunction "D_6") (pintype "passive"))
      (node (ref "Q3") (pin "7") (pinfunction "D_7") (pintype "passive"))
      (node (ref "Q3") (pin "8") (pinfunction "D_8") (pintype "passive"))
      (node (ref "Q4") (pin "5") (pinfunction "D_5") (pintype "passive"))
      (node (ref "Q4") (pin "6") (pinfunction "D_6") (pintype "passive"))
      (node (ref "Q4") (pin "7") (pinfunction "D_7") (pintype "passive"))
      (node (ref "Q4") (pin "8") (pinfunction "D_8") (pintype "passive"))
    )
    (net (code "129") (name "/Od3") (class "Default")
      (node (ref "Dribbler") (pin "1") (pinfunction "1_1") (pintype "passive"))
      (node (ref "Q5") (pin "5") (pinfunction "D_5") (pintype "passive"))
      (node (ref "Q5") (pin "6") (pinfunction "D_6") (pintype "passive"))
      (node (ref "Q5") (pin "7") (pinfunction "D_7") (pintype "passive"))
      (node (ref "Q5") (pin "8") (pinfunction "D_8") (pintype "passive"))
      (node (ref "Q6") (pin "5") (pinfunction "D_5") (pintype "passive"))
      (node (ref "Q6") (pin "6") (pinfunction "D_6") (pintype "passive"))
      (node (ref "Q6") (pin "7") (pinfunction "D_7") (pintype "passive"))
      (node (ref "Q6") (pin "8") (pinfunction "D_8") (pintype "passive"))
    )
    (net (code "131") (name "/Over_Drib(3.3)") (class "Default")
      (node (ref "U2") (pin "17") (pinfunction "Y2_17") (pintype "tri_state"))
    )
    (net (code "132") (name "/P.R TDO") (class "Default")
      (node (ref "R341") (pin "1") (pinfunction "1_1") (pintype "passive"))
      (node (ref "U27") (pin "17") (pinfunction "TDO_17") (pintype "output"))
    )
    (net (code "133") (name "/PROG_B") (class "Default")
      (node (ref "R33") (pin "1") (pinfunction "1_1") (pintype "passive"))
      (node (ref "U27") (pin "7") (pinfunction "~{CF}_7") (pintype "open_collector"))
      (node (ref "U5") (pin "143") (pinfunction "PROG_B_143") (pintype "input"))
    )
    (net (code "134") (name "/R_IO1") (class "Default")
      (node (ref "Gyro & Accel") (pin "3") (pinfunction "3_3") (pintype "passive"))
      (node (ref "Gyro & Accel") (pin "6") (pinfunction "6_6") (pintype "passive"))
      (node (ref "R149") (pin "2") (pinfunction "2_2") (pintype "passive"))
      (node (ref "U5") (pin "108") (pinfunction "IO_L01N_2/VRP_2_108") (pintype "bidirectional"))
    )
    (net (code "135") (name "/R_IO2") (class "Default")
      (node (ref "Gyro & Accel") (pin "4") (pinfunction "4_4") (pintype "passive"))
      (node (ref "Gyro & Accel") (pin "7") (pinfunction "7_7") (pintype "passive"))
      (node (ref "R150") (pin "2") (pinfunction "2_2") (pintype "passive"))
      (node (ref "U5") (pin "107") (pinfunction "IO_L01P_2/VRN_2_107") (pintype "bidirectional"))
    )
    (net (code "136") (name "/R_IO3") (class "Default")
      (node (ref "U3") (pin "14") (pinfunction "Y5_14") (pintype "tri_state"))
      (node (ref "U5") (pin "105") (pinfunction "IO_L20N_2_105") (pintype "bidirectional"))
    )
    (net (code "137") (name "/R_IO7") (class "Default")
      (node (ref "R12") (pin "1") (pinfunction "1_1") (pintype "passive"))
      (node (ref "U5") (pin "100") (pinfunction "IO_L22N_2_100") (pintype "bidirectional"))
    )
    (net (code "138") (name "/R_IO8") (class "Default")
      (node (ref "R14") (pin "1") (pinfunction "1_1") (pintype "passive"))
      (node (ref "U5") (pin "99") (pinfunction "IO_L22P_2_99") (pintype "bidirectional"))
    )
    (net (code "139") (name "/R_IO9") (class "Default")
      (node (ref "R16") (pin "1") (pinfunction "1_1") (pintype "passive"))
      (node (ref "U5") (pin "98") (pinfunction "IO_L23N_2/VREF_2_98") (pintype "bidirectional"))
    )
    (net (code "140") (name "/R_IO10") (class "Default")
      (node (ref "R18") (pin "1") (pinfunction "1_1") (pintype "passive"))
      (node (ref "U5") (pin "97") (pinfunction "IO_L23P_2_97") (pintype "bidirectional"))
    )
    (net (code "141") (name "/R_IO11") (class "Default")
      (node (ref "R19") (pin "1") (pinfunction "1_1") (pintype "passive"))
      (node (ref "U5") (pin "96") (pinfunction "IO_L24N_2_96") (pintype "bidirectional"))
    )
    (net (code "142") (name "/R_IO12") (class "Default")
      (node (ref "R23") (pin "1") (pinfunction "1_1") (pintype "passive"))
      (node (ref "U5") (pin "95") (pinfunction "IO_L24P_2_95") (pintype "bidirectional"))
    )
    (net (code "143") (name "/R_IO13") (class "Default")
      (node (ref "R26") (pin "1") (pinfunction "1_1") (pintype "passive"))
      (node (ref "U5") (pin "93") (pinfunction "IO_L40N_2_93") (pintype "bidirectional"))
    )
    (net (code "144") (name "/R_IO14") (class "Default")
      (node (ref "R28") (pin "1") (pinfunction "1_1") (pintype "passive"))
      (node (ref "U5") (pin "92") (pinfunction "IO_L40P_2/VREF_2_92") (pintype "bidirectional"))
    )
    (net (code "145") (name "/R_IO22") (class "Default")
      (node (ref "R20") (pin "1") (pinfunction "1_1") (pintype "passive"))
      (node (ref "U5") (pin "82") (pinfunction "IO_L22P_3_82") (pintype "bidirectional"))
    )
    (net (code "146") (name "/R_IO23") (class "Default")
      (node (ref "R25") (pin "1") (pinfunction "1_1") (pintype "passive"))
      (node (ref "U5") (pin "80") (pinfunction "IO_L21N_3_80") (pintype "bidirectional"))
    )
    (net (code "147") (name "/R_IO24") (class "Default")
      (node (ref "R27") (pin "1") (pinfunction "1_1") (pintype "passive"))
      (node (ref "U5") (pin "79") (pinfunction "IO_L21P_3_79") (pintype "bidirectional"))
    )
    (net (code "148") (name "/R_IO25") (class "Default")
      (node (ref "R29") (pin "1") (pinfunction "1_1") (pintype "passive"))
      (node (ref "U5") (pin "78") (pinfunction "IO_L20N_3_78") (pintype "bidirectional"))
    )
    (net (code "149") (name "/R_IO26") (class "Default")
      (node (ref "R120") (pin "1") (pinfunction "1_1") (pintype "passive"))
      (node (ref "S2D3") (pin "2") (pinfunction "A1_2") (pintype "input"))
      (node (ref "U5") (pin "77") (pinfunction "IO_L20P_3_77") (pintype "bidirectional"))
    )
    (net (code "150") (name "/R_IO27") (class "Default")
      (node (ref "R121") (pin "1") (pinfunction "1_1") (pintype "passive"))
      (node (ref "S2D3") (pin "3") (pinfunction "A2_3") (pintype "input"))
      (node (ref "U5") (pin "76") (pinfunction "IO_76") (pintype "bidirectional"))
    )
    (net (code "151") (name "/R_IO28") (class "Default")
      (node (ref "R123") (pin "1") (pinfunction "1_1") (pintype "passive"))
      (node (ref "S2D3") (pin "4") (pinfunction "A3_4") (pintype "input"))
      (node (ref "U5") (pin "74") (pinfunction "IO_L01N_3/VRP_3_74") (pintype "bidirectional"))
    )
    (net (code "152") (name "/R_IO29") (class "Default")
      (node (ref "R124") (pin "1") (pinfunction "1_1") (pintype "passive"))
      (node (ref "S2D3") (pin "5") (pinfunction "A4_5") (pintype "input"))
      (node (ref "U5") (pin "73") (pinfunction "IO_L01P_3/VRN_3_73") (pintype "bidirectional"))
    )
    (net (code "153") (name "/S_TDO") (class "Default")
      (node (ref "P13") (pin "4") (pinfunction "4_4") (pintype "passive"))
      (node (ref "U5") (pin "109") (pinfunction "TDO_109") (pintype "output"))
    )
    (net (code "154") (name "/Servo_O") (class "Default")
      (node (ref "P1") (pin "1") (pinfunction "1_1") (pintype "passive"))
      (node (ref "S2D3") (pin "18") (pinfunction "Y1_18") (pintype "tri_state"))
    )
    (net (code "155") (name "/Shoot_pulse") (class "Default")
      (node (ref "Booster") (pin "1") (pinfunction "1_1") (pintype "passive"))
      (node (ref "R116") (pin "2") (pinfunction "2_2") (pintype "passive"))
      (node (ref "U5") (pin "118") (pinfunction "IO_L28P_1_118") (pintype "bidirectional"))
    )
    (net (code "156") (name "/TCK") (class "Default")
      (node (ref "P13") (pin "3") (pinfunction "3_3") (pintype "passive"))
      (node (ref "R342") (pin "1") (pinfunction "1_1") (pintype "passive"))
      (node (ref "U27") (pin "6") (pinfunction "TCK_6") (pintype "input"))
    )
    (net (code "157") (name "/TDI") (class "Default")
      (node (ref "P13") (pin "5") (pinfunction "5_5") (pintype "passive"))
      (node (ref "U27") (pin "4") (pinfunction "TDI_4") (pintype "input"))
    )
    (net (code "158") (name "/TMS") (class "Default")
      (node (ref "P13") (pin "6") (pinfunction "6_6") (pintype "passive"))
      (node (ref "R343") (pin "1") (pinfunction "1_1") (pintype "passive"))
      (node (ref "U27") (pin "5") (pinfunction "TMS_5") (pintype "input"))
    )
    (net (code "159") (name "/U_IO1") (class "Default")
      (node (ref "R35") (pin "1") (pinfunction "1_1") (pintype "passive"))
      (node (ref "U5") (pin "141") (pinfunction "IO_L01N_0/VRP_0_141") (pintype "bidirectional"))
    )
    (net (code "160") (name "/U_IO2") (class "Default")
      (node (ref "R37") (pin "1") (pinfunction "1_1") (pintype "passive"))
      (node (ref "U5") (pin "140") (pinfunction "IO_L01P_0/VRN_0_140") (pintype "bidirectional"))
    )
    (net (code "161") (name "/U_IO3") (class "Default")
      (node (ref "Gyro & Accel") (pin "11") (pinfunction "11_11") (pintype "passive"))
      (node (ref "R160") (pin "2") (pinfunction "2_2") (pintype "passive"))
      (node (ref "U5") (pin "137") (pinfunction "IO_L27N_0_137") (pintype "bidirectional"))
    )
    (net (code "162") (name "/U_IO4") (class "Default")
      (node (ref "Gyro & Accel") (pin "10") (pinfunction "10_10") (pintype "passive"))
      (node (ref "R159") (pin "1") (pinfunction "1_1") (pintype "passive"))
      (node (ref "U5") (pin "135") (pinfunction "IO_L27P_0_135") (pintype "bidirectional"))
    )
    (net (code "163") (name "/U_IO5") (class "Default")
      (node (ref "R113") (pin "1") (pinfunction "1_1") (pintype "passive"))
      (node (ref "S_D_1") (pin "2") (pinfunction "2_2") (pintype "passive"))
      (node (ref "U5") (pin "127") (pinfunction "IO_L32P_0/GCLK6_127") (pintype "bidirectional"))
    )
    (net (code "164") (name "/U_IO6") (class "Default")
      (node (ref "R133") (pin "1") (pinfunction "1_1") (pintype "passive"))
      (node (ref "S_D_2") (pin "2") (pinfunction "2_2") (pintype "passive"))
      (node (ref "U5") (pin "125") (pinfunction "IO_L32N_1/GCLK5_125") (pintype "bidirectional"))
    )
    (net (code "165") (name "/U_IO7") (class "Default")
      (node (ref "R153") (pin "1") (pinfunction "1_1") (pintype "passive"))
      (node (ref "S_D_3") (pin "2") (pinfunction "2_2") (pintype "passive"))
      (node (ref "U5") (pin "124") (pinfunction "IO_L32P_1/GCLK4_124") (pintype "bidirectional"))
    )
    (net (code "166") (name "/U_IO8") (class "Default")
      (node (ref "R173") (pin "1") (pinfunction "1_1") (pintype "passive"))
      (node (ref "S_D_4") (pin "2") (pinfunction "2_2") (pintype "passive"))
      (node (ref "U5") (pin "123") (pinfunction "IO_L31N_1/VREF_1_123") (pintype "bidirectional"))
    )
    (net (code "167") (name "/U_IO9") (class "Default")
      (node (ref "C64") (pin "2") (pinfunction "2_2") (pintype "passive"))
      (node (ref "P2") (pin "2") (pinfunction "2_2") (pintype "passive"))
      (node (ref "R55") (pin "1") (pinfunction "1_1") (pintype "passive"))
      (node (ref "R93") (pin "2") (pinfunction "2_2") (pintype "passive"))
      (node (ref "U5") (pin "122") (pinfunction "IO_L31P_1_122") (pintype "bidirectional"))
    )
    (net (code "168") (name "/U_IO10") (class "Default")
      (node (ref "R333") (pin "2") (pinfunction "2_2") (pintype "passive"))
      (node (ref "U5") (pin "119") (pinfunction "IO_L28N_1_119") (pintype "bidirectional"))
    )
    (net (code "169") (name "/U_IO14") (class "Default")
      (node (ref "Gyro & Accel") (pin "8") (pinfunction "8_8") (pintype "passive"))
      (node (ref "R155") (pin "1") (pinfunction "1_1") (pintype "passive"))
      (node (ref "U5") (pin "112") (pinfunction "IO_L01P_1/VRN_1_112") (pintype "bidirectional"))
    )
    (net (code "170") (name "/booster_ready") (class "Default")
      (node (ref "Booster") (pin "4") (pinfunction "4_4") (pintype "passive"))
      (node (ref "U3") (pin "6") (pinfunction "A5_6") (pintype "input"))
    )
    (net (code "171") (name "/buzzer") (class "Default")
      (node (ref "R_Buzz") (pin "1") (pinfunction "1_1") (pintype "passive"))
      (node (ref "S2D3") (pin "12") (pinfunction "Y7_12") (pintype "tri_state"))
    )
    (net (code "172") (name "/debug_D_1") (class "Default")
      (node (ref "D_D_1") (pin "1") (pinfunction "A_1") (pintype "passive"))
      (node (ref "S2D3") (pin "13") (pinfunction "Y6_13") (pintype "tri_state"))
    )
    (net (code "173") (name "/debug_D_2") (class "Default")
      (node (ref "D_D_2") (pin "1") (pinfunction "A_1") (pintype "passive"))
      (node (ref "S2D3") (pin "15") (pinfunction "Y4_15") (pintype "tri_state"))
    )
    (net (code "174") (name "/debug_D_3") (class "Default")
      (node (ref "D_D_3") (pin "1") (pinfunction "A_1") (pintype "passive"))
      (node (ref "S2D3") (pin "17") (pinfunction "Y2_17") (pintype "tri_state"))
    )
    (net (code "175") (name "/debug_D_4") (class "Default")
      (node (ref "D_D_4") (pin "1") (pinfunction "A_1") (pintype "passive"))
      (node (ref "S2D3") (pin "16") (pinfunction "Y3_16") (pintype "tri_state"))
    )
    (net (code "176") (name "GND") (class "Default")
      (node (ref "Antenna") (pin "1") (pinfunction "1_1") (pintype "passive"))
      (node (ref "Antenna") (pin "2") (pinfunction "2_2") (pintype "passive"))
      (node (ref "Antenna") (pin "4") (pinfunction "4_4") (pintype "passive"))
      (node (ref "Antenna") (pin "5") (pinfunction "5_5") (pintype "passive"))
      (node (ref "Battery") (pin "1") (pinfunction "1_1") (pintype "passive"))
      (node (ref "C(tele)") (pin "2") (pinfunction "2_2") (pintype "passive"))
      (node (ref "C1") (pin "2") (pinfunction "2_2") (pintype "passive"))
      (node (ref "C10") (pin "2") (pinfunction "2_2") (pintype "passive"))
      (node (ref "C11") (pin "1") (pinfunction "1_1") (pintype "passive"))
      (node (ref "C110") (pin "2") (pinfunction "2_2") (pintype "passive"))
      (node (ref "C12") (pin "1") (pinfunction "1_1") (pintype "passive"))
      (node (ref "C120") (pin "2") (pinfunction "2_2") (pintype "passive"))
      (node (ref "C13") (pin "1") (pinfunction "1_1") (pintype "passive"))
      (node (ref "C130") (pin "2") (pinfunction "2_2") (pintype "passive"))
      (node (ref "C14") (pin "1") (pinfunction "1_1") (pintype "passive"))
      (node (ref "C15") (pin "1") (pinfunction "1_1") (pintype "passive"))
      (node (ref "C16") (pin "1") (pinfunction "1_1") (pintype "passive"))
      (node (ref "C17") (pin "1") (pinfunction "1_1") (pintype "passive"))
      (node (ref "C18") (pin "1") (pinfunction "1_1") (pintype "passive"))
      (node (ref "C19") (pin "1") (pinfunction "1_1") (pintype "passive"))
      (node (ref "C2") (pin "2") (pinfunction "2_2") (pintype "passive"))
      (node (ref "C2(tele)") (pin "2") (pinfunction "2_2") (pintype "passive"))
      (node (ref "C20") (pin "2") (pinfunction "2_2") (pintype "passive"))
      (node (ref "C21") (pin "2") (pinfunction "2_2") (pintype "passive"))
      (node (ref "C22") (pin "1") (pinfunction "1_1") (pintype "passive"))
      (node (ref "C23") (pin "1") (pinfunction "1_1") (pintype "passive"))
      (node (ref "C24") (pin "1") (pinfunction "1_1") (pintype "passive"))
      (node (ref "C25") (pin "1") (pinfunction "1_1") (pintype "passive"))
      (node (ref "C26") (pin "1") (pinfunction "1_1") (pintype "passive"))
      (node (ref "C27") (pin "1") (pinfunction "1_1") (pintype "passive"))
      (node (ref "C28") (pin "1") (pinfunction "1_1") (pintype "passive"))
      (node (ref "C29") (pin "1") (pinfunction "1_1") (pintype "passive"))
      (node (ref "C3") (pin "2") (pinfunction "2_2") (pintype "passive"))
      (node (ref "C30") (pin "1") (pinfunction "1_1") (pintype "passive"))
      (node (ref "C31") (pin "1") (pinfunction "1_1") (pintype "passive"))
      (node (ref "C32") (pin "1") (pinfunction "1_1") (pintype "passive"))
      (node (ref "C33") (pin "1") (pinfunction "1_1") (pintype "passive"))
      (node (ref "C34") (pin "1") (pinfunction "1_1") (pintype "passive"))
      (node (ref "C35") (pin "1") (pinfunction "1_1") (pintype "passive"))
      (node (ref "C36") (pin "1") (pinfunction "1_1") (pintype "passive"))
      (node (ref "C37") (pin "1") (pinfunction "1_1") (pintype "passive"))
      (node (ref "C38") (pin "1") (pinfunction "1_1") (pintype "passive"))
      (node (ref "C39") (pin "1") (pinfunction "1_1") (pintype "passive"))
      (node (ref "C4") (pin "1") (pinfunction "1_1") (pintype "passive"))
      (node (ref "C40") (pin "1") (pinfunction "1_1") (pintype "passive"))
      (node (ref "C41") (pin "1") (pinfunction "1_1") (pintype "passive"))
      (node (ref "C42") (pin "1") (pinfunction "1_1") (pintype "passive"))
      (node (ref "C43") (pin "1") (pinfunction "1_1") (pintype "passive"))
      (node (ref "C44") (pin "1") (pinfunction "1_1") (pintype "passive"))
      (node (ref "C45") (pin "1") (pinfunction "1_1") (pintype "passive"))
      (node (ref "C46") (pin "1") (pinfunction "1_1") (pintype "passive"))
      (node (ref "C47") (pin "1") (pinfunction "1_1") (pintype "passive"))
      (node (ref "C48") (pin "1") (pinfunction "1_1") (pintype "passive"))
      (node (ref "C49") (pin "1") (pinfunction "1_1") (pintype "passive"))
      (node (ref "C5") (pin "2") (pinfunction "2_2") (pintype "passive"))
      (node (ref "C50") (pin "1") (pinfunction "1_1") (pintype "passive"))
      (node (ref "C51") (pin "1") (pinfunction "1_1") (pintype "passive"))
      (node (ref "C52") (pin "1") (pinfunction "1_1") (pintype "passive"))
      (node (ref "C53") (pin "1") (pinfunction "1_1") (pintype "passive"))
      (node (ref "C54") (pin "1") (pinfunction "1_1") (pintype "passive"))
      (node (ref "C55") (pin "1") (pinfunction "1_1") (pintype "passive"))
      (node (ref "C56") (pin "1") (pinfunction "1_1") (pintype "passive"))
      (node (ref "C57") (pin "1") (pinfunction "1_1") (pintype "passive"))
      (node (ref "C58") (pin "1") (pinfunction "1_1") (pintype "passive"))
      (node (ref "C59") (pin "1") (pinfunction "1_1") (pintype "passive"))
      (node (ref "C6") (pin "2") (pinfunction "2_2") (pintype "passive"))
      (node (ref "C60") (pin "1") (pinfunction "1_1") (pintype "passive"))
      (node (ref "C61") (pin "1") (pinfunction "1_1") (pintype "passive"))
      (node (ref "C62") (pin "1") (pinfunction "1_1") (pintype "passive"))
      (node (ref "C63") (pin "2") (pinfunction "2_2") (pintype "passive"))
      (node (ref "C64") (pin "1") (pinfunction "1_1") (pintype "passive"))
      (node (ref "C65") (pin "2") (pinfunction "2_2") (pintype "passive"))
      (node (ref "C66") (pin "2") (pinfunction "2_2") (pintype "passive"))
      (node (ref "C67") (pin "2") (pinfunction "2_2") (pintype "passive"))
      (node (ref "C68") (pin "2") (pinfunction "2_2") (pintype "passive"))
      (node (ref "C69") (pin "2") (pinfunction "2_2") (pintype "passive"))
      (node (ref "C7") (pin "2") (pinfunction "2_2") (pintype "passive"))
      (node (ref "C70") (pin "2") (pinfunction "2_2") (pintype "passive"))
      (node (ref "C71") (pin "2") (pinfunction "2_2") (pintype "passive"))
      (node (ref "C72") (pin "2") (pinfunction "2_2") (pintype "passive"))
      (node (ref "C73") (pin "1") (pinfunction "1_1") (pintype "passive"))
      (node (ref "C74") (pin "1") (pinfunction "1_1") (pintype "passive"))
      (node (ref "C75") (pin "1") (pinfunction "1_1") (pintype "passive"))
      (node (ref "C76") (pin "1") (pinfunction "1_1") (pintype "passive"))
      (node (ref "C77") (pin "1") (pinfunction "1_1") (pintype "passive"))
      (node (ref "C78") (pin "1") (pinfunction "1_1") (pintype "passive"))
      (node (ref "C79") (pin "1") (pinfunction "1_1") (pintype "passive"))
      (node (ref "C8") (pin "2") (pinfunction "2_2") (pintype "passive"))
      (node (ref "C80") (pin "2") (pinfunction "2_2") (pintype "passive"))
      (node (ref "C81") (pin "2") (pinfunction "2_2") (pintype "passive"))
      (node (ref "C9") (pin "2") (pinfunction "2_2") (pintype "passive"))
      (node (ref "C_1") (pin "2") (pinfunction "2_2") (pintype "passive"))
      (node (ref "C_16") (pin "2") (pinfunction "2_2") (pintype "passive"))
      (node (ref "C_17") (pin "2") (pinfunction "2_2") (pintype "passive"))
      (node (ref "C_19") (pin "2") (pinfunction "2_2") (pintype "passive"))
      (node (ref "C_ADC") (pin "1") (pinfunction "1_1") (pintype "passive"))
      (node (ref "C_DRIBBLER") (pin "1") (pinfunction "1_1") (pintype "passive"))
      (node (ref "C_IR") (pin "2") (pinfunction "2_2") (pintype "passive"))
      (node (ref "C_M1") (pin "1") (pinfunction "1_1") (pintype "passive"))
      (node (ref "C_M2") (pin "1") (pinfunction "1_1") (pintype "passive"))
      (node (ref "C_M3") (pin "1") (pinfunction "1_1") (pintype "passive"))
      (node (ref "C_M4") (pin "1") (pinfunction "1_1") (pintype "passive"))
      (node (ref "C_MIKONA") (pin "1") (pinfunction "1_1") (pintype "passive"))
      (node (ref "CnRF") (pin "1") (pinfunction "1_1") (pintype "passive"))
      (node (ref "D_REV") (pin "1") (pinfunction "A_1") (pintype "passive"))
      (node (ref "D_correction") (pin "1") (pinfunction "A_1") (pintype "passive"))
      (node (ref "Dribbler") (pin "5") (pinfunction "5_5") (pintype "passive"))
      (node (ref "Gyro & Accel") (pin "12") (pinfunction "12_12") (pintype "passive"))
      (node (ref "Gyro & Accel") (pin "13") (pinfunction "13_13") (pintype "passive"))
      (node (ref "Gyro & Accel") (pin "5") (pinfunction "5_5") (pintype "passive"))
      (node (ref "MOTOR_1") (pin "5") (pinfunction "5_5") (pintype "passive"))
      (node (ref "MOTOR_2") (pin "5") (pinfunction "5_5") (pintype "passive"))
      (node (ref "MOTOR_3") (pin "5") (pinfunction "5_5") (pintype "passive"))
      (node (ref "MOTOR_4") (pin "5") (pinfunction "5_5") (pintype "passive"))
      (node (ref "MinMax") (pin "17") (pinfunction "17_17") (pintype "passive"))
      (node (ref "MinMax") (pin "4") (pinfunction "4_4") (pintype "passive"))
      (node (ref "MinMax") (pin "6") (pinfunction "6_6") (pintype "passive"))
      (node (ref "P1") (pin "3") (pinfunction "3_3") (pintype "passive"))
      (node (ref "P13") (pin "2") (pinfunction "2_2") (pintype "passive"))
      (node (ref "P2") (pin "1") (pinfunction "1_1") (pintype "passive"))
      (node (ref "Q10") (pin "1") (pinfunction "S_1") (pintype "passive"))
      (node (ref "Q10") (pin "2") (pinfunction "S_2") (pintype "passive"))
      (node (ref "Q10") (pin "3") (pinfunction "S_3") (pintype "passive"))
      (node (ref "Q13") (pin "1") (pinfunction "S_1") (pintype "passive"))
      (node (ref "Q13") (pin "2") (pinfunction "S_2") (pintype "passive"))
      (node (ref "Q13") (pin "3") (pinfunction "S_3") (pintype "passive"))
      (node (ref "Q14") (pin "1") (pinfunction "S_1") (pintype "passive"))
      (node (ref "Q14") (pin "2") (pinfunction "S_2") (pintype "passive"))
      (node (ref "Q14") (pin "3") (pinfunction "S_3") (pintype "passive"))
      (node (ref "Q17") (pin "1") (pinfunction "S_1") (pintype "passive"))
      (node (ref "Q17") (pin "2") (pinfunction "S_2") (pintype "passive"))
      (node (ref "Q17") (pin "3") (pinfunction "S_3") (pintype "passive"))
      (node (ref "Q18") (pin "1") (pinfunction "S_1") (pintype "passive"))
      (node (ref "Q18") (pin "2") (pinfunction "S_2") (pintype "passive"))
      (node (ref "Q18") (pin "3") (pinfunction "S_3") (pintype "passive"))
      (node (ref "Q2") (pin "1") (pinfunction "S_1") (pintype "passive"))
      (node (ref "Q2") (pin "2") (pinfunction "S_2") (pintype "passive"))
      (node (ref "Q2") (pin "3") (pinfunction "S_3") (pintype "passive"))
      (node (ref "Q21") (pin "1") (pinfunction "S_1") (pintype "passive"))
      (node (ref "Q21") (pin "2") (pinfunction "S_2") (pintype "passive"))
      (node (ref "Q21") (pin "3") (pinfunction "S_3") (pintype "passive"))
      (node (ref "Q22") (pin "1") (pinfunction "S_1") (pintype "passive"))
      (node (ref "Q22") (pin "2") (pinfunction "S_2") (pintype "passive"))
      (node (ref "Q22") (pin "3") (pinfunction "S_3") (pintype "passive"))
      (node (ref "Q25") (pin "1") (pinfunction "S_1") (pintype "passive"))
      (node (ref "Q25") (pin "2") (pinfunction "S_2") (pintype "passive"))
      (node (ref "Q25") (pin "3") (pinfunction "S_3") (pintype "passive"))
      (node (ref "Q26") (pin "1") (pinfunction "S_1") (pintype "passive"))
      (node (ref "Q26") (pin "2") (pinfunction "S_2") (pintype "passive"))
      (node (ref "Q26") (pin "3") (pinfunction "S_3") (pintype "passive"))
      (node (ref "Q29") (pin "1") (pinfunction "S_1") (pintype "passive"))
      (node (ref "Q29") (pin "2") (pinfunction "S_2") (pintype "passive"))
      (node (ref "Q29") (pin "3") (pinfunction "S_3") (pintype "passive"))
      (node (ref "Q30") (pin "1") (pinfunction "S_1") (pintype "passive"))
      (node (ref "Q30") (pin "2") (pinfunction "S_2") (pintype "passive"))
      (node (ref "Q30") (pin "3") (pinfunction "S_3") (pintype "passive"))
      (node (ref "Q4") (pin "1") (pinfunction "S_1") (pintype "passive"))
      (node (ref "Q4") (pin "2") (pinfunction "S_2") (pintype "passive"))
      (node (ref "Q4") (pin "3") (pinfunction "S_3") (pintype "passive"))
      (node (ref "Q6") (pin "1") (pinfunction "S_1") (pintype "passive"))
      (node (ref "Q6") (pin "2") (pinfunction "S_2") (pintype "passive"))
      (node (ref "Q6") (pin "3") (pinfunction "S_3") (pintype "passive"))
      (node (ref "Q9") (pin "1") (pinfunction "S_1") (pintype "passive"))
      (node (ref "Q9") (pin "2") (pinfunction "S_2") (pintype "passive"))
      (node (ref "Q9") (pin "3") (pinfunction "S_3") (pintype "passive"))
      (node (ref "Q_BUZZ") (pin "2") (pinfunction "E_2") (pintype "passive"))
      (node (ref "R1") (pin "2") (pinfunction "2_2") (pintype "passive"))
      (node (ref "R100") (pin "2") (pinfunction "2_2") (pintype "passive"))
      (node (ref "R101") (pin "2") (pinfunction "2_2") (pintype "passive"))
      (node (ref "R102") (pin "2") (pinfunction "2_2") (pintype "passive"))
      (node (ref "R103") (pin "2") (pinfunction "2_2") (pintype "passive"))
      (node (ref "R104") (pin "2") (pinfunction "2_2") (pintype "passive"))
      (node (ref "R105") (pin "2") (pinfunction "2_2") (pintype "passive"))
      (node (ref "R106") (pin "2") (pinfunction "2_2") (pintype "passive"))
      (node (ref "R107") (pin "2") (pinfunction "2_2") (pintype "passive"))
      (node (ref "R108") (pin "2") (pinfunction "2_2") (pintype "passive"))
      (node (ref "R114") (pin "2") (pinfunction "2_2") (pintype "passive"))
      (node (ref "R120") (pin "2") (pinfunction "2_2") (pintype "passive"))
      (node (ref "R121") (pin "2") (pinfunction "2_2") (pintype "passive"))
      (node (ref "R122") (pin "1") (pinfunction "1_1") (pintype "passive"))
      (node (ref "R123") (pin "2") (pinfunction "2_2") (pintype "passive"))
      (node (ref "R124") (pin "2") (pinfunction "2_2") (pintype "passive"))
      (node (ref "R125") (pin "2") (pinfunction "2_2") (pintype "passive"))
      (node (ref "R126") (pin "2") (pinfunction "2_2") (pintype "passive"))
      (node (ref "R134") (pin "2") (pinfunction "2_2") (pintype "passive"))
      (node (ref "R154") (pin "2") (pinfunction "2_2") (pintype "passive"))
      (node (ref "R155") (pin "2") (pinfunction "2_2") (pintype "passive"))
      (node (ref "R156") (pin "2") (pinfunction "2_2") (pintype "passive"))
      (node (ref "R157") (pin "2") (pinfunction "2_2") (pintype "passive"))
      (node (ref "R159") (pin "2") (pinfunction "2_2") (pintype "passive"))
      (node (ref "R160") (pin "1") (pinfunction "1_1") (pintype "passive"))
      (node (ref "R174") (pin "2") (pinfunction "2_2") (pintype "passive"))
      (node (ref "R2.5") (pin "1") (pinfunction "1_1") (pintype "passive"))
      (node (ref "R21") (pin "1") (pinfunction "1_1") (pintype "passive"))
      (node (ref "R22") (pin "2") (pinfunction "2_2") (pintype "passive"))
      (node (ref "R24") (pin "1") (pinfunction "1_1") (pintype "passive"))
      (node (ref "R3") (pin "1") (pinfunction "1_1") (pintype "passive"))
      (node (ref "R346") (pin "1") (pinfunction "1_1") (pintype "passive"))
      (node (ref "R45") (pin "1") (pinfunction "1_1") (pintype "passive"))
      (node (ref "R53") (pin "2") (pinfunction "2_2") (pintype "passive"))
      (node (ref "R54") (pin "2") (pinfunction "2_2") (pintype "passive"))
      (node (ref "R56") (pin "2") (pinfunction "2_2") (pintype "passive"))
      (node (ref "R57") (pin "2") (pinfunction "2_2") (pintype "passive"))
      (node (ref "R58") (pin "2") (pinfunction "2_2") (pintype "passive"))
      (node (ref "R63") (pin "2") (pinfunction "2_2") (pintype "passive"))
      (node (ref "R64") (pin "2") (pinfunction "2_2") (pintype "passive"))
      (node (ref "R69") (pin "2") (pinfunction "2_2") (pintype "passive"))
      (node (ref "R70") (pin "2") (pinfunction "2_2") (pintype "passive"))
      (node (ref "R75") (pin "2") (pinfunction "2_2") (pintype "passive"))
      (node (ref "R76") (pin "2") (pinfunction "2_2") (pintype "passive"))
      (node (ref "R81") (pin "2") (pinfunction "2_2") (pintype "passive"))
      (node (ref "R82") (pin "2") (pinfunction "2_2") (pintype "passive"))
      (node (ref "R87") (pin "2") (pinfunction "2_2") (pintype "passive"))
      (node (ref "R88") (pin "2") (pinfunction "2_2") (pintype "passive"))
      (node (ref "R93") (pin "1") (pinfunction "1_1") (pintype "passive"))
      (node (ref "R94") (pin "2") (pinfunction "2_2") (pintype "passive"))
      (node (ref "R95") (pin "2") (pinfunction "2_2") (pintype "passive"))
      (node (ref "R96") (pin "2") (pinfunction "2_2") (pintype "passive"))
      (node (ref "R97") (pin "2") (pinfunction "2_2") (pintype "passive"))
      (node (ref "R98") (pin "2") (pinfunction "2_2") (pintype "passive"))
      (node (ref "R99") (pin "2") (pinfunction "2_2") (pintype "passive"))
      (node (ref "RST_CAP_1") (pin "1") (pinfunction "1_1") (pintype "passive"))
      (node (ref "R_done_led") (pin "2") (pinfunction "2_2") (pintype "passive"))
      (node (ref "S2D3") (pin "1") (pinfunction "~{OE}1_1") (pintype "input"))
      (node (ref "S2D3") (pin "10") (pinfunction "GND_10") (pintype "power_in"))
      (node (ref "S2D3") (pin "19") (pinfunction "~{OE}2_19") (pintype "input"))
      (node (ref "S2D3") (pin "9") (pinfunction "A8_9") (pintype "input"))
      (node (ref "S_D_1") (pin "1") (pinfunction "1_1") (pintype "passive"))
      (node (ref "S_D_2") (pin "1") (pinfunction "1_1") (pintype "passive"))
      (node (ref "S_D_3") (pin "1") (pinfunction "1_1") (pintype "passive"))
      (node (ref "S_D_4") (pin "1") (pinfunction "1_1") (pintype "passive"))
      (node (ref "S_ID") (pin "1") (pinfunction "1_1") (pintype "passive"))
      (node (ref "S_ID") (pin "2") (pinfunction "2_2") (pintype "passive"))
      (node (ref "S_ID") (pin "3") (pinfunction "3_3") (pintype "passive"))
      (node (ref "S_ID") (pin "4") (pinfunction "4_4") (pintype "passive"))
      (node (ref "S_SET") (pin "1") (pinfunction "1_1") (pintype "passive"))
      (node (ref "S_SET") (pin "2") (pinfunction "2_2") (pintype "passive"))
      (node (ref "S_SET") (pin "3") (pinfunction "3_3") (pintype "passive"))
      (node (ref "S_SET") (pin "4") (pinfunction "4_4") (pintype "passive"))
      (node (ref "U1") (pin "1") (pinfunction "~{OE}1_1") (pintype "input"))
      (node (ref "U1") (pin "10") (pinfunction "GND_10") (pintype "power_in"))
      (node (ref "U1") (pin "19") (pinfunction "~{OE}2_19") (pintype "input"))
      (node (ref "U1") (pin "9") (pinfunction "A8_9") (pintype "input"))
      (node (ref "U10") (pin "3") (pinfunction "GND_3") (pintype "power_in"))
      (node (ref "U11") (pin "3") (pinfunction "GND_3") (pintype "power_in"))
      (node (ref "U12") (pin "3") (pinfunction "GND_3") (pintype "power_in"))
      (node (ref "U13") (pin "3") (pinfunction "GND_3") (pintype "power_in"))
      (node (ref "U14") (pin "3") (pinfunction "GND_3") (pintype "power_in"))
      (node (ref "U15") (pin "3") (pinfunction "GND_3") (pintype "power_in"))
      (node (ref "U16") (pin "3") (pinfunction "GND_3") (pintype "power_in"))
      (node (ref "U17") (pin "3") (pinfunction "GND_3") (pintype "power_in"))
      (node (ref "U18") (pin "3") (pinfunction "GND_3") (pintype "power_in"))
      (node (ref "U19") (pin "3") (pinfunction "GND_3") (pintype "power_in"))
      (node (ref "U2") (pin "1") (pinfunction "~{OE}1_1") (pintype "input"))
      (node (ref "U2") (pin "10") (pinfunction "GND_10") (pintype "power_in"))
      (node (ref "U2") (pin "19") (pinfunction "~{OE}2_19") (pintype "input"))
      (node (ref "U2") (pin "2") (pinfunction "A1_2") (pintype "input"))
      (node (ref "U2") (pin "3") (pinfunction "A2_3") (pintype "input"))
      (node (ref "U20") (pin "3") (pinfunction "GND_3") (pintype "power_in"))
      (node (ref "U21") (pin "2") (pinfunction "Q_2") (pintype "output"))
      (node (ref "U21") (pin "4") (pinfunction "VSS_4") (pintype "power_in"))
      (node (ref "U22") (pin "3") (pinfunction "GND_3") (pintype "power_in"))
      (node (ref "U27") (pin "11") (pinfunction "GND_11") (pintype "power_in"))
      (node (ref "U3") (pin "1") (pinfunction "~{OE}1_1") (pintype "input"))
      (node (ref "U3") (pin "10") (pinfunction "GND_10") (pintype "power_in"))
      (node (ref "U3") (pin "19") (pinfunction "~{OE}2_19") (pintype "input"))
      (node (ref "U3") (pin "2") (pinfunction "A1_2") (pintype "input"))
      (node (ref "U3") (pin "7") (pinfunction "A6_7") (pintype "input"))
      (node (ref "U3") (pin "8") (pinfunction "A7_8") (pintype "input"))
      (node (ref "U3") (pin "9") (pinfunction "A8_9") (pintype "input"))
      (node (ref "U36") (pin "4") (pinfunction "VSS_4") (pintype "power_in"))
      (node (ref "U4") (pin "1") (pinfunction "~{OE}1_1") (pintype "input"))
      (node (ref "U4") (pin "10") (pinfunction "GND_10") (pintype "power_in"))
      (node (ref "U4") (pin "19") (pinfunction "~{OE}2_19") (pintype "input"))
      (node (ref "U4") (pin "4") (pinfunction "A3_4") (pintype "input"))
      (node (ref "U5") (pin "101") (pinfunction "GND_101") (pintype "power_in"))
      (node (ref "U5") (pin "114") (pinfunction "GND_114") (pintype "power_in"))
      (node (ref "U5") (pin "117") (pinfunction "GND_117") (pintype "power_in"))
      (node (ref "U5") (pin "136") (pinfunction "GND_136") (pintype "power_in"))
      (node (ref "U5") (pin "139") (pinfunction "GND_139") (pintype "power_in"))
      (node (ref "U5") (pin "16") (pinfunction "GND_16") (pintype "power_in"))
      (node (ref "U5") (pin "22") (pinfunction "GND_22") (pintype "power_in"))
      (node (ref "U5") (pin "29") (pinfunction "GND_29") (pintype "power_in"))
      (node (ref "U5") (pin "37") (pinfunction "M1_37") (pintype "input"))
      (node (ref "U5") (pin "38") (pinfunction "M0_38") (pintype "input"))
      (node (ref "U5") (pin "39") (pinfunction "M2_39") (pintype "input"))
      (node (ref "U5") (pin "42") (pinfunction "GND_42") (pintype "power_in"))
      (node (ref "U5") (pin "45") (pinfunction "GND_45") (pintype "power_in"))
      (node (ref "U5") (pin "64") (pinfunction "GND_64") (pintype "power_in"))
      (node (ref "U5") (pin "67") (pinfunction "GND_67") (pintype "power_in"))
      (node (ref "U5") (pin "81") (pinfunction "GND_81") (pintype "power_in"))
      (node (ref "U5") (pin "88") (pinfunction "GND_88") (pintype "power_in"))
      (node (ref "U5") (pin "9") (pinfunction "GND_9") (pintype "power_in"))
      (node (ref "U5") (pin "94") (pinfunction "GND_94") (pintype "power_in"))
      (node (ref "U6") (pin "3") (pinfunction "GND_3") (pintype "power_in"))
      (node (ref "U7") (pin "3") (pinfunction "GND_3") (pintype "power_in"))
      (node (ref "U8") (pin "3") (pinfunction "GND_3") (pintype "power_in"))
      (node (ref "U9") (pin "3") (pinfunction "GND_3") (pintype "power_in"))
      (node (ref "VR_1.2") (pin "1") (pinfunction "IN_1") (pintype "power_in"))
      (node (ref "VR_2.5") (pin "4") (pinfunction "GND_4") (pintype "power_in"))
      (node (ref "VR_3.3") (pin "1") (pinfunction "GND_1") (pintype "power_in"))
      (node (ref "X1") (pin "2") (pinfunction "GND_2") (pintype "power_in"))
      (node (ref "e1") (pin "4") (pinfunction "4_4") (pintype "passive"))
      (node (ref "e2") (pin "4") (pinfunction "4_4") (pintype "passive"))
      (node (ref "e3") (pin "4") (pinfunction "4_4") (pintype "passive"))
      (node (ref "e4") (pin "4") (pinfunction "4_4") (pintype "passive"))
      (node (ref "nRF") (pin "1") (pinfunction "1_1") (pintype "passive"))
      (node (ref "telecontrolli") (pin "2") (pinfunction "2_2") (pintype "passive"))
      (node (ref "telecontrolli") (pin "3") (pinfunction "3_3") (pintype "passive"))
      (node (ref "telecontrolli") (pin "4") (pinfunction "4_4") (pintype "passive"))
      (node (ref "telecontrolli") (pin "6") (pinfunction "6_6") (pintype "passive"))
    )
    (net (code "177") (name "Net-(Antenna-Pad3)") (class "Default")
      (node (ref "Antenna") (pin "3") (pinfunction "3_3") (pintype "passive"))
      (node (ref "telecontrolli") (pin "5") (pinfunction "5_5") (pintype "passive"))
    )
    (net (code "178") (name "Net-(Battery-Pad2)") (class "Default")
      (node (ref "Battery") (pin "2") (pinfunction "2_2") (pintype "passive"))
      (node (ref "P16") (pin "5") (pinfunction "5_5") (pintype "passive"))
      (node (ref "P16") (pin "6") (pinfunction "6_6") (pintype "passive"))
      (node (ref "R_D_REV") (pin "1") (pinfunction "1_1") (pintype "passive"))
    )
    (net (code "179") (name "Net-(D1-K)") (class "Default")
      (node (ref "D1") (pin "2") (pinfunction "K_2") (pintype "passive"))
      (node (ref "R1") (pin "1") (pinfunction "1_1") (pintype "passive"))
    )
    (net (code "180") (name "Net-(D3-K)") (class "Default")
      (node (ref "D3") (pin "2") (pinfunction "K_2") (pintype "passive"))
      (node (ref "R3") (pin "2") (pinfunction "2_2") (pintype "passive"))
    )
    (net (code "181") (name "Net-(D21-K)") (class "Default")
      (node (ref "D21") (pin "2") (pinfunction "K_2") (pintype "passive"))
      (node (ref "R21") (pin "2") (pinfunction "2_2") (pintype "passive"))
    )
    (net (code "182") (name "Net-(D24-K)") (class "Default")
      (node (ref "D24") (pin "2") (pinfunction "K_2") (pintype "passive"))
      (node (ref "R24") (pin "2") (pinfunction "2_2") (pintype "passive"))
    )
    (net (code "183") (name "Net-(D_D_1-K)") (class "Default")
      (node (ref "D_D_1") (pin "2") (pinfunction "K_2") (pintype "passive"))
      (node (ref "R114") (pin "1") (pinfunction "1_1") (pintype "passive"))
    )
    (net (code "184") (name "Net-(D_D_2-K)") (class "Default")
      (node (ref "D_D_2") (pin "2") (pinfunction "K_2") (pintype "passive"))
      (node (ref "R134") (pin "1") (pinfunction "1_1") (pintype "passive"))
    )
    (net (code "185") (name "Net-(D_D_3-K)") (class "Default")
      (node (ref "D_D_3") (pin "2") (pinfunction "K_2") (pintype "passive"))
      (node (ref "R154") (pin "1") (pinfunction "1_1") (pintype "passive"))
    )
    (net (code "186") (name "Net-(D_D_4-K)") (class "Default")
      (node (ref "D_D_4") (pin "2") (pinfunction "K_2") (pintype "passive"))
      (node (ref "R174") (pin "1") (pinfunction "1_1") (pintype "passive"))
    )
    (net (code "187") (name "Net-(D_Done-K)") (class "Default")
      (node (ref "D_Done") (pin "2") (pinfunction "K_2") (pintype "passive"))
      (node (ref "R_done_led") (pin "1") (pinfunction "1_1") (pintype "passive"))
    )
    (net (code "188") (name "Net-(D_REV-K)") (class "Default")
      (node (ref "D_REV") (pin "2") (pinfunction "K_2") (pintype "passive"))
      (node (ref "R_D_REV") (pin "2") (pinfunction "2_2") (pintype "passive"))
    )
    (net (code "189") (name "Net-(P2-Pad4)") (class "Default")
      (node (ref "P2") (pin "4") (pinfunction "4_4") (pintype "passive"))
      (node (ref "R44") (pin "1") (pinfunction "1_1") (pintype "passive"))
    )
    (net (code "190") (name "Net-(Q1-G)") (class "Default")
      (node (ref "Q1") (pin "4") (pinfunction "G_4") (pintype "passive"))
      (node (ref "R129") (pin "2") (pinfunction "2_2") (pintype "passive"))
      (node (ref "R47") (pin "2") (pinfunction "2_2") (pintype "passive"))
    )
    (net (code "191") (name "Net-(Q2-G)") (class "Default")
      (node (ref "Q2") (pin "4") (pinfunction "G_4") (pintype "passive"))
      (node (ref "R48") (pin "2") (pinfunction "2_2") (pintype "passive"))
    )
    (net (code "192") (name "Net-(Q3-G)") (class "Default")
      (node (ref "Q3") (pin "4") (pinfunction "G_4") (pintype "passive"))
      (node (ref "R130") (pin "2") (pinfunction "2_2") (pintype "passive"))
      (node (ref "R49") (pin "2") (pinfunction "2_2") (pintype "passive"))
    )
    (net (code "193") (name "Net-(Q4-G)") (class "Default")
      (node (ref "Q4") (pin "4") (pinfunction "G_4") (pintype "passive"))
      (node (ref "R50") (pin "2") (pinfunction "2_2") (pintype "passive"))
    )
    (net (code "194") (name "Net-(Q5-G)") (class "Default")
      (node (ref "Q5") (pin "4") (pinfunction "G_4") (pintype "passive"))
      (node (ref "R135") (pin "2") (pinfunction "2_2") (pintype "passive"))
      (node (ref "R51") (pin "2") (pinfunction "2_2") (pintype "passive"))
    )
    (net (code "195") (name "Net-(Q6-G)") (class "Default")
      (node (ref "Q6") (pin "4") (pinfunction "G_4") (pintype "passive"))
      (node (ref "R52") (pin "2") (pinfunction "2_2") (pintype "passive"))
    )
    (net (code "196") (name "Net-(Q7-G)") (class "Default")
      (node (ref "Q7") (pin "4") (pinfunction "G_4") (pintype "passive"))
      (node (ref "R136") (pin "2") (pinfunction "2_2") (pintype "passive"))
      (node (ref "R59") (pin "2") (pinfunction "2_2") (pintype "passive"))
    )
    (net (code "197") (name "Net-(Q8-G)") (class "Default")
      (node (ref "Q8") (pin "4") (pinfunction "G_4") (pintype "passive"))
      (node (ref "R137") (pin "2") (pinfunction "2_2") (pintype "passive"))
      (node (ref "R60") (pin "2") (pinfunction "2_2") (pintype "passive"))
    )
    (net (code "198") (name "Net-(Q9-G)") (class "Default")
      (node (ref "Q9") (pin "4") (pinfunction "G_4") (pintype "passive"))
      (node (ref "R61") (pin "2") (pinfunction "2_2") (pintype "passive"))
    )
    (net (code "199") (name "Net-(Q10-G)") (class "Default")
      (node (ref "Q10") (pin "4") (pinfunction "G_4") (pintype "passive"))
      (node (ref "R62") (pin "2") (pinfunction "2_2") (pintype "passive"))
    )
    (net (code "200") (name "Net-(Q11-G)") (class "Default")
      (node (ref "Q11") (pin "4") (pinfunction "G_4") (pintype "passive"))
      (node (ref "R138") (pin "2") (pinfunction "2_2") (pintype "passive"))
      (node (ref "R65") (pin "2") (pinfunction "2_2") (pintype "passive"))
    )
    (net (code "201") (name "Net-(Q12-G)") (class "Default")
      (node (ref "Q12") (pin "4") (pinfunction "G_4") (pintype "passive"))
      (node (ref "R139") (pin "2") (pinfunction "2_2") (pintype "passive"))
      (node (ref "R66") (pin "2") (pinfunction "2_2") (pintype "passive"))
    )
    (net (code "202") (name "Net-(Q13-G)") (class "Default")
      (node (ref "Q13") (pin "4") (pinfunction "G_4") (pintype "passive"))
      (node (ref "R67") (pin "2") (pinfunction "2_2") (pintype "passive"))
    )
    (net (code "203") (name "Net-(Q14-G)") (class "Default")
      (node (ref "Q14") (pin "4") (pinfunction "G_4") (pintype "passive"))
      (node (ref "R68") (pin "2") (pinfunction "2_2") (pintype "passive"))
    )
    (net (code "204") (name "Net-(Q15-G)") (class "Default")
      (node (ref "Q15") (pin "4") (pinfunction "G_4") (pintype "passive"))
      (node (ref "R140") (pin "2") (pinfunction "2_2") (pintype "passive"))
      (node (ref "R71") (pin "2") (pinfunction "2_2") (pintype "passive"))
    )
    (net (code "205") (name "Net-(Q16-G)") (class "Default")
      (node (ref "Q16") (pin "4") (pinfunction "G_4") (pintype "passive"))
      (node (ref "R141") (pin "2") (pinfunction "2_2") (pintype "passive"))
      (node (ref "R72") (pin "2") (pinfunction "2_2") (pintype "passive"))
    )
    (net (code "206") (name "Net-(Q17-G)") (class "Default")
      (node (ref "Q17") (pin "4") (pinfunction "G_4") (pintype "passive"))
      (node (ref "R73") (pin "2") (pinfunction "2_2") (pintype "passive"))
    )
    (net (code "207") (name "Net-(Q18-G)") (class "Default")
      (node (ref "Q18") (pin "4") (pinfunction "G_4") (pintype "passive"))
      (node (ref "R74") (pin "2") (pinfunction "2_2") (pintype "passive"))
    )
    (net (code "208") (name "Net-(Q19-G)") (class "Default")
      (node (ref "Q19") (pin "4") (pinfunction "G_4") (pintype "passive"))
      (node (ref "R142") (pin "2") (pinfunction "2_2") (pintype "passive"))
      (node (ref "R77") (pin "2") (pinfunction "2_2") (pintype "passive"))
    )
    (net (code "209") (name "Net-(Q20-G)") (class "Default")
      (node (ref "Q20") (pin "4") (pinfunction "G_4") (pintype "passive"))
      (node (ref "R143") (pin "2") (pinfunction "2_2") (pintype "passive"))
      (node (ref "R78") (pin "2") (pinfunction "2_2") (pintype "passive"))
    )
    (net (code "210") (name "Net-(Q21-G)") (class "Default")
      (node (ref "Q21") (pin "4") (pinfunction "G_4") (pintype "passive"))
      (node (ref "R79") (pin "2") (pinfunction "2_2") (pintype "passive"))
    )
    (net (code "211") (name "Net-(Q22-G)") (class "Default")
      (node (ref "Q22") (pin "4") (pinfunction "G_4") (pintype "passive"))
      (node (ref "R80") (pin "2") (pinfunction "2_2") (pintype "passive"))
    )
    (net (code "212") (name "Net-(Q23-G)") (class "Default")
      (node (ref "Q23") (pin "4") (pinfunction "G_4") (pintype "passive"))
      (node (ref "R144") (pin "2") (pinfunction "2_2") (pintype "passive"))
      (node (ref "R83") (pin "2") (pinfunction "2_2") (pintype "passive"))
    )
    (net (code "213") (name "Net-(Q24-G)") (class "Default")
      (node (ref "Q24") (pin "4") (pinfunction "G_4") (pintype "passive"))
      (node (ref "R145") (pin "2") (pinfunction "2_2") (pintype "passive"))
      (node (ref "R84") (pin "2") (pinfunction "2_2") (pintype "passive"))
    )
    (net (code "214") (name "Net-(Q25-G)") (class "Default")
      (node (ref "Q25") (pin "4") (pinfunction "G_4") (pintype "passive"))
      (node (ref "R85") (pin "2") (pinfunction "2_2") (pintype "passive"))
    )
    (net (code "215") (name "Net-(Q26-G)") (class "Default")
      (node (ref "Q26") (pin "4") (pinfunction "G_4") (pintype "passive"))
      (node (ref "R86") (pin "2") (pinfunction "2_2") (pintype "passive"))
    )
    (net (code "216") (name "Net-(Q27-G)") (class "Default")
      (node (ref "Q27") (pin "4") (pinfunction "G_4") (pintype "passive"))
      (node (ref "R146") (pin "2") (pinfunction "2_2") (pintype "passive"))
      (node (ref "R89") (pin "2") (pinfunction "2_2") (pintype "passive"))
    )
    (net (code "217") (name "Net-(Q28-G)") (class "Default")
      (node (ref "Q28") (pin "4") (pinfunction "G_4") (pintype "passive"))
      (node (ref "R147") (pin "2") (pinfunction "2_2") (pintype "passive"))
      (node (ref "R90") (pin "2") (pinfunction "2_2") (pintype "passive"))
    )
    (net (code "218") (name "Net-(Q29-G)") (class "Default")
      (node (ref "Q29") (pin "4") (pinfunction "G_4") (pintype "passive"))
      (node (ref "R91") (pin "2") (pinfunction "2_2") (pintype "passive"))
    )
    (net (code "219") (name "Net-(Q30-G)") (class "Default")
      (node (ref "Q30") (pin "4") (pinfunction "G_4") (pintype "passive"))
      (node (ref "R92") (pin "2") (pinfunction "2_2") (pintype "passive"))
    )
    (net (code "220") (name "Net-(Q_BUZZ-B)") (class "Default")
      (node (ref "Q_BUZZ") (pin "1") (pinfunction "B_1") (pintype "passive"))
      (node (ref "R_Buzz") (pin "2") (pinfunction "2_2") (pintype "passive"))
    )
    (net (code "221") (name "Net-(Q_BUZZ-C)") (class "Default")
      (node (ref "Buzzer") (pin "4") (pinfunction "4_4") (pintype "passive"))
      (node (ref "Q_BUZZ") (pin "3") (pinfunction "C_3") (pintype "passive"))
    )
    (net (code "222") (name "Net-(R31-Pad2)") (class "Default")
      (node (ref "R31") (pin "2") (pinfunction "2_2") (pintype "passive"))
      (node (ref "R345") (pin "2") (pinfunction "2_2") (pintype "passive"))
      (node (ref "R346") (pin "2") (pinfunction "2_2") (pintype "passive"))
    )
    (net (code "223") (name "Net-(R112-Pad1)") (class "Default")
      (node (ref "R112") (pin "1") (pinfunction "1_1") (pintype "passive"))
      (node (ref "R148") (pin "1") (pinfunction "1_1") (pintype "passive"))
      (node (ref "S_SET") (pin "8") (pinfunction "8_8") (pintype "passive"))
    )
    (net (code "224") (name "Net-(R122-Pad2)") (class "Default")
      (node (ref "R122") (pin "2") (pinfunction "2_2") (pintype "passive"))
      (node (ref "S4") (pin "1") (pinfunction "1_1") (pintype "passive"))
    )
    (net (code "225") (name "Net-(U1-A4)") (class "Default")
      (node (ref "U1") (pin "5") (pinfunction "A4_5") (pintype "input"))
      (node (ref "e3") (pin "2") (pinfunction "2_2") (pintype "passive"))
    )
    (net (code "226") (name "Net-(U1-A5)") (class "Default")
      (node (ref "U1") (pin "6") (pinfunction "A5_6") (pintype "input"))
      (node (ref "e3") (pin "3") (pinfunction "3_3") (pintype "passive"))
    )
    (net (code "227") (name "Net-(U1-A6)") (class "Default")
      (node (ref "U1") (pin "7") (pinfunction "A6_7") (pintype "input"))
      (node (ref "e2") (pin "2") (pinfunction "2_2") (pintype "passive"))
    )
    (net (code "228") (name "Net-(U1-A7)") (class "Default")
      (node (ref "U1") (pin "8") (pinfunction "A7_8") (pintype "input"))
      (node (ref "e2") (pin "3") (pinfunction "3_3") (pintype "passive"))
    )
    (net (code "229") (name "Net-(U4-A1)") (class "Default")
      (node (ref "U4") (pin "2") (pinfunction "A1_2") (pintype "input"))
      (node (ref "e1") (pin "2") (pinfunction "2_2") (pintype "passive"))
    )
    (net (code "230") (name "Net-(U4-A2)") (class "Default")
      (node (ref "U4") (pin "3") (pinfunction "A2_3") (pintype "input"))
      (node (ref "e1") (pin "3") (pinfunction "3_3") (pintype "passive"))
    )
    (net (code "231") (name "Net-(U4-A4)") (class "Default")
      (node (ref "U4") (pin "5") (pinfunction "A4_5") (pintype "input"))
      (node (ref "e4") (pin "2") (pinfunction "2_2") (pintype "passive"))
    )
    (net (code "232") (name "Net-(U4-A5)") (class "Default")
      (node (ref "U4") (pin "6") (pinfunction "A5_6") (pintype "input"))
      (node (ref "e4") (pin "3") (pinfunction "3_3") (pintype "passive"))
    )
    (net (code "233") (name "Net-(U5I-TCK)") (class "Default")
      (node (ref "R342") (pin "2") (pinfunction "2_2") (pintype "passive"))
      (node (ref "U5") (pin "110") (pinfunction "TCK_110") (pintype "input"))
    )
    (net (code "234") (name "Net-(U5I-TDI)") (class "Default")
      (node (ref "R341") (pin "2") (pinfunction "2_2") (pintype "passive"))
      (node (ref "U5") (pin "144") (pinfunction "TDI_144") (pintype "input"))
    )
    (net (code "235") (name "Net-(U5I-TMS)") (class "Default")
      (node (ref "R343") (pin "2") (pinfunction "2_2") (pintype "passive"))
      (node (ref "U5") (pin "111") (pinfunction "TMS_111") (pintype "input"))
    )
    (net (code "236") (name "Net-(U6-OUTA)") (class "Default")
      (node (ref "R59") (pin "1") (pinfunction "1_1") (pintype "passive"))
      (node (ref "U6") (pin "7") (pinfunction "OUTA_7") (pintype "output"))
    )
    (net (code "237") (name "Net-(U6-OUTB)") (class "Default")
      (node (ref "R61") (pin "1") (pinfunction "1_1") (pintype "passive"))
      (node (ref "U6") (pin "5") (pinfunction "OUTB_5") (pintype "output"))
    )
    (net (code "238") (name "Net-(U7-OUTA)") (class "Default")
      (node (ref "R47") (pin "1") (pinfunction "1_1") (pintype "passive"))
      (node (ref "U7") (pin "7") (pinfunction "OUTA_7") (pintype "output"))
    )
    (net (code "239") (name "Net-(U7-OUTB)") (class "Default")
      (node (ref "R48") (pin "1") (pinfunction "1_1") (pintype "passive"))
      (node (ref "U7") (pin "5") (pinfunction "OUTB_5") (pintype "output"))
    )
    (net (code "240") (name "Net-(U8-OUTA)") (class "Default")
      (node (ref "R49") (pin "1") (pinfunction "1_1") (pintype "passive"))
      (node (ref "U8") (pin "7") (pinfunction "OUTA_7") (pintype "output"))
    )
    (net (code "241") (name "Net-(U8-OUTB)") (class "Default")
      (node (ref "R50") (pin "1") (pinfunction "1_1") (pintype "passive"))
      (node (ref "U8") (pin "5") (pinfunction "OUTB_5") (pintype "output"))
    )
    (net (code "242") (name "Net-(U9-OUTA)") (class "Default")
      (node (ref "R60") (pin "1") (pinfunction "1_1") (pintype "passive"))
      (node (ref "U9") (pin "7") (pinfunction "OUTA_7") (pintype "output"))
    )
    (net (code "243") (name "Net-(U9-OUTB)") (class "Default")
      (node (ref "R62") (pin "1") (pinfunction "1_1") (pintype "passive"))
      (node (ref "U9") (pin "5") (pinfunction "OUTB_5") (pintype "output"))
    )
    (net (code "244") (name "Net-(U10-OUTA)") (class "Default")
      (node (ref "R51") (pin "1") (pinfunction "1_1") (pintype "passive"))
      (node (ref "U10") (pin "7") (pinfunction "OUTA_7") (pintype "output"))
    )
    (net (code "245") (name "Net-(U10-OUTB)") (class "Default")
      (node (ref "R52") (pin "1") (pinfunction "1_1") (pintype "passive"))
      (node (ref "U10") (pin "5") (pinfunction "OUTB_5") (pintype "output"))
    )
    (net (code "246") (name "Net-(U11-OUTA)") (class "Default")
      (node (ref "R66") (pin "1") (pinfunction "1_1") (pintype "passive"))
      (node (ref "U11") (pin "7") (pinfunction "OUTA_7") (pintype "output"))
    )
    (net (code "247") (name "Net-(U11-OUTB)") (class "Default")
      (node (ref "R68") (pin "1") (pinfunction "1_1") (pintype "passive"))
      (node (ref "U11") (pin "5") (pinfunction "OUTB_5") (pintype "output"))
    )
    (net (code "248") (name "Net-(U12-OUTA)") (class "Default")
      (node (ref "R77") (pin "1") (pinfunction "1_1") (pintype "passive"))
      (node (ref "U12") (pin "7") (pinfunction "OUTA_7") (pintype "output"))
    )
    (net (code "249") (name "Net-(U12-OUTB)") (class "Default")
      (node (ref "R79") (pin "1") (pinfunction "1_1") (pintype "passive"))
      (node (ref "U12") (pin "5") (pinfunction "OUTB_5") (pintype "output"))
    )
    (net (code "250") (name "Net-(U13-OUTA)") (class "Default")
      (node (ref "R72") (pin "1") (pinfunction "1_1") (pintype "passive"))
      (node (ref "U13") (pin "7") (pinfunction "OUTA_7") (pintype "output"))
    )
    (net (code "251") (name "Net-(U13-OUTB)") (class "Default")
      (node (ref "R74") (pin "1") (pinfunction "1_1") (pintype "passive"))
      (node (ref "U13") (pin "5") (pinfunction "OUTB_5") (pintype "output"))
    )
    (net (code "252") (name "Net-(U14-OUTA)") (class "Default")
      (node (ref "R83") (pin "1") (pinfunction "1_1") (pintype "passive"))
      (node (ref "U14") (pin "7") (pinfunction "OUTA_7") (pintype "output"))
    )
    (net (code "253") (name "Net-(U14-OUTB)") (class "Default")
      (node (ref "R85") (pin "1") (pinfunction "1_1") (pintype "passive"))
      (node (ref "U14") (pin "5") (pinfunction "OUTB_5") (pintype "output"))
    )
    (net (code "254") (name "Net-(U15-OUTA)") (class "Default")
      (node (ref "R78") (pin "1") (pinfunction "1_1") (pintype "passive"))
      (node (ref "U15") (pin "7") (pinfunction "OUTA_7") (pintype "output"))
    )
    (net (code "255") (name "Net-(U15-OUTB)") (class "Default")
      (node (ref "R80") (pin "1") (pinfunction "1_1") (pintype "passive"))
      (node (ref "U15") (pin "5") (pinfunction "OUTB_5") (pintype "output"))
    )
    (net (code "256") (name "Net-(U16-OUTA)") (class "Default")
      (node (ref "R65") (pin "1") (pinfunction "1_1") (pintype "passive"))
      (node (ref "U16") (pin "7") (pinfunction "OUTA_7") (pintype "output"))
    )
    (net (code "257") (name "Net-(U16-OUTB)") (class "Default")
      (node (ref "R67") (pin "1") (pinfunction "1_1") (pintype "passive"))
      (node (ref "U16") (pin "5") (pinfunction "OUTB_5") (pintype "output"))
    )
    (net (code "258") (name "Net-(U17-OUTA)") (class "Default")
      (node (ref "R84") (pin "1") (pinfunction "1_1") (pintype "passive"))
      (node (ref "U17") (pin "7") (pinfunction "OUTA_7") (pintype "output"))
    )
    (net (code "259") (name "Net-(U17-OUTB)") (class "Default")
      (node (ref "R86") (pin "1") (pinfunction "1_1") (pintype "passive"))
      (node (ref "U17") (pin "5") (pinfunction "OUTB_5") (pintype "output"))
    )
    (net (code "260") (name "Net-(U18-OUTA)") (class "Default")
      (node (ref "R71") (pin "1") (pinfunction "1_1") (pintype "passive"))
      (node (ref "U18") (pin "7") (pinfunction "OUTA_7") (pintype "output"))
    )
    (net (code "261") (name "Net-(U18-OUTB)") (class "Default")
      (node (ref "R73") (pin "1") (pinfunction "1_1") (pintype "passive"))
      (node (ref "U18") (pin "5") (pinfunction "OUTB_5") (pintype "output"))
    )
    (net (code "262") (name "Net-(U19-OUTA)") (class "Default")
      (node (ref "R90") (pin "1") (pinfunction "1_1") (pintype "passive"))
      (node (ref "U19") (pin "7") (pinfunction "OUTA_7") (pintype "output"))
    )
    (net (code "263") (name "Net-(U19-OUTB)") (class "Default")
      (node (ref "R92") (pin "1") (pinfunction "1_1") (pintype "passive"))
      (node (ref "U19") (pin "5") (pinfunction "OUTB_5") (pintype "output"))
    )
    (net (code "264") (name "Net-(U20-OUTA)") (class "Default")
      (node (ref "R89") (pin "1") (pinfunction "1_1") (pintype "passive"))
      (node (ref "U20") (pin "7") (pinfunction "OUTA_7") (pintype "output"))
    )
    (net (code "265") (name "Net-(U20-OUTB)") (class "Default")
      (node (ref "R91") (pin "1") (pinfunction "1_1") (pintype "passive"))
      (node (ref "U20") (pin "5") (pinfunction "OUTB_5") (pintype "output"))
    )
    (net (code "266") (name "Net-(U21-D)") (class "Default")
      (node (ref "C_ADC") (pin "2") (pinfunction "2_2") (pintype "passive"))
      (node (ref "R46") (pin "1") (pinfunction "1_1") (pintype "passive"))
      (node (ref "U21") (pin "5") (pinfunction "D_5") (pintype "input"))
    )
    (net (code "267") (name "Net-(U21-~{S})") (class "Default")
      (node (ref "R43") (pin "1") (pinfunction "1_1") (pintype "passive"))
      (node (ref "R45") (pin "2") (pinfunction "2_2") (pintype "passive"))
      (node (ref "U21") (pin "1") (pinfunction "~{S}_1") (pintype "input"))
    )
    (net (code "268") (name "Net-(U21-~{W})") (class "Default")
      (node (ref "R46") (pin "2") (pinfunction "2_2") (pintype "passive"))
      (node (ref "U21") (pin "3") (pinfunction "~{W}_3") (pintype "input"))
    )
    (net (code "269") (name "Net-(U22-INA)") (class "Default")
      (node (ref "R333") (pin "1") (pinfunction "1_1") (pintype "passive"))
      (node (ref "U22") (pin "2") (pinfunction "INA_2") (pintype "input"))
    )
    (net (code "270") (name "Net-(U22-INB)") (class "Default")
      (node (ref "R22") (pin "1") (pinfunction "1_1") (pintype "passive"))
      (node (ref "U22") (pin "4") (pinfunction "INB_4") (pintype "input"))
    )
    (net (code "271") (name "Net-(U22-OUTA)") (class "Default")
      (node (ref "P2") (pin "3") (pinfunction "3_3") (pintype "passive"))
      (node (ref "U22") (pin "7") (pinfunction "OUTA_7") (pintype "output"))
    )
    (net (code "272") (name "V 1.2") (class "Default")
      (node (ref "C33") (pin "2") (pinfunction "2_2") (pintype "passive"))
      (node (ref "C34") (pin "2") (pinfunction "2_2") (pintype "passive"))
      (node (ref "C35") (pin "2") (pinfunction "2_2") (pintype "passive"))
      (node (ref "C36") (pin "2") (pinfunction "2_2") (pintype "passive"))
      (node (ref "C62") (pin "2") (pinfunction "2_2") (pintype "passive"))
      (node (ref "C75") (pin "2") (pinfunction "2_2") (pintype "passive"))
      (node (ref "U5") (pin "121") (pinfunction "VCCINT_121") (pintype "power_in"))
      (node (ref "U5") (pin "133") (pinfunction "VCCINT_133") (pintype "power_in"))
      (node (ref "U5") (pin "49") (pinfunction "VCCINT_49") (pintype "power_in"))
      (node (ref "U5") (pin "61") (pinfunction "VCCINT_61") (pintype "power_in"))
      (node (ref "VR_1.2") (pin "4") (pinfunction "GND_4") (pintype "power_in"))
    )
    (net (code "273") (name "V 2.5") (class "Default")
      (node (ref "C11") (pin "2") (pinfunction "2_2") (pintype "passive"))
      (node (ref "C12") (pin "2") (pinfunction "2_2") (pintype "passive"))
      (node (ref "C13") (pin "2") (pinfunction "2_2") (pintype "passive"))
      (node (ref "C31") (pin "2") (pinfunction "2_2") (pintype "passive"))
      (node (ref "C73") (pin "2") (pinfunction "2_2") (pintype "passive"))
      (node (ref "C74") (pin "2") (pinfunction "2_2") (pintype "passive"))
      (node (ref "D21") (pin "1") (pinfunction "A_1") (pintype "passive"))
      (node (ref "R2.5") (pin "2") (pinfunction "2_2") (pintype "passive"))
      (node (ref "R33") (pin "2") (pinfunction "2_2") (pintype "passive"))
      (node (ref "R34") (pin "1") (pinfunction "1_1") (pintype "passive"))
      (node (ref "U5") (pin "120") (pinfunction "VCCAUX_120") (pintype "power_in"))
      (node (ref "U5") (pin "134") (pinfunction "VCCAUX_134") (pintype "power_in"))
      (node (ref "U5") (pin "48") (pinfunction "VCCAUX_48") (pintype "power_in"))
      (node (ref "U5") (pin "62") (pinfunction "VCCAUX_62") (pintype "power_in"))
      (node (ref "VR_2.5") (pin "3") (pinfunction "OUT_3") (pintype "power_in"))
    )
    (net (code "274") (name "V 3.3") (class "Default")
      (node (ref "Booster") (pin "5") (pinfunction "5_5") (pintype "passive"))
      (node (ref "C(tele)") (pin "1") (pinfunction "1_1") (pintype "passive"))
      (node (ref "C10") (pin "1") (pinfunction "1_1") (pintype "passive"))
      (node (ref "C14") (pin "2") (pinfunction "2_2") (pintype "passive"))
      (node (ref "C15") (pin "2") (pinfunction "2_2") (pintype "passive"))
      (node (ref "C16") (pin "2") (pinfunction "2_2") (pintype "passive"))
      (node (ref "C17") (pin "2") (pinfunction "2_2") (pintype "passive"))
      (node (ref "C18") (pin "2") (pinfunction "2_2") (pintype "passive"))
      (node (ref "C2(tele)") (pin "1") (pinfunction "1_1") (pintype "passive"))
      (node (ref "C20") (pin "1") (pinfunction "1_1") (pintype "passive"))
      (node (ref "C21") (pin "1") (pinfunction "1_1") (pintype "passive"))
      (node (ref "C23") (pin "2") (pinfunction "2_2") (pintype "passive"))
      (node (ref "C24") (pin "2") (pinfunction "2_2") (pintype "passive"))
      (node (ref "C25") (pin "2") (pinfunction "2_2") (pintype "passive"))
      (node (ref "C37") (pin "2") (pinfunction "2_2") (pintype "passive"))
      (node (ref "C38") (pin "2") (pinfunction "2_2") (pintype "passive"))
      (node (ref "C39") (pin "2") (pinfunction "2_2") (pintype "passive"))
      (node (ref "C72") (pin "1") (pinfunction "1_1") (pintype "passive"))
      (node (ref "C76") (pin "2") (pinfunction "2_2") (pintype "passive"))
      (node (ref "C77") (pin "2") (pinfunction "2_2") (pintype "passive"))
      (node (ref "C78") (pin "2") (pinfunction "2_2") (pintype "passive"))
      (node (ref "C79") (pin "2") (pinfunction "2_2") (pintype "passive"))
      (node (ref "C8") (pin "1") (pinfunction "1_1") (pintype "passive"))
      (node (ref "C80") (pin "1") (pinfunction "1_1") (pintype "passive"))
      (node (ref "CnRF") (pin "2") (pinfunction "2_2") (pintype "passive"))
      (node (ref "D3") (pin "1") (pinfunction "A_1") (pintype "passive"))
      (node (ref "Gyro & Accel") (pin "1") (pinfunction "1_1") (pintype "passive"))
      (node (ref "Gyro & Accel") (pin "14") (pinfunction "14_14") (pintype "passive"))
      (node (ref "Gyro & Accel") (pin "15") (pinfunction "15_15") (pintype "passive"))
      (node (ref "Gyro & Accel") (pin "16") (pinfunction "16_16") (pintype "passive"))
      (node (ref "Gyro & Accel") (pin "9") (pinfunction "9_9") (pintype "passive"))
      (node (ref "P13") (pin "1") (pinfunction "1_1") (pintype "passive"))
      (node (ref "R(rst)") (pin "1") (pinfunction "1_1") (pintype "passive"))
      (node (ref "R109") (pin "1") (pinfunction "1_1") (pintype "passive"))
      (node (ref "R110") (pin "1") (pinfunction "1_1") (pintype "passive"))
      (node (ref "R111") (pin "2") (pinfunction "2_2") (pintype "passive"))
      (node (ref "R112") (pin "2") (pinfunction "2_2") (pintype "passive"))
      (node (ref "R113") (pin "2") (pinfunction "2_2") (pintype "passive"))
      (node (ref "R115") (pin "2") (pinfunction "2_2") (pintype "passive"))
      (node (ref "R116") (pin "1") (pinfunction "1_1") (pintype "passive"))
      (node (ref "R117") (pin "1") (pinfunction "1_1") (pintype "passive"))
      (node (ref "R118") (pin "1") (pinfunction "1_1") (pintype "passive"))
      (node (ref "R119") (pin "1") (pinfunction "1_1") (pintype "passive"))
      (node (ref "R127") (pin "1") (pinfunction "1_1") (pintype "passive"))
      (node (ref "R128") (pin "1") (pinfunction "1_1") (pintype "passive"))
      (node (ref "R131") (pin "2") (pinfunction "2_2") (pintype "passive"))
      (node (ref "R132") (pin "2") (pinfunction "2_2") (pintype "passive"))
      (node (ref "R133") (pin "2") (pinfunction "2_2") (pintype "passive"))
      (node (ref "R149") (pin "1") (pinfunction "1_1") (pintype "passive"))
      (node (ref "R150") (pin "1") (pinfunction "1_1") (pintype "passive"))
      (node (ref "R151") (pin "2") (pinfunction "2_2") (pintype "passive"))
      (node (ref "R152") (pin "2") (pinfunction "2_2") (pintype "passive"))
      (node (ref "R153") (pin "2") (pinfunction "2_2") (pintype "passive"))
      (node (ref "R158") (pin "1") (pinfunction "1_1") (pintype "passive"))
      (node (ref "R171") (pin "2") (pinfunction "2_2") (pintype "passive"))
      (node (ref "R172") (pin "2") (pinfunction "2_2") (pintype "passive"))
      (node (ref "R173") (pin "2") (pinfunction "2_2") (pintype "passive"))
      (node (ref "R32") (pin "1") (pinfunction "1_1") (pintype "passive"))
      (node (ref "R345") (pin "1") (pinfunction "1_1") (pintype "passive"))
      (node (ref "R55") (pin "2") (pinfunction "2_2") (pintype "passive"))
      (node (ref "U1") (pin "20") (pinfunction "VCC_20") (pintype "power_in"))
      (node (ref "U2") (pin "20") (pinfunction "VCC_20") (pintype "power_in"))
      (node (ref "U21") (pin "8") (pinfunction "VCC_8") (pintype "power_in"))
      (node (ref "U27") (pin "18") (pinfunction "VCCINT_18") (pintype "power_in"))
      (node (ref "U27") (pin "19") (pinfunction "VCCO_19") (pintype "power_in"))
      (node (ref "U27") (pin "20") (pinfunction "VCCJ_20") (pintype "power_in"))
      (node (ref "U3") (pin "20") (pinfunction "VCC_20") (pintype "power_in"))
      (node (ref "U36") (pin "3") (pinfunction "~{W}_3") (pintype "input"))
      (node (ref "U36") (pin "7") (pinfunction "HOL~{D}_7") (pintype "input"))
      (node (ref "U36") (pin "8") (pinfunction "VCC_8") (pintype "power_in"))
      (node (ref "U4") (pin "20") (pinfunction "VCC_20") (pintype "power_in"))
      (node (ref "U5") (pin "106") (pinfunction "VCCO_RIGHT_106") (pintype "power_in"))
      (node (ref "U5") (pin "115") (pinfunction "VCCO_TOP_115") (pintype "power_in"))
      (node (ref "U5") (pin "126") (pinfunction "VCCO_TOP_126") (pintype "power_in"))
      (node (ref "U5") (pin "138") (pinfunction "VCCO_TOP_138") (pintype "power_in"))
      (node (ref "U5") (pin "19") (pinfunction "VCCO_LEFT_19") (pintype "power_in"))
      (node (ref "U5") (pin "3") (pinfunction "VCCO_LEFT_3") (pintype "power_in"))
      (node (ref "U5") (pin "34") (pinfunction "VCCO_LEFT_34") (pintype "power_in"))
      (node (ref "U5") (pin "43") (pinfunction "VCCO_BOTTOM_43") (pintype "power_in"))
      (node (ref "U5") (pin "54") (pinfunction "VCCO_BOTTOM_54") (pintype "power_in"))
      (node (ref "U5") (pin "66") (pinfunction "VCCO_BOTTOM_66") (pintype "power_in"))
      (node (ref "U5") (pin "75") (pinfunction "VCCO_RIGHT_75") (pintype "power_in"))
      (node (ref "U5") (pin "91") (pinfunction "VCCO_RIGHT_91") (pintype "power_in"))
      (node (ref "VR_3.3") (pin "4") (pinfunction "OUT_4") (pintype "power_in"))
      (node (ref "X1") (pin "4") (pinfunction "VDD_4") (pintype "power_in"))
      (node (ref "nRF") (pin "8") (pinfunction "8_8") (pintype "passive"))
      (node (ref "telecontrolli") (pin "1") (pinfunction "1_1") (pintype "passive"))
      (node (ref "telecontrolli") (pin "11") (pinfunction "14_11") (pintype "passive"))
      (node (ref "telecontrolli") (pin "12") (pinfunction "13_12") (pintype "passive"))
      (node (ref "telecontrolli") (pin "13") (pinfunction "12_13") (pintype "passive"))
      (node (ref "telecontrolli") (pin "16") (pinfunction "9_16") (pintype "passive"))
    )
    (net (code "275") (name "V 12") (class "Default")
      (node (ref "C19") (pin "2") (pinfunction "2_2") (pintype "passive"))
      (node (ref "C22") (pin "2") (pinfunction "2_2") (pintype "passive"))
      (node (ref "C26") (pin "2") (pinfunction "2_2") (pintype "passive"))
      (node (ref "C27") (pin "2") (pinfunction "2_2") (pintype "passive"))
      (node (ref "C28") (pin "2") (pinfunction "2_2") (pintype "passive"))
      (node (ref "C29") (pin "2") (pinfunction "2_2") (pintype "passive"))
      (node (ref "C30") (pin "2") (pinfunction "2_2") (pintype "passive"))
      (node (ref "C32") (pin "2") (pinfunction "2_2") (pintype "passive"))
      (node (ref "C4") (pin "2") (pinfunction "2_2") (pintype "passive"))
      (node (ref "C40") (pin "2") (pinfunction "2_2") (pintype "passive"))
      (node (ref "C41") (pin "2") (pinfunction "2_2") (pintype "passive"))
      (node (ref "C42") (pin "2") (pinfunction "2_2") (pintype "passive"))
      (node (ref "C43") (pin "2") (pinfunction "2_2") (pintype "passive"))
      (node (ref "C44") (pin "2") (pinfunction "2_2") (pintype "passive"))
      (node (ref "C45") (pin "2") (pinfunction "2_2") (pintype "passive"))
      (node (ref "C46") (pin "2") (pinfunction "2_2") (pintype "passive"))
      (node (ref "C47") (pin "2") (pinfunction "2_2") (pintype "passive"))
      (node (ref "C48") (pin "2") (pinfunction "2_2") (pintype "passive"))
      (node (ref "C49") (pin "2") (pinfunction "2_2") (pintype "passive"))
      (node (ref "C50") (pin "2") (pinfunction "2_2") (pintype "passive"))
      (node (ref "C51") (pin "2") (pinfunction "2_2") (pintype "passive"))
      (node (ref "C52") (pin "2") (pinfunction "2_2") (pintype "passive"))
      (node (ref "C53") (pin "2") (pinfunction "2_2") (pintype "passive"))
      (node (ref "C54") (pin "2") (pinfunction "2_2") (pintype "passive"))
      (node (ref "C55") (pin "2") (pinfunction "2_2") (pintype "passive"))
      (node (ref "C56") (pin "2") (pinfunction "2_2") (pintype "passive"))
      (node (ref "C57") (pin "2") (pinfunction "2_2") (pintype "passive"))
      (node (ref "C58") (pin "2") (pinfunction "2_2") (pintype "passive"))
      (node (ref "C59") (pin "2") (pinfunction "2_2") (pintype "passive"))
      (node (ref "C60") (pin "2") (pinfunction "2_2") (pintype "passive"))
      (node (ref "C61") (pin "2") (pinfunction "2_2") (pintype "passive"))
      (node (ref "C66") (pin "1") (pinfunction "1_1") (pintype "passive"))
      (node (ref "C67") (pin "1") (pinfunction "1_1") (pintype "passive"))
      (node (ref "C68") (pin "1") (pinfunction "1_1") (pintype "passive"))
      (node (ref "C69") (pin "1") (pinfunction "1_1") (pintype "passive"))
      (node (ref "C70") (pin "1") (pinfunction "1_1") (pintype "passive"))
      (node (ref "C71") (pin "1") (pinfunction "1_1") (pintype "passive"))
      (node (ref "C81") (pin "1") (pinfunction "1_1") (pintype "passive"))
      (node (ref "C_DRIBBLER") (pin "2") (pinfunction "2_2") (pintype "passive"))
      (node (ref "C_IR") (pin "1") (pinfunction "1_1") (pintype "passive"))
      (node (ref "C_M1") (pin "2") (pinfunction "2_2") (pintype "passive"))
      (node (ref "C_M2") (pin "2") (pinfunction "2_2") (pintype "passive"))
      (node (ref "C_M3") (pin "2") (pinfunction "2_2") (pintype "passive"))
      (node (ref "C_M4") (pin "2") (pinfunction "2_2") (pintype "passive"))
      (node (ref "C_MIKONA") (pin "2") (pinfunction "2_2") (pintype "passive"))
      (node (ref "D1") (pin "1") (pinfunction "A_1") (pintype "passive"))
      (node (ref "D_correction") (pin "2") (pinfunction "K_2") (pintype "passive"))
      (node (ref "MinMax") (pin "3") (pinfunction "3_3") (pintype "passive"))
      (node (ref "MinMax") (pin "5") (pinfunction "5_5") (pintype "passive"))
      (node (ref "P16") (pin "1") (pinfunction "1_1") (pintype "passive"))
      (node (ref "P16") (pin "2") (pinfunction "2_2") (pintype "passive"))
      (node (ref "P16") (pin "3") (pinfunction "3_3") (pintype "passive"))
      (node (ref "P16") (pin "4") (pinfunction "4_4") (pintype "passive"))
      (node (ref "Q1") (pin "1") (pinfunction "S_1") (pintype "passive"))
      (node (ref "Q1") (pin "2") (pinfunction "S_2") (pintype "passive"))
      (node (ref "Q1") (pin "3") (pinfunction "S_3") (pintype "passive"))
      (node (ref "Q11") (pin "1") (pinfunction "S_1") (pintype "passive"))
      (node (ref "Q11") (pin "2") (pinfunction "S_2") (pintype "passive"))
      (node (ref "Q11") (pin "3") (pinfunction "S_3") (pintype "passive"))
      (node (ref "Q12") (pin "1") (pinfunction "S_1") (pintype "passive"))
      (node (ref "Q12") (pin "2") (pinfunction "S_2") (pintype "passive"))
      (node (ref "Q12") (pin "3") (pinfunction "S_3") (pintype "passive"))
      (node (ref "Q15") (pin "1") (pinfunction "S_1") (pintype "passive"))
      (node (ref "Q15") (pin "2") (pinfunction "S_2") (pintype "passive"))
      (node (ref "Q15") (pin "3") (pinfunction "S_3") (pintype "passive"))
      (node (ref "Q16") (pin "1") (pinfunction "S_1") (pintype "passive"))
      (node (ref "Q16") (pin "2") (pinfunction "S_2") (pintype "passive"))
      (node (ref "Q16") (pin "3") (pinfunction "S_3") (pintype "passive"))
      (node (ref "Q19") (pin "1") (pinfunction "S_1") (pintype "passive"))
      (node (ref "Q19") (pin "2") (pinfunction "S_2") (pintype "passive"))
      (node (ref "Q19") (pin "3") (pinfunction "S_3") (pintype "passive"))
      (node (ref "Q20") (pin "1") (pinfunction "S_1") (pintype "passive"))
      (node (ref "Q20") (pin "2") (pinfunction "S_2") (pintype "passive"))
      (node (ref "Q20") (pin "3") (pinfunction "S_3") (pintype "passive"))
      (node (ref "Q23") (pin "1") (pinfunction "S_1") (pintype "passive"))
      (node (ref "Q23") (pin "2") (pinfunction "S_2") (pintype "passive"))
      (node (ref "Q23") (pin "3") (pinfunction "S_3") (pintype "passive"))
      (node (ref "Q24") (pin "1") (pinfunction "S_1") (pintype "passive"))
      (node (ref "Q24") (pin "2") (pinfunction "S_2") (pintype "passive"))
      (node (ref "Q24") (pin "3") (pinfunction "S_3") (pintype "passive"))
      (node (ref "Q27") (pin "1") (pinfunction "S_1") (pintype "passive"))
      (node (ref "Q27") (pin "2") (pinfunction "S_2") (pintype "passive"))
      (node (ref "Q27") (pin "3") (pinfunction "S_3") (pintype "passive"))
      (node (ref "Q28") (pin "1") (pinfunction "S_1") (pintype "passive"))
      (node (ref "Q28") (pin "2") (pinfunction "S_2") (pintype "passive"))
      (node (ref "Q28") (pin "3") (pinfunction "S_3") (pintype "passive"))
      (node (ref "Q3") (pin "1") (pinfunction "S_1") (pintype "passive"))
      (node (ref "Q3") (pin "2") (pinfunction "S_2") (pintype "passive"))
      (node (ref "Q3") (pin "3") (pinfunction "S_3") (pintype "passive"))
      (node (ref "Q5") (pin "1") (pinfunction "S_1") (pintype "passive"))
      (node (ref "Q5") (pin "2") (pinfunction "S_2") (pintype "passive"))
      (node (ref "Q5") (pin "3") (pinfunction "S_3") (pintype "passive"))
      (node (ref "Q7") (pin "1") (pinfunction "S_1") (pintype "passive"))
      (node (ref "Q7") (pin "2") (pinfunction "S_2") (pintype "passive"))
      (node (ref "Q7") (pin "3") (pinfunction "S_3") (pintype "passive"))
      (node (ref "Q8") (pin "1") (pinfunction "S_1") (pintype "passive"))
      (node (ref "Q8") (pin "2") (pinfunction "S_2") (pintype "passive"))
      (node (ref "Q8") (pin "3") (pinfunction "S_3") (pintype "passive"))
      (node (ref "R129") (pin "1") (pinfunction "1_1") (pintype "passive"))
      (node (ref "R130") (pin "1") (pinfunction "1_1") (pintype "passive"))
      (node (ref "R135") (pin "1") (pinfunction "1_1") (pintype "passive"))
      (node (ref "R136") (pin "1") (pinfunction "1_1") (pintype "passive"))
      (node (ref "R137") (pin "1") (pinfunction "1_1") (pintype "passive"))
      (node (ref "R138") (pin "1") (pinfunction "1_1") (pintype "passive"))
      (node (ref "R139") (pin "1") (pinfunction "1_1") (pintype "passive"))
      (node (ref "R140") (pin "1") (pinfunction "1_1") (pintype "passive"))
      (node (ref "R141") (pin "1") (pinfunction "1_1") (pintype "passive"))
      (node (ref "R142") (pin "1") (pinfunction "1_1") (pintype "passive"))
      (node (ref "R143") (pin "1") (pinfunction "1_1") (pintype "passive"))
      (node (ref "R144") (pin "1") (pinfunction "1_1") (pintype "passive"))
      (node (ref "R145") (pin "1") (pinfunction "1_1") (pintype "passive"))
      (node (ref "R146") (pin "1") (pinfunction "1_1") (pintype "passive"))
      (node (ref "R147") (pin "1") (pinfunction "1_1") (pintype "passive"))
      (node (ref "R43") (pin "2") (pinfunction "2_2") (pintype "passive"))
      (node (ref "R44") (pin "2") (pinfunction "2_2") (pintype "passive"))
      (node (ref "U10") (pin "6") (pinfunction "VDD_6") (pintype "power_in"))
      (node (ref "U11") (pin "6") (pinfunction "VDD_6") (pintype "power_in"))
      (node (ref "U12") (pin "6") (pinfunction "VDD_6") (pintype "power_in"))
      (node (ref "U13") (pin "6") (pinfunction "VDD_6") (pintype "power_in"))
      (node (ref "U14") (pin "6") (pinfunction "VDD_6") (pintype "power_in"))
      (node (ref "U15") (pin "6") (pinfunction "VDD_6") (pintype "power_in"))
      (node (ref "U16") (pin "6") (pinfunction "VDD_6") (pintype "power_in"))
      (node (ref "U17") (pin "6") (pinfunction "VDD_6") (pintype "power_in"))
      (node (ref "U18") (pin "6") (pinfunction "VDD_6") (pintype "power_in"))
      (node (ref "U19") (pin "6") (pinfunction "VDD_6") (pintype "power_in"))
      (node (ref "U20") (pin "6") (pinfunction "VDD_6") (pintype "power_in"))
      (node (ref "U22") (pin "6") (pinfunction "VDD_6") (pintype "power_in"))
      (node (ref "U6") (pin "6") (pinfunction "VDD_6") (pintype "power_in"))
      (node (ref "U7") (pin "6") (pinfunction "VDD_6") (pintype "power_in"))
      (node (ref "U8") (pin "6") (pinfunction "VDD_6") (pintype "power_in"))
      (node (ref "U9") (pin "6") (pinfunction "VDD_6") (pintype "power_in"))
    )
    (net (code "276") (name "VCC") (class "Default")
      (node (ref "Buzzer") (pin "1") (pinfunction "1_1") (pintype "passive"))
      (node (ref "C1") (pin "1") (pinfunction "1_1") (pintype "passive"))
      (node (ref "C110") (pin "1") (pinfunction "1_1") (pintype "passive"))
      (node (ref "C120") (pin "1") (pinfunction "1_1") (pintype "passive"))
      (node (ref "C130") (pin "1") (pinfunction "1_1") (pintype "passive"))
      (node (ref "C2") (pin "1") (pinfunction "1_1") (pintype "passive"))
      (node (ref "C3") (pin "1") (pinfunction "1_1") (pintype "passive"))
      (node (ref "C5") (pin "1") (pinfunction "1_1") (pintype "passive"))
      (node (ref "C6") (pin "1") (pinfunction "1_1") (pintype "passive"))
      (node (ref "C63") (pin "1") (pinfunction "1_1") (pintype "passive"))
      (node (ref "C65") (pin "1") (pinfunction "1_1") (pintype "passive"))
      (node (ref "C7") (pin "1") (pinfunction "1_1") (pintype "passive"))
      (node (ref "C9") (pin "1") (pinfunction "1_1") (pintype "passive"))
      (node (ref "C_1") (pin "1") (pinfunction "1_1") (pintype "passive"))
      (node (ref "C_16") (pin "1") (pinfunction "1_1") (pintype "passive"))
      (node (ref "C_17") (pin "1") (pinfunction "1_1") (pintype "passive"))
      (node (ref "C_19") (pin "1") (pinfunction "1_1") (pintype "passive"))
      (node (ref "D24") (pin "1") (pinfunction "A_1") (pintype "passive"))
      (node (ref "Dribbler") (pin "4") (pinfunction "4_4") (pintype "passive"))
      (node (ref "MOTOR_1") (pin "4") (pinfunction "4_4") (pintype "passive"))
      (node (ref "MOTOR_2") (pin "4") (pinfunction "4_4") (pintype "passive"))
      (node (ref "MOTOR_3") (pin "4") (pinfunction "4_4") (pintype "passive"))
      (node (ref "MOTOR_4") (pin "4") (pinfunction "4_4") (pintype "passive"))
      (node (ref "MinMax") (pin "21") (pinfunction "21_21") (pintype "passive"))
      (node (ref "P1") (pin "2") (pinfunction "2_2") (pintype "passive"))
      (node (ref "R40") (pin "1") (pinfunction "1_1") (pintype "passive"))
      (node (ref "R41") (pin "1") (pinfunction "1_1") (pintype "passive"))
      (node (ref "R42") (pin "1") (pinfunction "1_1") (pintype "passive"))
      (node (ref "S2D3") (pin "20") (pinfunction "VCC_20") (pintype "power_in"))
      (node (ref "VR_1.2") (pin "3") (pinfunction "OUT_3") (pintype "power_in"))
      (node (ref "VR_2.5") (pin "1") (pinfunction "IN_1") (pintype "power_in"))
      (node (ref "VR_3.3") (pin "3") (pinfunction "IN_3") (pintype "power_in"))
      (node (ref "e1") (pin "1") (pinfunction "1_1") (pintype "passive"))
      (node (ref "e2") (pin "1") (pinfunction "1_1") (pintype "passive"))
      (node (ref "e3") (pin "1") (pinfunction "1_1") (pintype "passive"))
      (node (ref "e4") (pin "1") (pinfunction "1_1") (pintype "passive"))
    )
    (net (code "277") (name "unconnected-(Buzzer-Pad2)") (class "Default")
      (node (ref "Buzzer") (pin "2") (pinfunction "2_2") (pintype "passive"))
    )
    (net (code "278") (name "unconnected-(Buzzer-Pad3)") (class "Default")
      (node (ref "Buzzer") (pin "3") (pinfunction "3_3") (pintype "passive"))
    )
    (net (code "279") (name "unconnected-(Gyro & Accel-Pad2)") (class "Default")
      (node (ref "Gyro & Accel") (pin "2") (pinfunction "2_2") (pintype "passive"))
    )
    (net (code "280") (name "unconnected-(MinMax-Pad1)") (class "Default")
      (node (ref "MinMax") (pin "1") (pinfunction "1_1") (pintype "passive"))
    )
    (net (code "281") (name "unconnected-(MinMax-Pad2)") (class "Default")
      (node (ref "MinMax") (pin "2") (pinfunction "2_2") (pintype "passive"))
    )
    (net (code "282") (name "unconnected-(MinMax-Pad7)") (class "Default")
      (node (ref "MinMax") (pin "7") (pinfunction "7_7") (pintype "passive"))
    )
    (net (code "283") (name "unconnected-(MinMax-Pad8)") (class "Default")
      (node (ref "MinMax") (pin "8") (pinfunction "8_8") (pintype "passive"))
    )
    (net (code "284") (name "unconnected-(MinMax-Pad9)") (class "Default")
      (node (ref "MinMax") (pin "9") (pinfunction "9_9") (pintype "passive"))
    )
    (net (code "285") (name "unconnected-(MinMax-Pad10)") (class "Default")
      (node (ref "MinMax") (pin "10") (pinfunction "10_10") (pintype "passive"))
    )
    (net (code "286") (name "unconnected-(MinMax-Pad11)") (class "Default")
      (node (ref "MinMax") (pin "11") (pinfunction "11_11") (pintype "passive"))
    )
    (net (code "287") (name "unconnected-(MinMax-Pad12)") (class "Default")
      (node (ref "MinMax") (pin "12") (pinfunction "12_12") (pintype "passive"))
    )
    (net (code "288") (name "unconnected-(MinMax-Pad13)") (class "Default")
      (node (ref "MinMax") (pin "13") (pinfunction "13_13") (pintype "passive"))
    )
    (net (code "289") (name "unconnected-(MinMax-Pad14)") (class "Default")
      (node (ref "MinMax") (pin "14") (pinfunction "14_14") (pintype "passive"))
    )
    (net (code "290") (name "unconnected-(MinMax-Pad15)") (class "Default")
      (node (ref "MinMax") (pin "15") (pinfunction "15_15") (pintype "passive"))
    )
    (net (code "291") (name "unconnected-(MinMax-Pad16)") (class "Default")
      (node (ref "MinMax") (pin "16") (pinfunction "16_16") (pintype "passive"))
    )
    (net (code "292") (name "unconnected-(MinMax-Pad18)") (class "Default")
      (node (ref "MinMax") (pin "18") (pinfunction "18_18") (pintype "passive"))
    )
    (net (code "293") (name "unconnected-(MinMax-Pad19)") (class "Default")
      (node (ref "MinMax") (pin "19") (pinfunction "19_19") (pintype "passive"))
    )
    (net (code "294") (name "unconnected-(MinMax-Pad20)") (class "Default")
      (node (ref "MinMax") (pin "20") (pinfunction "20_20") (pintype "passive"))
    )
    (net (code "295") (name "unconnected-(MinMax-Pad22)") (class "Default")
      (node (ref "MinMax") (pin "22") (pinfunction "22_22") (pintype "passive"))
    )
    (net (code "296") (name "unconnected-(MinMax-Pad23)") (class "Default")
      (node (ref "MinMax") (pin "23") (pinfunction "23_23") (pintype "passive"))
    )
    (net (code "297") (name "unconnected-(MinMax-Pad24)") (class "Default")
      (node (ref "MinMax") (pin "24") (pinfunction "24_24") (pintype "passive"))
    )
    (net (code "298") (name "unconnected-(S2D3-Y8-Pad11)") (class "Default")
      (node (ref "S2D3") (pin "11") (pinfunction "Y8_11") (pintype "tri_state"))
    )
    (net (code "299") (name "unconnected-(U1-Y8-Pad11)") (class "Default")
      (node (ref "U1") (pin "11") (pinfunction "Y8_11") (pintype "tri_state"))
    )
    (net (code "300") (name "unconnected-(U2-Y1-Pad18)") (class "Default")
      (node (ref "U2") (pin "18") (pinfunction "Y1_18") (pintype "tri_state"))
    )
    (net (code "301") (name "unconnected-(U3-Y1-Pad18)") (class "Default")
      (node (ref "U3") (pin "18") (pinfunction "Y1_18") (pintype "tri_state"))
    )
    (net (code "302") (name "unconnected-(U3-Y6-Pad13)") (class "Default")
      (node (ref "U3") (pin "13") (pinfunction "Y6_13") (pintype "tri_state"))
    )
    (net (code "303") (name "unconnected-(U3-Y7-Pad12)") (class "Default")
      (node (ref "U3") (pin "12") (pinfunction "Y7_12") (pintype "tri_state"))
    )
    (net (code "304") (name "unconnected-(U3-Y8-Pad11)") (class "Default")
      (node (ref "U3") (pin "11") (pinfunction "Y8_11") (pintype "tri_state"))
    )
    (net (code "305") (name "unconnected-(U4-Y3-Pad16)") (class "Default")
      (node (ref "U4") (pin "16") (pinfunction "Y3_16") (pintype "tri_state"))
    )
    (net (code "306") (name "unconnected-(U5I-HSWAP_EN-Pad142)") (class "Default")
      (node (ref "U5") (pin "142") (pinfunction "HSWAP_EN_142") (pintype "input"))
    )
    (net (code "307") (name "unconnected-(U6-NC-Pad1)") (class "Default")
      (node (ref "U6") (pin "1") (pinfunction "NC_1") (pintype "passive"))
    )
    (net (code "308") (name "unconnected-(U6-NC-Pad8)") (class "Default")
      (node (ref "U6") (pin "8") (pinfunction "NC_8") (pintype "passive"))
    )
    (net (code "309") (name "unconnected-(U7-NC-Pad1)") (class "Default")
      (node (ref "U7") (pin "1") (pinfunction "NC_1") (pintype "passive"))
    )
    (net (code "310") (name "unconnected-(U7-NC-Pad8)") (class "Default")
      (node (ref "U7") (pin "8") (pinfunction "NC_8") (pintype "passive"))
    )
    (net (code "311") (name "unconnected-(U8-NC-Pad1)") (class "Default")
      (node (ref "U8") (pin "1") (pinfunction "NC_1") (pintype "passive"))
    )
    (net (code "312") (name "unconnected-(U8-NC-Pad8)") (class "Default")
      (node (ref "U8") (pin "8") (pinfunction "NC_8") (pintype "passive"))
    )
    (net (code "313") (name "unconnected-(U9-NC-Pad1)") (class "Default")
      (node (ref "U9") (pin "1") (pinfunction "NC_1") (pintype "passive"))
    )
    (net (code "314") (name "unconnected-(U9-NC-Pad8)") (class "Default")
      (node (ref "U9") (pin "8") (pinfunction "NC_8") (pintype "passive"))
    )
    (net (code "315") (name "unconnected-(U10-NC-Pad1)") (class "Default")
      (node (ref "U10") (pin "1") (pinfunction "NC_1") (pintype "passive"))
    )
    (net (code "316") (name "unconnected-(U10-NC-Pad8)") (class "Default")
      (node (ref "U10") (pin "8") (pinfunction "NC_8") (pintype "passive"))
    )
    (net (code "317") (name "unconnected-(U11-NC-Pad1)") (class "Default")
      (node (ref "U11") (pin "1") (pinfunction "NC_1") (pintype "passive"))
    )
    (net (code "318") (name "unconnected-(U11-NC-Pad8)") (class "Default")
      (node (ref "U11") (pin "8") (pinfunction "NC_8") (pintype "passive"))
    )
    (net (code "319") (name "unconnected-(U12-NC-Pad1)") (class "Default")
      (node (ref "U12") (pin "1") (pinfunction "NC_1") (pintype "passive"))
    )
    (net (code "320") (name "unconnected-(U12-NC-Pad8)") (class "Default")
      (node (ref "U12") (pin "8") (pinfunction "NC_8") (pintype "passive"))
    )
    (net (code "321") (name "unconnected-(U13-NC-Pad1)") (class "Default")
      (node (ref "U13") (pin "1") (pinfunction "NC_1") (pintype "passive"))
    )
    (net (code "322") (name "unconnected-(U13-NC-Pad8)") (class "Default")
      (node (ref "U13") (pin "8") (pinfunction "NC_8") (pintype "passive"))
    )
    (net (code "323") (name "unconnected-(U14-NC-Pad1)") (class "Default")
      (node (ref "U14") (pin "1") (pinfunction "NC_1") (pintype "passive"))
    )
    (net (code "324") (name "unconnected-(U14-NC-Pad8)") (class "Default")
      (node (ref "U14") (pin "8") (pinfunction "NC_8") (pintype "passive"))
    )
    (net (code "325") (name "unconnected-(U15-NC-Pad1)") (class "Default")
      (node (ref "U15") (pin "1") (pinfunction "NC_1") (pintype "passive"))
    )
    (net (code "326") (name "unconnected-(U15-NC-Pad8)") (class "Default")
      (node (ref "U15") (pin "8") (pinfunction "NC_8") (pintype "passive"))
    )
    (net (code "327") (name "unconnected-(U16-NC-Pad1)") (class "Default")
      (node (ref "U16") (pin "1") (pinfunction "NC_1") (pintype "passive"))
    )
    (net (code "328") (name "unconnected-(U16-NC-Pad8)") (class "Default")
      (node (ref "U16") (pin "8") (pinfunction "NC_8") (pintype "passive"))
    )
    (net (code "329") (name "unconnected-(U17-NC-Pad1)") (class "Default")
      (node (ref "U17") (pin "1") (pinfunction "NC_1") (pintype "passive"))
    )
    (net (code "330") (name "unconnected-(U17-NC-Pad8)") (class "Default")
      (node (ref "U17") (pin "8") (pinfunction "NC_8") (pintype "passive"))
    )
    (net (code "331") (name "unconnected-(U18-NC-Pad1)") (class "Default")
      (node (ref "U18") (pin "1") (pinfunction "NC_1") (pintype "passive"))
    )
    (net (code "332") (name "unconnected-(U18-NC-Pad8)") (class "Default")
      (node (ref "U18") (pin "8") (pinfunction "NC_8") (pintype "passive"))
    )
    (net (code "333") (name "unconnected-(U19-NC-Pad1)") (class "Default")
      (node (ref "U19") (pin "1") (pinfunction "NC_1") (pintype "passive"))
    )
    (net (code "334") (name "unconnected-(U19-NC-Pad8)") (class "Default")
      (node (ref "U19") (pin "8") (pinfunction "NC_8") (pintype "passive"))
    )
    (net (code "335") (name "unconnected-(U20-NC-Pad1)") (class "Default")
      (node (ref "U20") (pin "1") (pinfunction "NC_1") (pintype "passive"))
    )
    (net (code "336") (name "unconnected-(U20-NC-Pad8)") (class "Default")
      (node (ref "U20") (pin "8") (pinfunction "NC_8") (pintype "passive"))
    )
    (net (code "337") (name "unconnected-(U22-NC-Pad1)") (class "Default")
      (node (ref "U22") (pin "1") (pinfunction "NC_1") (pintype "passive"))
    )
    (net (code "338") (name "unconnected-(U22-NC-Pad8)") (class "Default")
      (node (ref "U22") (pin "8") (pinfunction "NC_8") (pintype "passive"))
    )
    (net (code "339") (name "unconnected-(U22-OUTB-Pad5)") (class "Default")
      (node (ref "U22") (pin "5") (pinfunction "OUTB_5") (pintype "output"))
    )
    (net (code "340") (name "unconnected-(U27-DNC-Pad2)") (class "Default")
      (node (ref "U27") (pin "2") (pinfunction "DNC_2") (pintype "passive"))
    )
    (net (code "341") (name "unconnected-(U27-DNC-Pad9)") (class "Default")
      (node (ref "U27") (pin "9") (pinfunction "DNC_9") (pintype "passive"))
    )
    (net (code "342") (name "unconnected-(U27-DNC-Pad12)") (class "Default")
      (node (ref "U27") (pin "12") (pinfunction "DNC_12") (pintype "passive"))
    )
    (net (code "343") (name "unconnected-(U27-DNC-Pad14)") (class "Default")
      (node (ref "U27") (pin "14") (pinfunction "DNC_14") (pintype "passive"))
    )
    (net (code "344") (name "unconnected-(U27-DNC-Pad15)") (class "Default")
      (node (ref "U27") (pin "15") (pinfunction "DNC_15") (pintype "passive"))
    )
    (net (code "345") (name "unconnected-(U27-DNC-Pad16)") (class "Default")
      (node (ref "U27") (pin "16") (pinfunction "DNC_16") (pintype "passive"))
    )
    (net (code "346") (name "unconnected-(U27-~{CEO}-Pad13)") (class "Default")
      (node (ref "U27") (pin "13") (pinfunction "~{CEO}_13") (pintype "output"))
    )
    (net (code "347") (name "unconnected-(X1-E{slash}D-Pad1)") (class "Default")
      (node (ref "X1") (pin "1") (pinfunction "E/D_1") (pintype "input"))
    )
    (net (code "348") (name "unconnected-(telecontrolli-Pad7)") (class "Default")
      (node (ref "telecontrolli") (pin "7") (pinfunction "7_7") (pintype "passive"))
    )
    (net (code "349") (name "unconnected-(telecontrolli-Pad8)") (class "Default")
      (node (ref "telecontrolli") (pin "8") (pinfunction "8_8") (pintype "passive"))
    )
  )
)
